# dsp_board_dds_vga.net
KiCad netlist of a schematic drawn in EAGLE
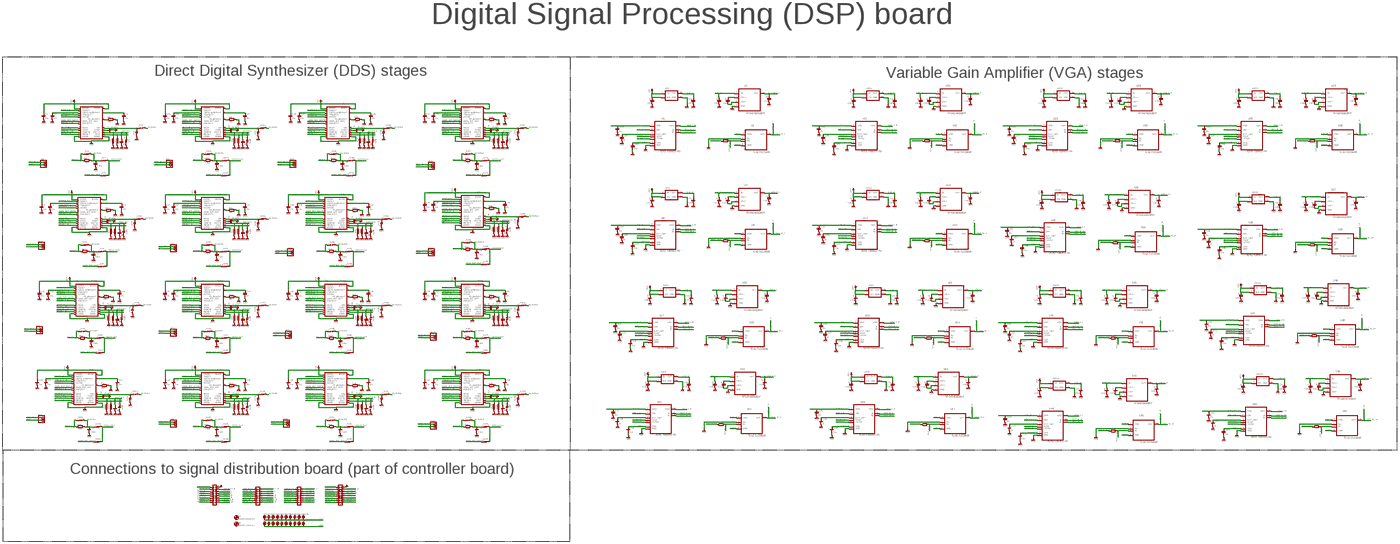
[diagram p0: schematic, sheet 1, overview]
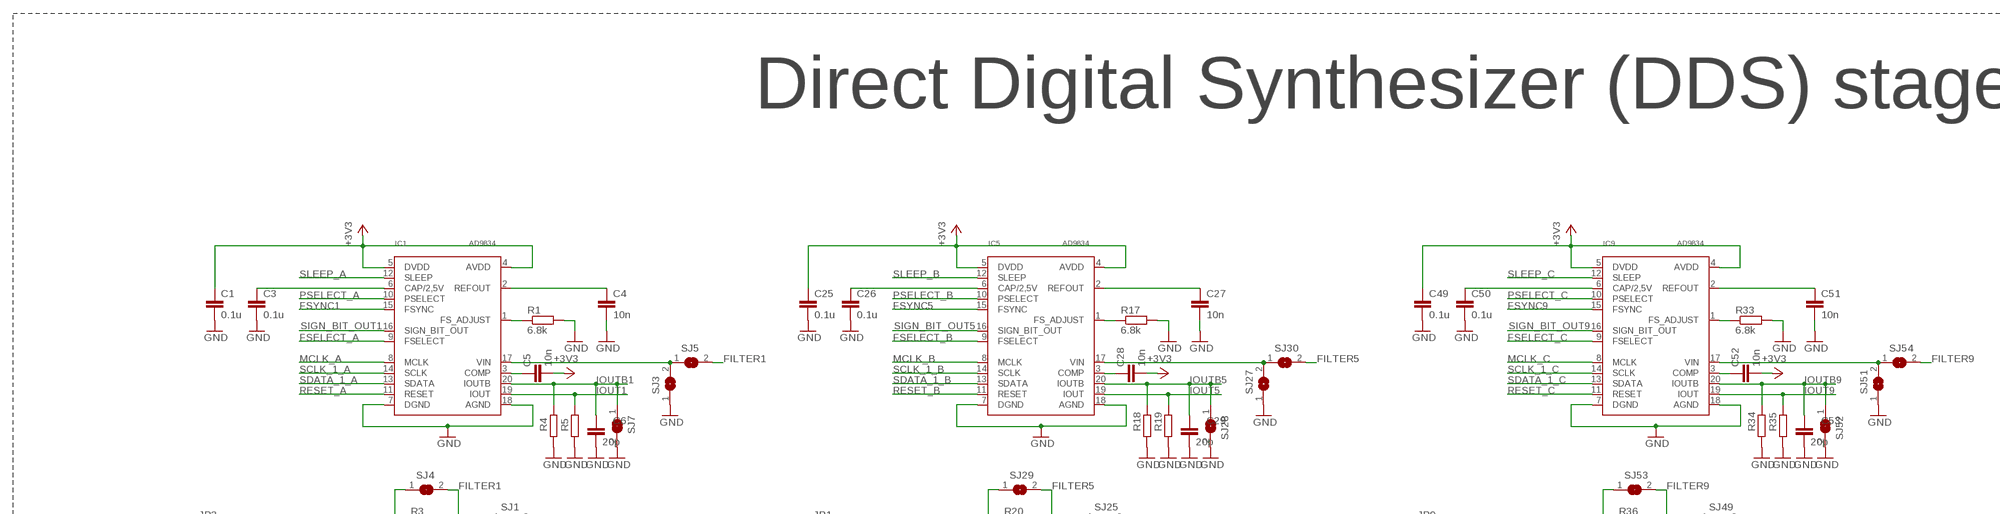
[diagram p1: schematic, sheet 1, part 1 of 7]
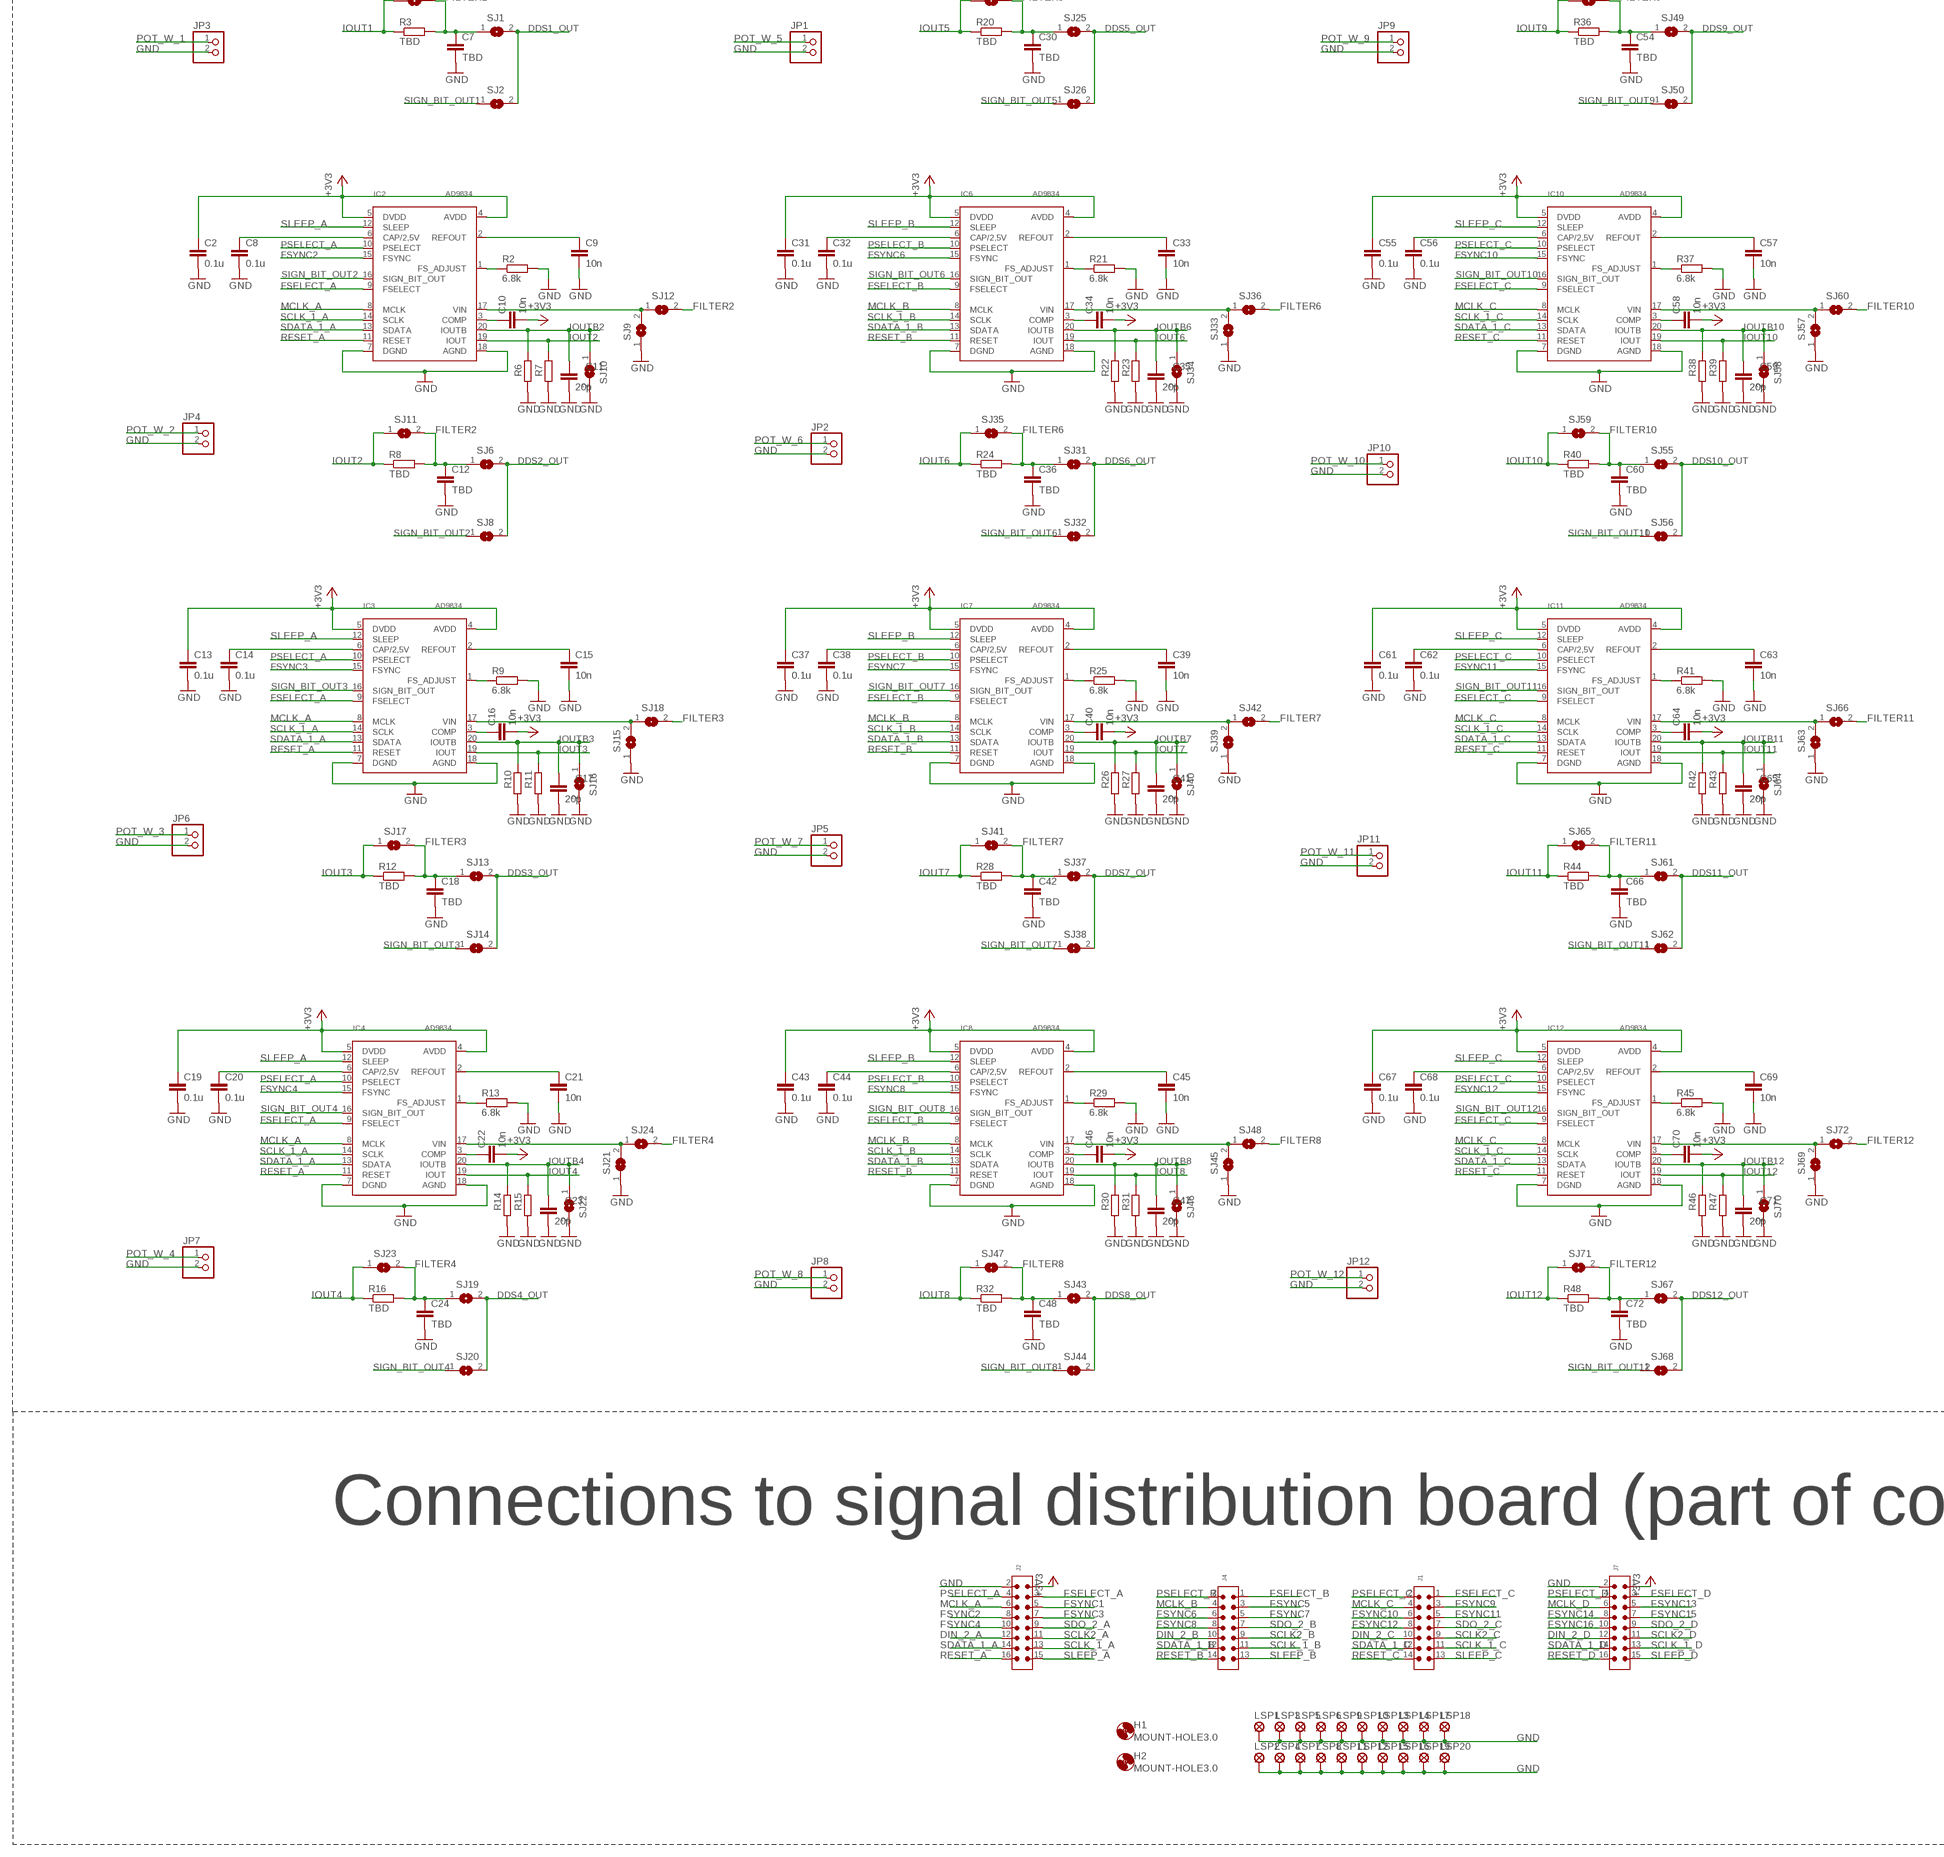
[diagram p2: schematic, sheet 1, part 2 of 7]
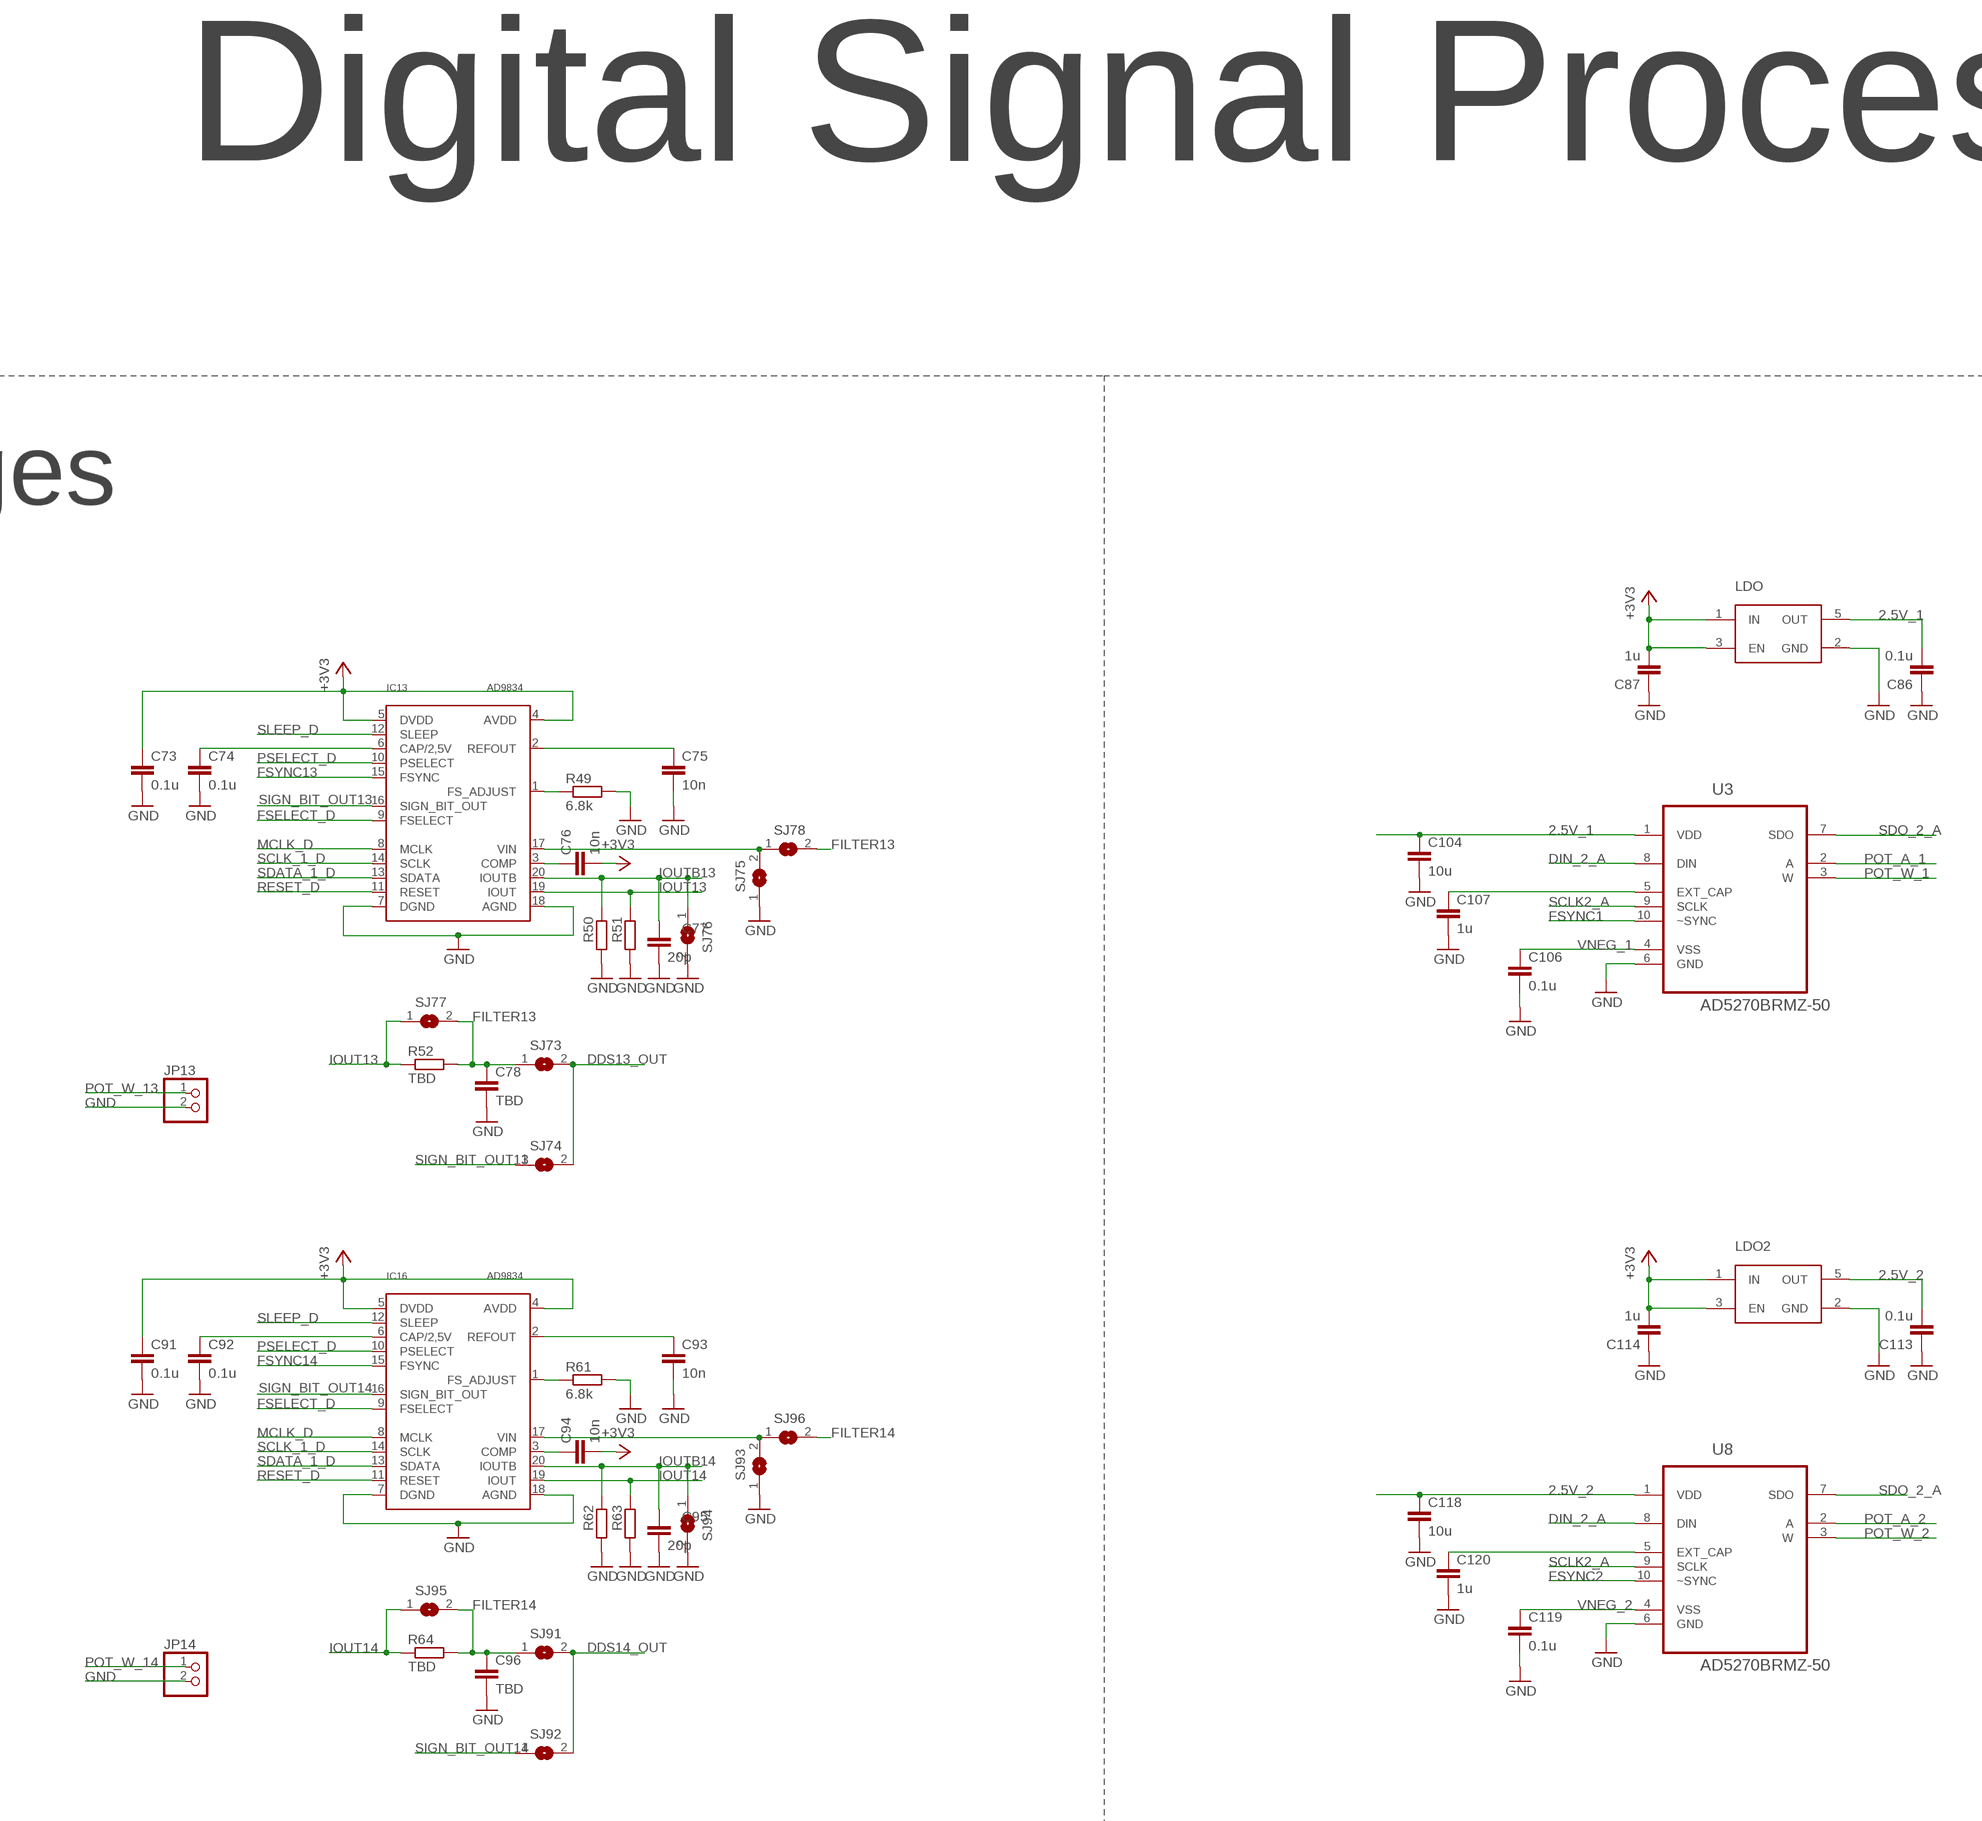
[diagram p3: schematic, sheet 1, part 3 of 7]
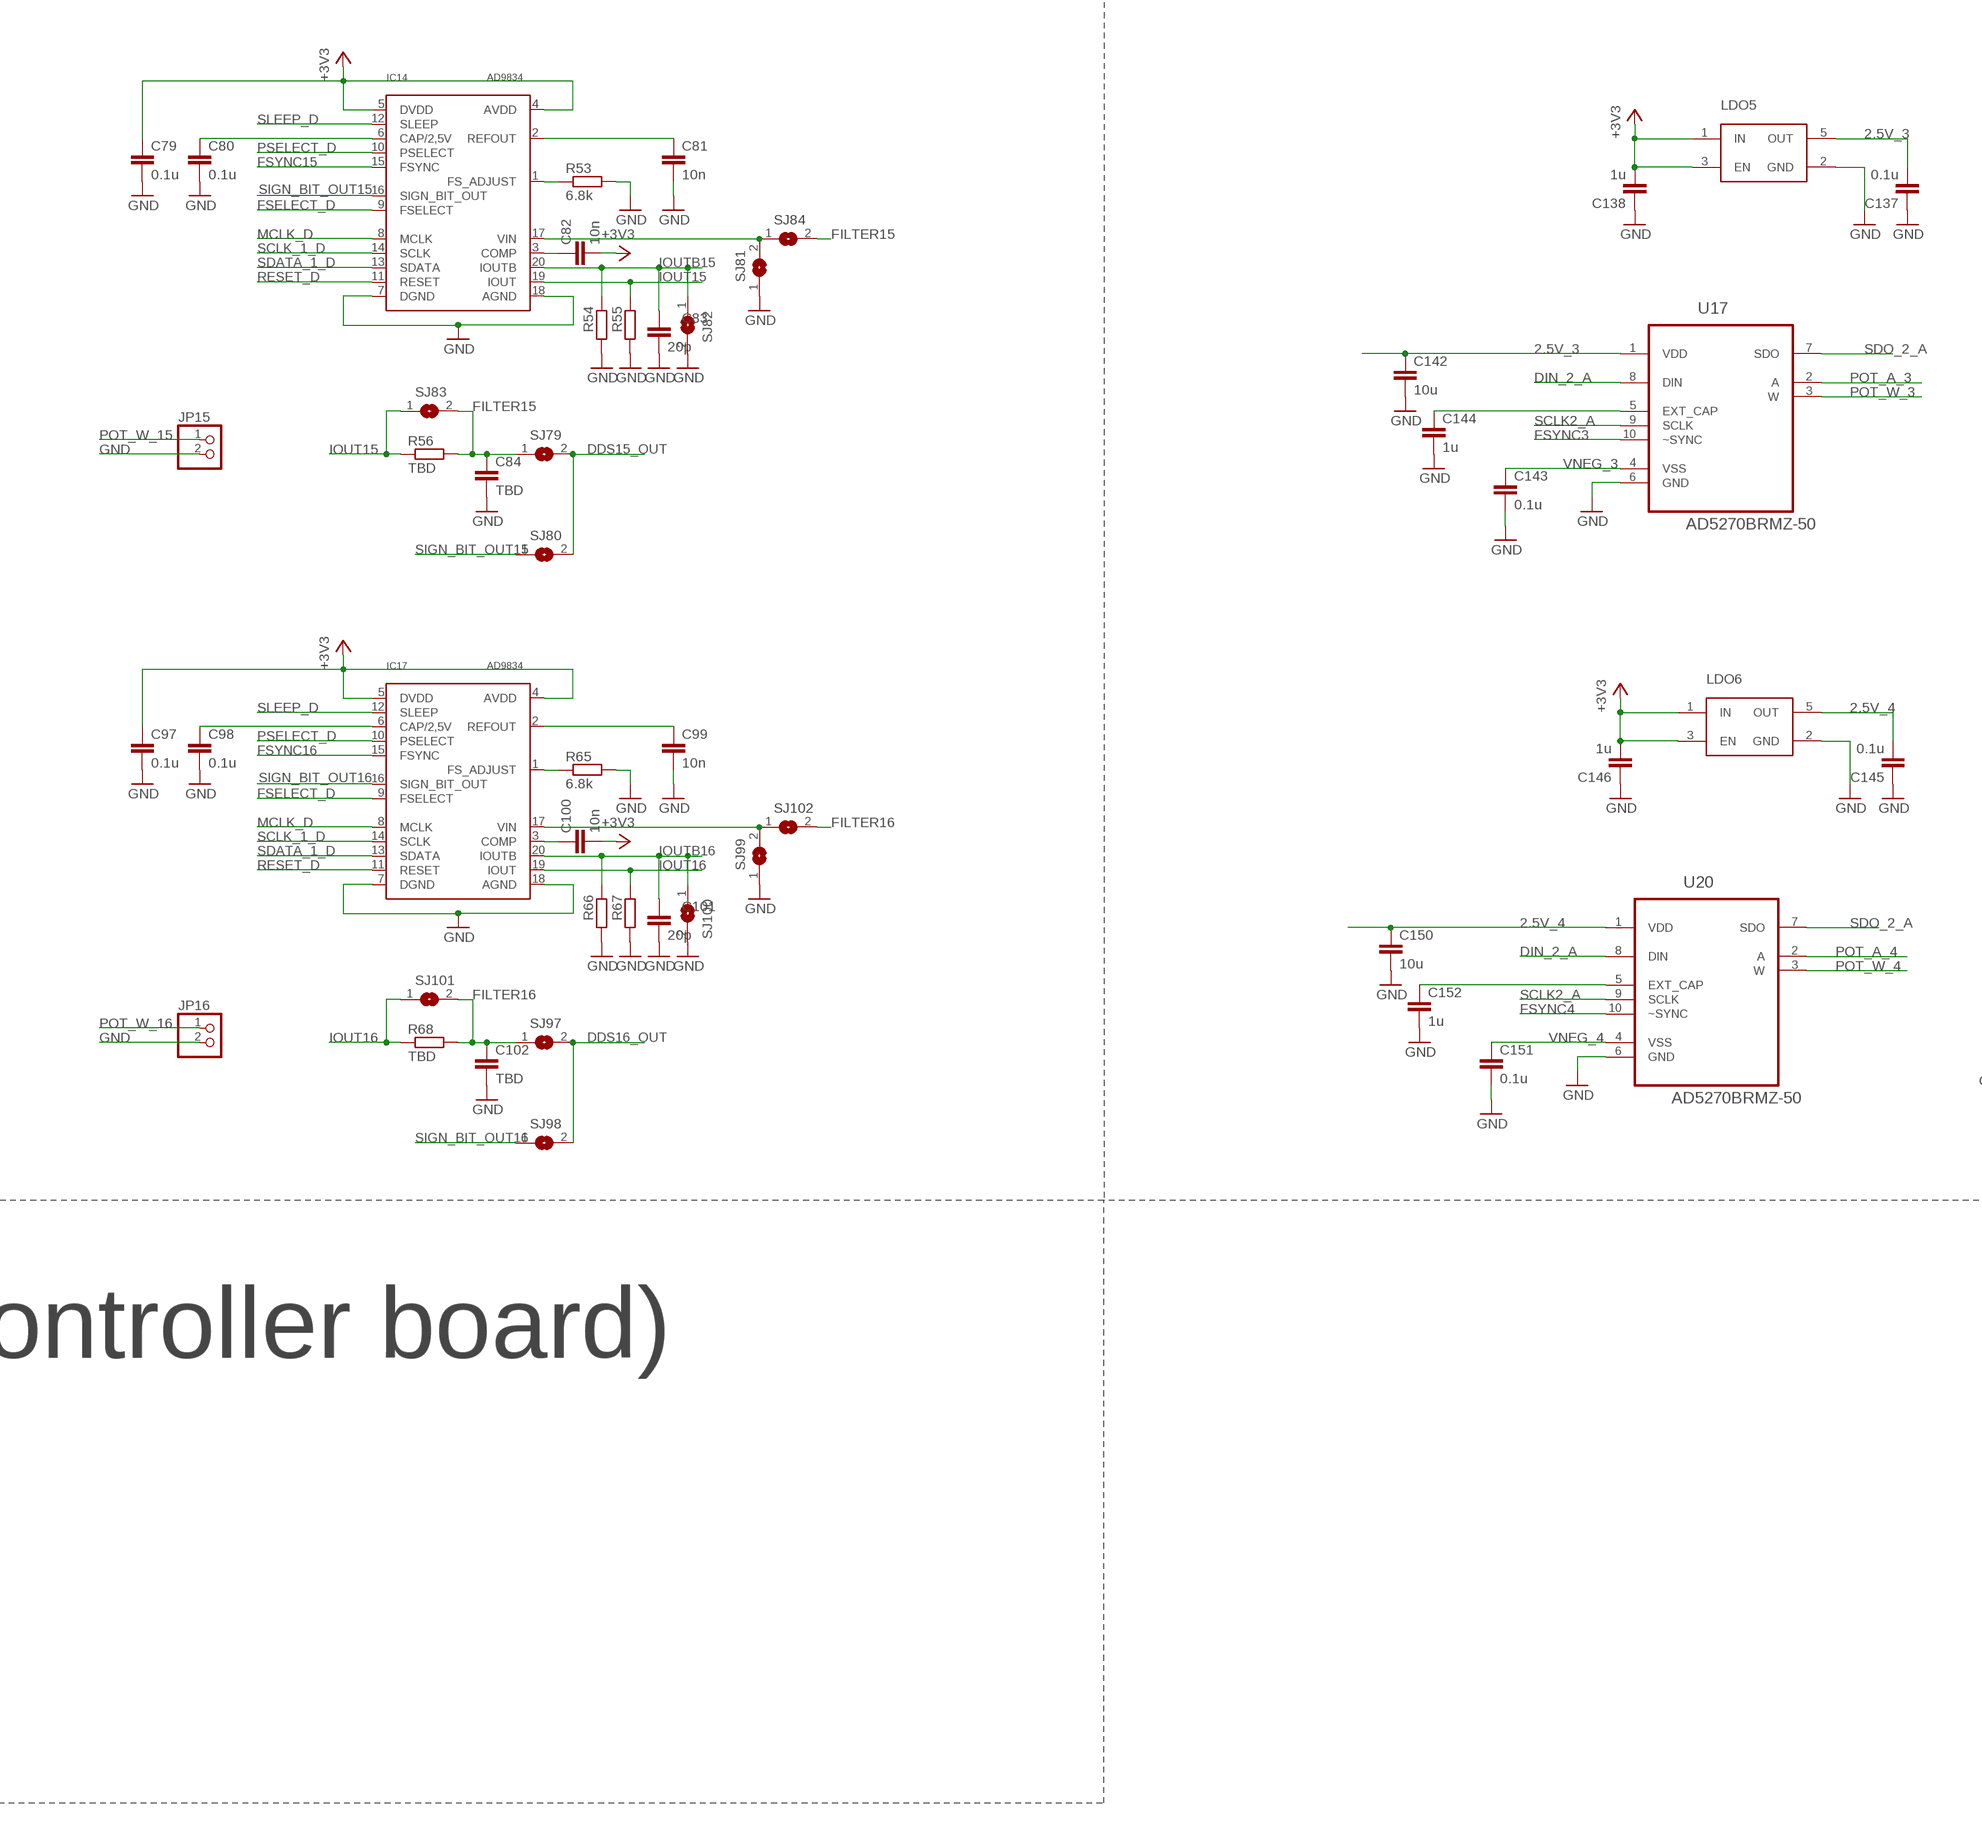
[diagram p4: schematic, sheet 1, part 4 of 7]
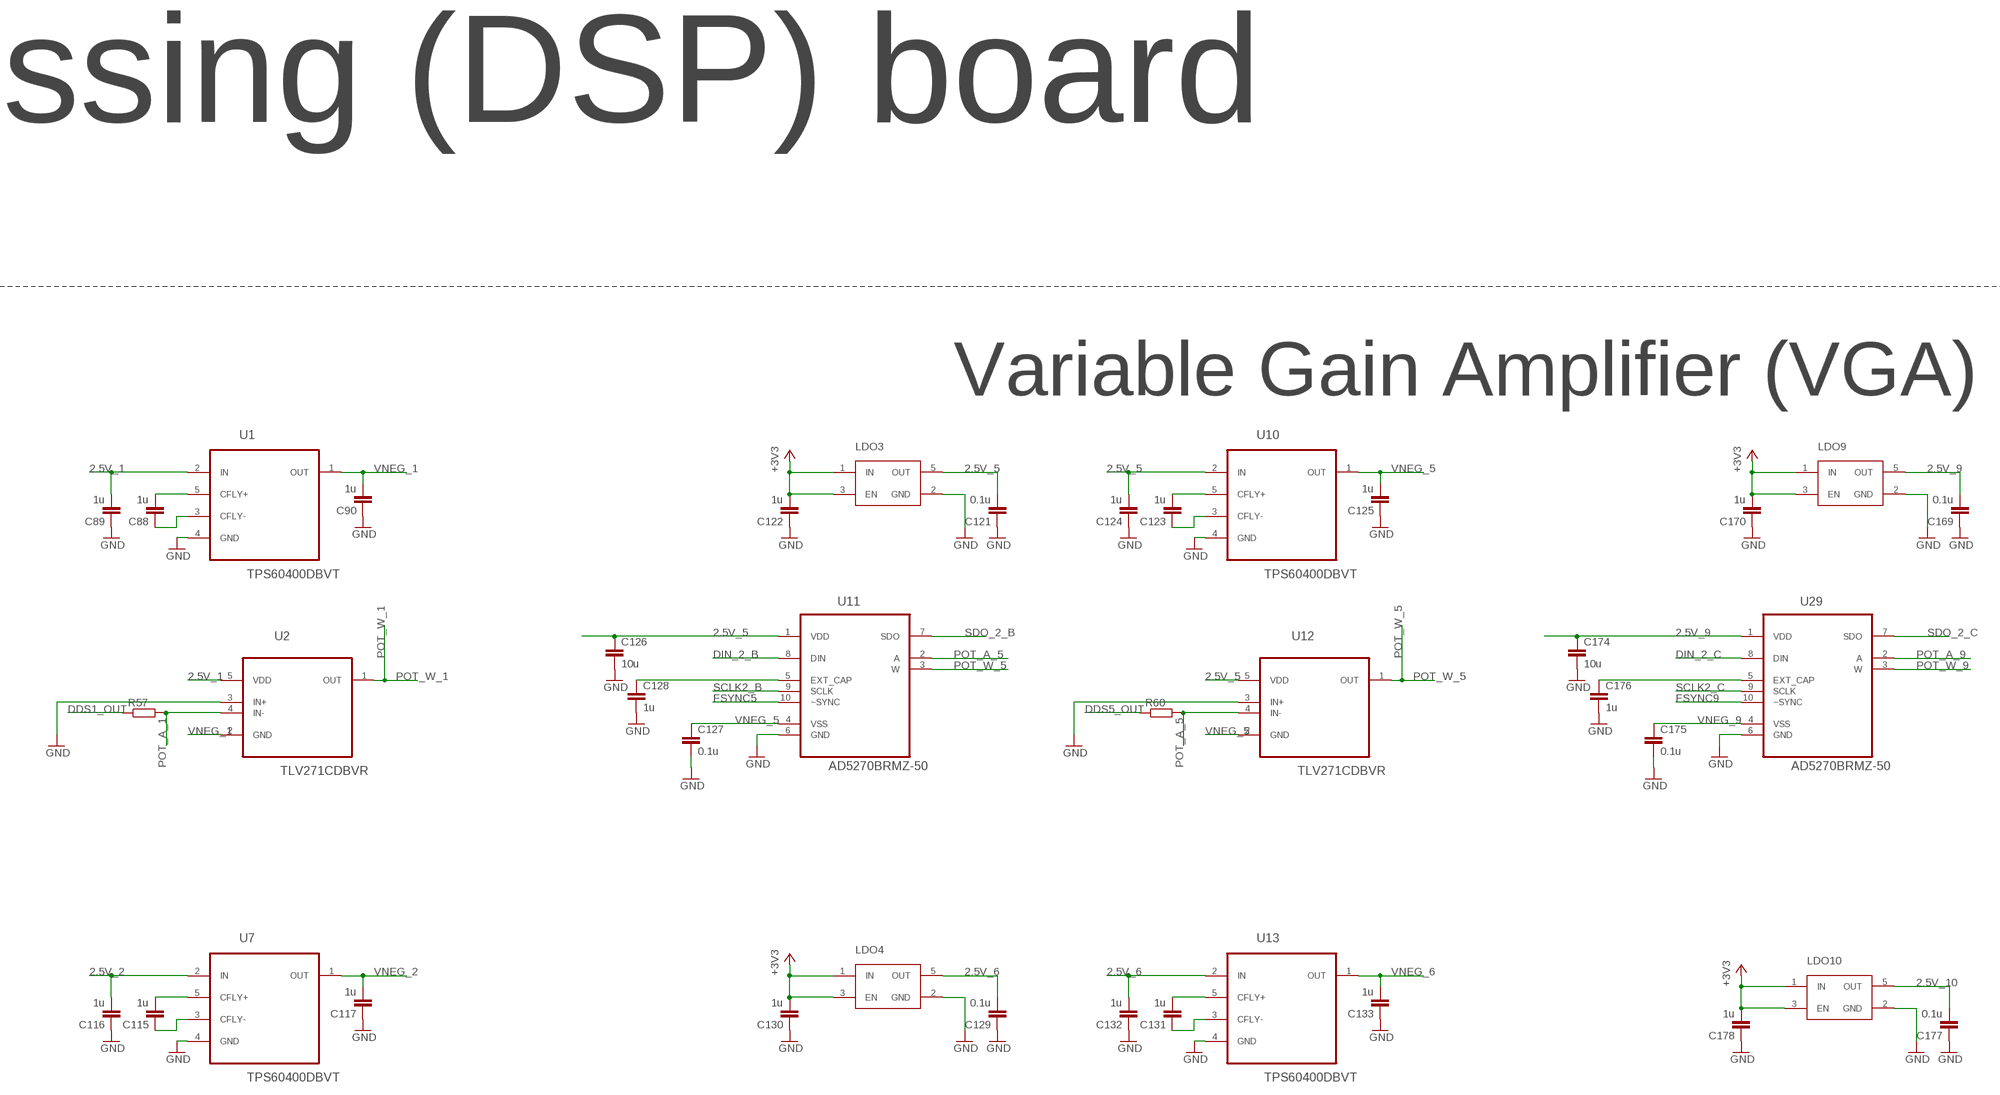
[diagram p5: schematic, sheet 1, part 5 of 7]
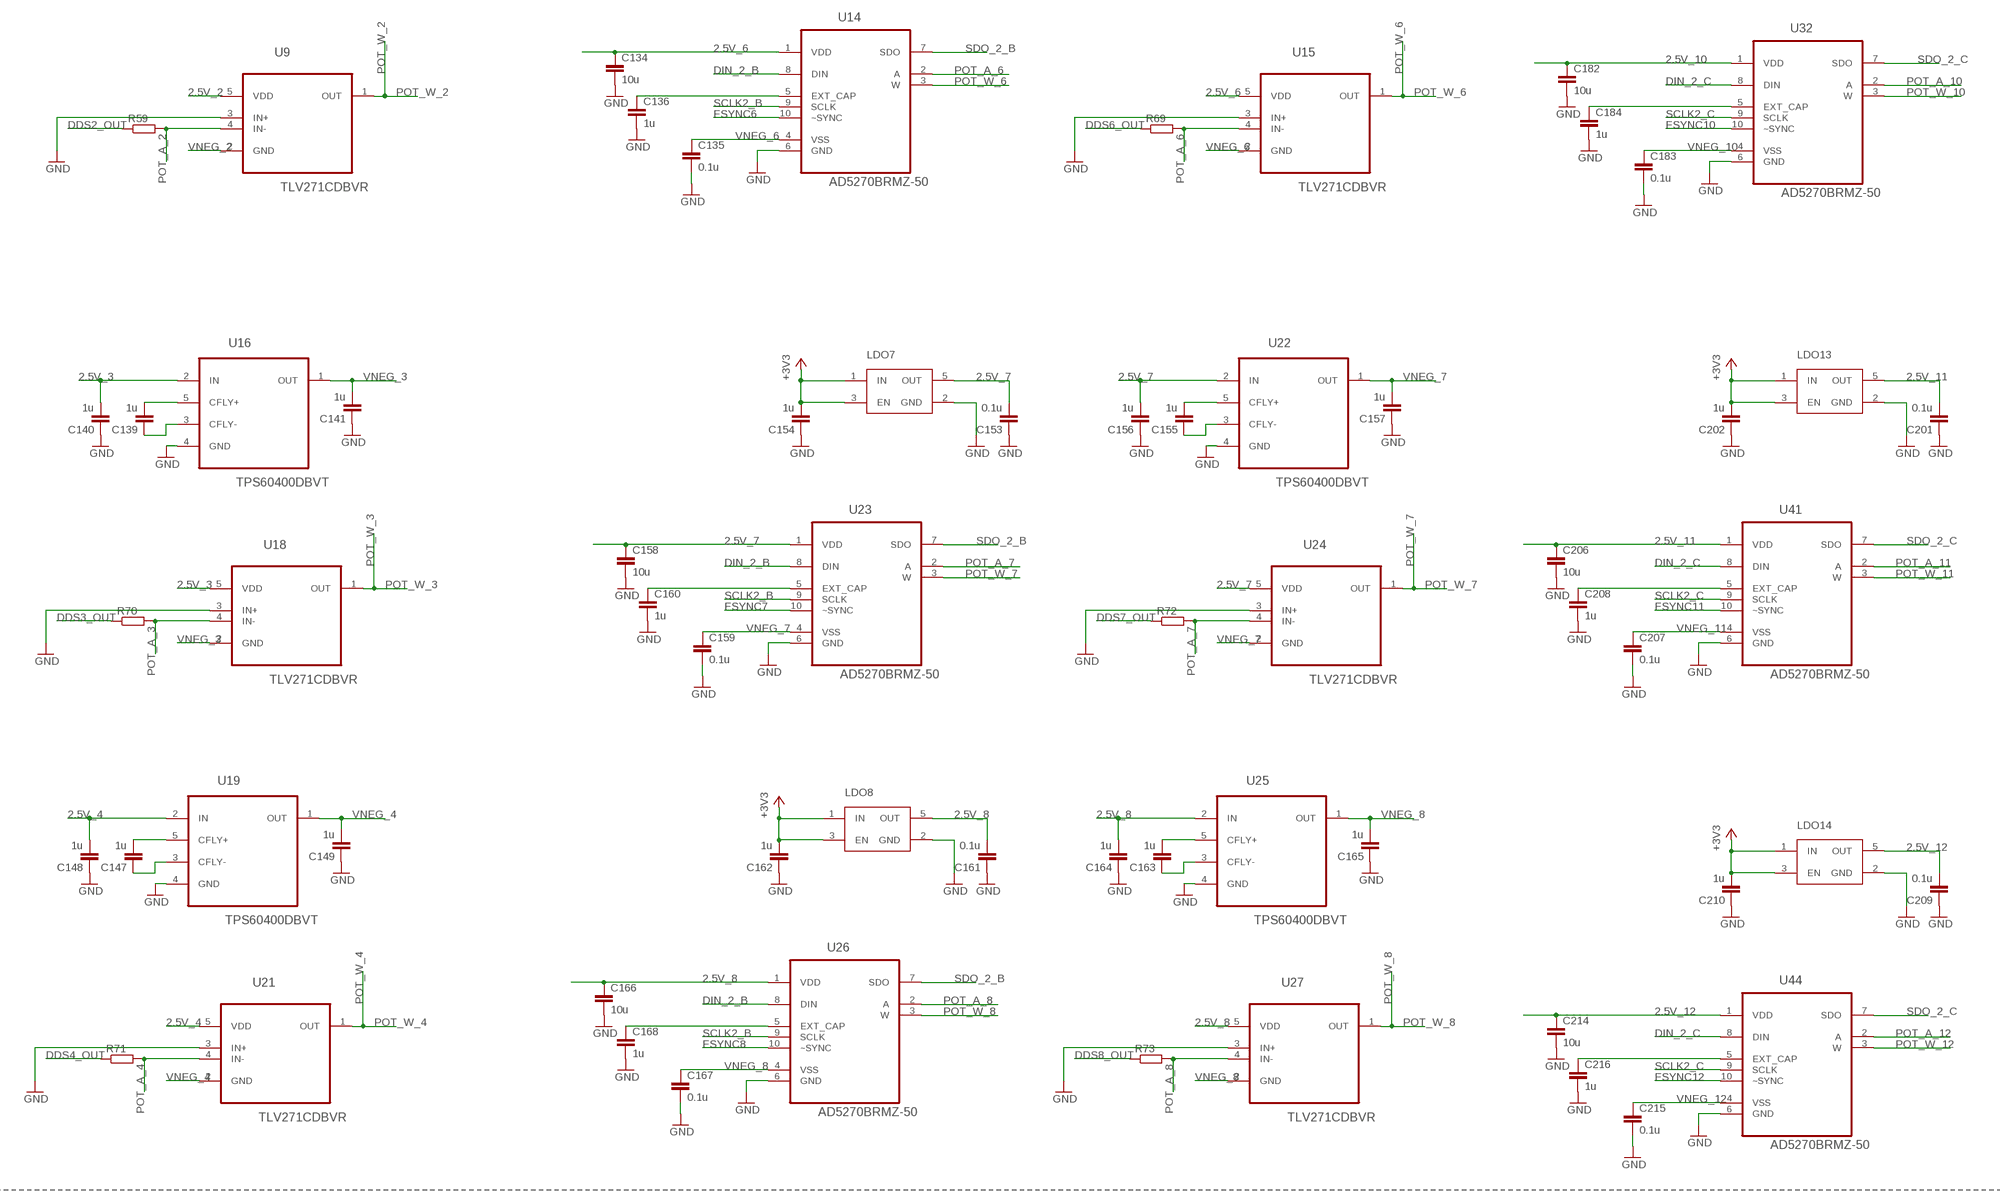
[diagram p6: schematic, sheet 1, part 6 of 7]
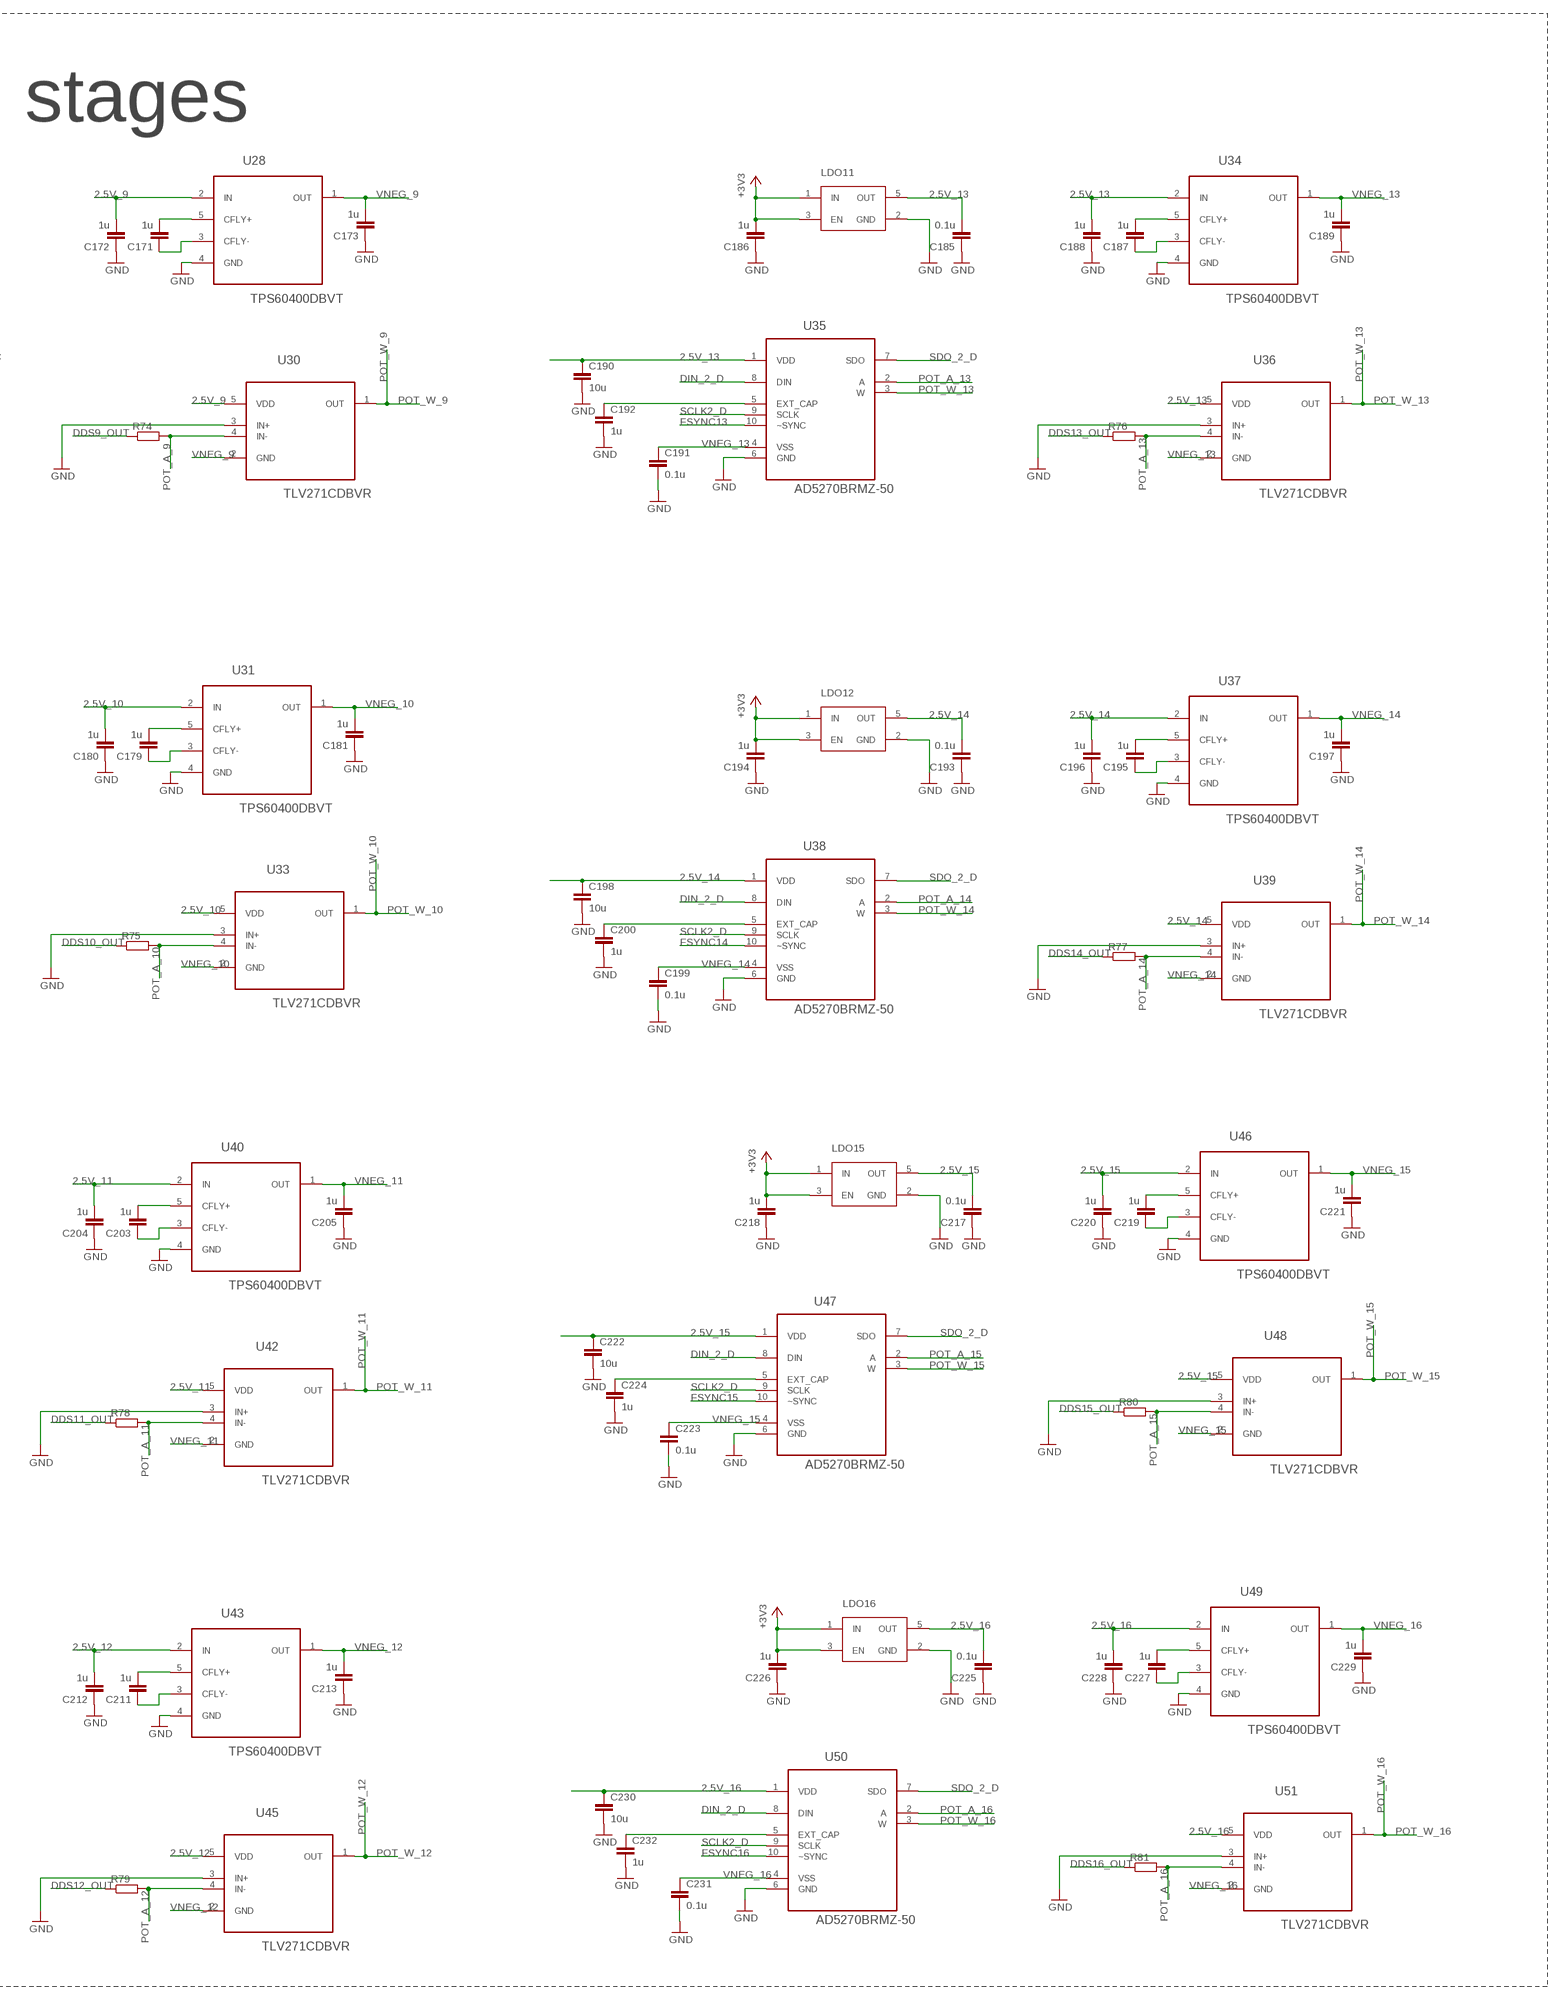
[diagram p7: schematic, sheet 1, part 7 of 7]

(export (version "E")
  (design (tool "Eeschema 10.0.6"))
  (components
    (comp (ref "C1")
      (value "0.1u")
      (footprint "eagle-import:C0603")
      (libsource (lib "eagle-import") (part "C-EUC0603"))
    )
    (comp (ref "C2")
      (value "0.1u")
      (footprint "eagle-import:C0603")
      (libsource (lib "eagle-import") (part "C-EUC0603"))
    )
    (comp (ref "C3")
      (value "0.1u")
      (footprint "eagle-import:C0603")
      (libsource (lib "eagle-import") (part "C-EUC0603"))
    )
    (comp (ref "C4")
      (value "10n")
      (footprint "eagle-import:C0603")
      (libsource (lib "eagle-import") (part "C-EUC0603"))
    )
    (comp (ref "C5")
      (value "10n")
      (footprint "eagle-import:C0603")
      (libsource (lib "eagle-import") (part "C-EUC0603"))
    )
    (comp (ref "C6")
      (value "20p")
      (footprint "eagle-import:C0603")
      (libsource (lib "eagle-import") (part "C-EUC0603"))
    )
    (comp (ref "C7")
      (value "TBD")
      (footprint "eagle-import:C0603")
      (libsource (lib "eagle-import") (part "C-EUC0603"))
    )
    (comp (ref "C8")
      (value "0.1u")
      (footprint "eagle-import:C0603")
      (libsource (lib "eagle-import") (part "C-EUC0603"))
    )
    (comp (ref "C9")
      (value "10n")
      (footprint "eagle-import:C0603")
      (libsource (lib "eagle-import") (part "C-EUC0603"))
    )
    (comp (ref "C10")
      (value "10n")
      (footprint "eagle-import:C0603")
      (libsource (lib "eagle-import") (part "C-EUC0603"))
    )
    (comp (ref "C11")
      (value "20p")
      (footprint "eagle-import:C0603")
      (libsource (lib "eagle-import") (part "C-EUC0603"))
    )
    (comp (ref "C12")
      (value "TBD")
      (footprint "eagle-import:C0603")
      (libsource (lib "eagle-import") (part "C-EUC0603"))
    )
    (comp (ref "C13")
      (value "0.1u")
      (footprint "eagle-import:C0603")
      (libsource (lib "eagle-import") (part "C-EUC0603"))
    )
    (comp (ref "C14")
      (value "0.1u")
      (footprint "eagle-import:C0603")
      (libsource (lib "eagle-import") (part "C-EUC0603"))
    )
    (comp (ref "C15")
      (value "10n")
      (footprint "eagle-import:C0603")
      (libsource (lib "eagle-import") (part "C-EUC0603"))
    )
    (comp (ref "C16")
      (value "10n")
      (footprint "eagle-import:C0603")
      (libsource (lib "eagle-import") (part "C-EUC0603"))
    )
    (comp (ref "C17")
      (value "20p")
      (footprint "eagle-import:C0603")
      (libsource (lib "eagle-import") (part "C-EUC0603"))
    )
    (comp (ref "C18")
      (value "TBD")
      (footprint "eagle-import:C0603")
      (libsource (lib "eagle-import") (part "C-EUC0603"))
    )
    (comp (ref "C19")
      (value "0.1u")
      (footprint "eagle-import:C0603")
      (libsource (lib "eagle-import") (part "C-EUC0603"))
    )
    (comp (ref "C20")
      (value "0.1u")
      (footprint "eagle-import:C0603")
      (libsource (lib "eagle-import") (part "C-EUC0603"))
    )
    (comp (ref "C21")
      (value "10n")
      (footprint "eagle-import:C0603")
      (libsource (lib "eagle-import") (part "C-EUC0603"))
    )
    (comp (ref "C22")
      (value "10n")
      (footprint "eagle-import:C0603")
      (libsource (lib "eagle-import") (part "C-EUC0603"))
    )
    (comp (ref "C23")
      (value "20p")
      (footprint "eagle-import:C0603")
      (libsource (lib "eagle-import") (part "C-EUC0603"))
    )
    (comp (ref "C24")
      (value "TBD")
      (footprint "eagle-import:C0603")
      (libsource (lib "eagle-import") (part "C-EUC0603"))
    )
    (comp (ref "C25")
      (value "0.1u")
      (footprint "eagle-import:C0603")
      (libsource (lib "eagle-import") (part "C-EUC0603"))
    )
    (comp (ref "C26")
      (value "0.1u")
      (footprint "eagle-import:C0603")
      (libsource (lib "eagle-import") (part "C-EUC0603"))
    )
    (comp (ref "C27")
      (value "10n")
      (footprint "eagle-import:C0603")
      (libsource (lib "eagle-import") (part "C-EUC0603"))
    )
    (comp (ref "C28")
      (value "10n")
      (footprint "eagle-import:C0603")
      (libsource (lib "eagle-import") (part "C-EUC0603"))
    )
    (comp (ref "C29")
      (value "20p")
      (footprint "eagle-import:C0603")
      (libsource (lib "eagle-import") (part "C-EUC0603"))
    )
    (comp (ref "C30")
      (value "TBD")
      (footprint "eagle-import:C0603")
      (libsource (lib "eagle-import") (part "C-EUC0603"))
    )
    (comp (ref "C31")
      (value "0.1u")
      (footprint "eagle-import:C0603")
      (libsource (lib "eagle-import") (part "C-EUC0603"))
    )
    (comp (ref "C32")
      (value "0.1u")
      (footprint "eagle-import:C0603")
      (libsource (lib "eagle-import") (part "C-EUC0603"))
    )
    (comp (ref "C33")
      (value "10n")
      (footprint "eagle-import:C0603")
      (libsource (lib "eagle-import") (part "C-EUC0603"))
    )
    (comp (ref "C34")
      (value "10n")
      (footprint "eagle-import:C0603")
      (libsource (lib "eagle-import") (part "C-EUC0603"))
    )
    (comp (ref "C35")
      (value "20p")
      (footprint "eagle-import:C0603")
      (libsource (lib "eagle-import") (part "C-EUC0603"))
    )
    (comp (ref "C36")
      (value "TBD")
      (footprint "eagle-import:C0603")
      (libsource (lib "eagle-import") (part "C-EUC0603"))
    )
    (comp (ref "C37")
      (value "0.1u")
      (footprint "eagle-import:C0603")
      (libsource (lib "eagle-import") (part "C-EUC0603"))
    )
    (comp (ref "C38")
      (value "0.1u")
      (footprint "eagle-import:C0603")
      (libsource (lib "eagle-import") (part "C-EUC0603"))
    )
    (comp (ref "C39")
      (value "10n")
      (footprint "eagle-import:C0603")
      (libsource (lib "eagle-import") (part "C-EUC0603"))
    )
    (comp (ref "C40")
      (value "10n")
      (footprint "eagle-import:C0603")
      (libsource (lib "eagle-import") (part "C-EUC0603"))
    )
    (comp (ref "C41")
      (value "20p")
      (footprint "eagle-import:C0603")
      (libsource (lib "eagle-import") (part "C-EUC0603"))
    )
    (comp (ref "C42")
      (value "TBD")
      (footprint "eagle-import:C0603")
      (libsource (lib "eagle-import") (part "C-EUC0603"))
    )
    (comp (ref "C43")
      (value "0.1u")
      (footprint "eagle-import:C0603")
      (libsource (lib "eagle-import") (part "C-EUC0603"))
    )
    (comp (ref "C44")
      (value "0.1u")
      (footprint "eagle-import:C0603")
      (libsource (lib "eagle-import") (part "C-EUC0603"))
    )
    (comp (ref "C45")
      (value "10n")
      (footprint "eagle-import:C0603")
      (libsource (lib "eagle-import") (part "C-EUC0603"))
    )
    (comp (ref "C46")
      (value "10n")
      (footprint "eagle-import:C0603")
      (libsource (lib "eagle-import") (part "C-EUC0603"))
    )
    (comp (ref "C47")
      (value "20p")
      (footprint "eagle-import:C0603")
      (libsource (lib "eagle-import") (part "C-EUC0603"))
    )
    (comp (ref "C48")
      (value "TBD")
      (footprint "eagle-import:C0603")
      (libsource (lib "eagle-import") (part "C-EUC0603"))
    )
    (comp (ref "C49")
      (value "0.1u")
      (footprint "eagle-import:C0603")
      (libsource (lib "eagle-import") (part "C-EUC0603"))
    )
    (comp (ref "C50")
      (value "0.1u")
      (footprint "eagle-import:C0603")
      (libsource (lib "eagle-import") (part "C-EUC0603"))
    )
    (comp (ref "C51")
      (value "10n")
      (footprint "eagle-import:C0603")
      (libsource (lib "eagle-import") (part "C-EUC0603"))
    )
    (comp (ref "C52")
      (value "10n")
      (footprint "eagle-import:C0603")
      (libsource (lib "eagle-import") (part "C-EUC0603"))
    )
    (comp (ref "C53")
      (value "20p")
      (footprint "eagle-import:C0603")
      (libsource (lib "eagle-import") (part "C-EUC0603"))
    )
    (comp (ref "C54")
      (value "TBD")
      (footprint "eagle-import:C0603")
      (libsource (lib "eagle-import") (part "C-EUC0603"))
    )
    (comp (ref "C55")
      (value "0.1u")
      (footprint "eagle-import:C0603")
      (libsource (lib "eagle-import") (part "C-EUC0603"))
    )
    (comp (ref "C56")
      (value "0.1u")
      (footprint "eagle-import:C0603")
      (libsource (lib "eagle-import") (part "C-EUC0603"))
    )
    (comp (ref "C57")
      (value "10n")
      (footprint "eagle-import:C0603")
      (libsource (lib "eagle-import") (part "C-EUC0603"))
    )
    (comp (ref "C58")
      (value "10n")
      (footprint "eagle-import:C0603")
      (libsource (lib "eagle-import") (part "C-EUC0603"))
    )
    (comp (ref "C59")
      (value "20p")
      (footprint "eagle-import:C0603")
      (libsource (lib "eagle-import") (part "C-EUC0603"))
    )
    (comp (ref "C60")
      (value "TBD")
      (footprint "eagle-import:C0603")
      (libsource (lib "eagle-import") (part "C-EUC0603"))
    )
    (comp (ref "C61")
      (value "0.1u")
      (footprint "eagle-import:C0603")
      (libsource (lib "eagle-import") (part "C-EUC0603"))
    )
    (comp (ref "C62")
      (value "0.1u")
      (footprint "eagle-import:C0603")
      (libsource (lib "eagle-import") (part "C-EUC0603"))
    )
    (comp (ref "C63")
      (value "10n")
      (footprint "eagle-import:C0603")
      (libsource (lib "eagle-import") (part "C-EUC0603"))
    )
    (comp (ref "C64")
      (value "10n")
      (footprint "eagle-import:C0603")
      (libsource (lib "eagle-import") (part "C-EUC0603"))
    )
    (comp (ref "C65")
      (value "20p")
      (footprint "eagle-import:C0603")
      (libsource (lib "eagle-import") (part "C-EUC0603"))
    )
    (comp (ref "C66")
      (value "TBD")
      (footprint "eagle-import:C0603")
      (libsource (lib "eagle-import") (part "C-EUC0603"))
    )
    (comp (ref "C67")
      (value "0.1u")
      (footprint "eagle-import:C0603")
      (libsource (lib "eagle-import") (part "C-EUC0603"))
    )
    (comp (ref "C68")
      (value "0.1u")
      (footprint "eagle-import:C0603")
      (libsource (lib "eagle-import") (part "C-EUC0603"))
    )
    (comp (ref "C69")
      (value "10n")
      (footprint "eagle-import:C0603")
      (libsource (lib "eagle-import") (part "C-EUC0603"))
    )
    (comp (ref "C70")
      (value "10n")
      (footprint "eagle-import:C0603")
      (libsource (lib "eagle-import") (part "C-EUC0603"))
    )
    (comp (ref "C71")
      (value "20p")
      (footprint "eagle-import:C0603")
      (libsource (lib "eagle-import") (part "C-EUC0603"))
    )
    (comp (ref "C72")
      (value "TBD")
      (footprint "eagle-import:C0603")
      (libsource (lib "eagle-import") (part "C-EUC0603"))
    )
    (comp (ref "C73")
      (value "0.1u")
      (footprint "eagle-import:C0603")
      (libsource (lib "eagle-import") (part "C-EUC0603"))
    )
    (comp (ref "C74")
      (value "0.1u")
      (footprint "eagle-import:C0603")
      (libsource (lib "eagle-import") (part "C-EUC0603"))
    )
    (comp (ref "C75")
      (value "10n")
      (footprint "eagle-import:C0603")
      (libsource (lib "eagle-import") (part "C-EUC0603"))
    )
    (comp (ref "C76")
      (value "10n")
      (footprint "eagle-import:C0603")
      (libsource (lib "eagle-import") (part "C-EUC0603"))
    )
    (comp (ref "C77")
      (value "20p")
      (footprint "eagle-import:C0603")
      (libsource (lib "eagle-import") (part "C-EUC0603"))
    )
    (comp (ref "C78")
      (value "TBD")
      (footprint "eagle-import:C0603")
      (libsource (lib "eagle-import") (part "C-EUC0603"))
    )
    (comp (ref "C79")
      (value "0.1u")
      (footprint "eagle-import:C0603")
      (libsource (lib "eagle-import") (part "C-EUC0603"))
    )
    (comp (ref "C80")
      (value "0.1u")
      (footprint "eagle-import:C0603")
      (libsource (lib "eagle-import") (part "C-EUC0603"))
    )
    (comp (ref "C81")
      (value "10n")
      (footprint "eagle-import:C0603")
      (libsource (lib "eagle-import") (part "C-EUC0603"))
    )
    (comp (ref "C82")
      (value "10n")
      (footprint "eagle-import:C0603")
      (libsource (lib "eagle-import") (part "C-EUC0603"))
    )
    (comp (ref "C83")
      (value "20p")
      (footprint "eagle-import:C0603")
      (libsource (lib "eagle-import") (part "C-EUC0603"))
    )
    (comp (ref "C84")
      (value "TBD")
      (footprint "eagle-import:C0603")
      (libsource (lib "eagle-import") (part "C-EUC0603"))
    )
    (comp (ref "C86")
      (value "0.1u")
      (footprint "eagle-import:C0603")
      (libsource (lib "eagle-import") (part "C-EUC0603"))
    )
    (comp (ref "C87")
      (value "1u")
      (footprint "eagle-import:C0603")
      (libsource (lib "eagle-import") (part "C-EUC0603"))
    )
    (comp (ref "C88")
      (value "1u")
      (footprint "eagle-import:C0603")
      (libsource (lib "eagle-import") (part "C-EUC0603"))
    )
    (comp (ref "C89")
      (value "1u")
      (footprint "eagle-import:C0603")
      (libsource (lib "eagle-import") (part "C-EUC0603"))
    )
    (comp (ref "C90")
      (value "1u")
      (footprint "eagle-import:C0603")
      (libsource (lib "eagle-import") (part "C-EUC0603"))
    )
    (comp (ref "C91")
      (value "0.1u")
      (footprint "eagle-import:C0603")
      (libsource (lib "eagle-import") (part "C-EUC0603"))
    )
    (comp (ref "C92")
      (value "0.1u")
      (footprint "eagle-import:C0603")
      (libsource (lib "eagle-import") (part "C-EUC0603"))
    )
    (comp (ref "C93")
      (value "10n")
      (footprint "eagle-import:C0603")
      (libsource (lib "eagle-import") (part "C-EUC0603"))
    )
    (comp (ref "C94")
      (value "10n")
      (footprint "eagle-import:C0603")
      (libsource (lib "eagle-import") (part "C-EUC0603"))
    )
    (comp (ref "C95")
      (value "20p")
      (footprint "eagle-import:C0603")
      (libsource (lib "eagle-import") (part "C-EUC0603"))
    )
    (comp (ref "C96")
      (value "TBD")
      (footprint "eagle-import:C0603")
      (libsource (lib "eagle-import") (part "C-EUC0603"))
    )
    (comp (ref "C97")
      (value "0.1u")
      (footprint "eagle-import:C0603")
      (libsource (lib "eagle-import") (part "C-EUC0603"))
    )
    (comp (ref "C98")
      (value "0.1u")
      (footprint "eagle-import:C0603")
      (libsource (lib "eagle-import") (part "C-EUC0603"))
    )
    (comp (ref "C99")
      (value "10n")
      (footprint "eagle-import:C0603")
      (libsource (lib "eagle-import") (part "C-EUC0603"))
    )
    (comp (ref "C100")
      (value "10n")
      (footprint "eagle-import:C0603")
      (libsource (lib "eagle-import") (part "C-EUC0603"))
    )
    (comp (ref "C101")
      (value "20p")
      (footprint "eagle-import:C0603")
      (libsource (lib "eagle-import") (part "C-EUC0603"))
    )
    (comp (ref "C102")
      (value "TBD")
      (footprint "eagle-import:C0603")
      (libsource (lib "eagle-import") (part "C-EUC0603"))
    )
    (comp (ref "C104")
      (value "10u")
      (footprint "eagle-import:C0805")
      (libsource (lib "eagle-import") (part "C-EUC0805"))
    )
    (comp (ref "C106")
      (value "0.1u")
      (footprint "eagle-import:C0603")
      (libsource (lib "eagle-import") (part "C-EUC0603"))
    )
    (comp (ref "C107")
      (value "1u")
      (footprint "eagle-import:C0603")
      (libsource (lib "eagle-import") (part "C-EUC0603"))
    )
    (comp (ref "C113")
      (value "0.1u")
      (footprint "eagle-import:C0603")
      (libsource (lib "eagle-import") (part "C-EUC0603"))
    )
    (comp (ref "C114")
      (value "1u")
      (footprint "eagle-import:C0603")
      (libsource (lib "eagle-import") (part "C-EUC0603"))
    )
    (comp (ref "C115")
      (value "1u")
      (footprint "eagle-import:C0603")
      (libsource (lib "eagle-import") (part "C-EUC0603"))
    )
    (comp (ref "C116")
      (value "1u")
      (footprint "eagle-import:C0603")
      (libsource (lib "eagle-import") (part "C-EUC0603"))
    )
    (comp (ref "C117")
      (value "1u")
      (footprint "eagle-import:C0603")
      (libsource (lib "eagle-import") (part "C-EUC0603"))
    )
    (comp (ref "C118")
      (value "10u")
      (footprint "eagle-import:C0805")
      (libsource (lib "eagle-import") (part "C-EUC0805"))
    )
    (comp (ref "C119")
      (value "0.1u")
      (footprint "eagle-import:C0603")
      (libsource (lib "eagle-import") (part "C-EUC0603"))
    )
    (comp (ref "C120")
      (value "1u")
      (footprint "eagle-import:C0603")
      (libsource (lib "eagle-import") (part "C-EUC0603"))
    )
    (comp (ref "C121")
      (value "0.1u")
      (footprint "eagle-import:C0603")
      (libsource (lib "eagle-import") (part "C-EUC0603"))
    )
    (comp (ref "C122")
      (value "1u")
      (footprint "eagle-import:C0603")
      (libsource (lib "eagle-import") (part "C-EUC0603"))
    )
    (comp (ref "C123")
      (value "1u")
      (footprint "eagle-import:C0603")
      (libsource (lib "eagle-import") (part "C-EUC0603"))
    )
    (comp (ref "C124")
      (value "1u")
      (footprint "eagle-import:C0603")
      (libsource (lib "eagle-import") (part "C-EUC0603"))
    )
    (comp (ref "C125")
      (value "1u")
      (footprint "eagle-import:C0603")
      (libsource (lib "eagle-import") (part "C-EUC0603"))
    )
    (comp (ref "C126")
      (value "10u")
      (footprint "eagle-import:C0805")
      (libsource (lib "eagle-import") (part "C-EUC0805"))
    )
    (comp (ref "C127")
      (value "0.1u")
      (footprint "eagle-import:C0603")
      (libsource (lib "eagle-import") (part "C-EUC0603"))
    )
    (comp (ref "C128")
      (value "1u")
      (footprint "eagle-import:C0603")
      (libsource (lib "eagle-import") (part "C-EUC0603"))
    )
    (comp (ref "C129")
      (value "0.1u")
      (footprint "eagle-import:C0603")
      (libsource (lib "eagle-import") (part "C-EUC0603"))
    )
    (comp (ref "C130")
      (value "1u")
      (footprint "eagle-import:C0603")
      (libsource (lib "eagle-import") (part "C-EUC0603"))
    )
    (comp (ref "C131")
      (value "1u")
      (footprint "eagle-import:C0603")
      (libsource (lib "eagle-import") (part "C-EUC0603"))
    )
    (comp (ref "C132")
      (value "1u")
      (footprint "eagle-import:C0603")
      (libsource (lib "eagle-import") (part "C-EUC0603"))
    )
    (comp (ref "C133")
      (value "1u")
      (footprint "eagle-import:C0603")
      (libsource (lib "eagle-import") (part "C-EUC0603"))
    )
    (comp (ref "C134")
      (value "10u")
      (footprint "eagle-import:C0805")
      (libsource (lib "eagle-import") (part "C-EUC0805"))
    )
    (comp (ref "C135")
      (value "0.1u")
      (footprint "eagle-import:C0603")
      (libsource (lib "eagle-import") (part "C-EUC0603"))
    )
    (comp (ref "C136")
      (value "1u")
      (footprint "eagle-import:C0603")
      (libsource (lib "eagle-import") (part "C-EUC0603"))
    )
    (comp (ref "C137")
      (value "0.1u")
      (footprint "eagle-import:C0603")
      (libsource (lib "eagle-import") (part "C-EUC0603"))
    )
    (comp (ref "C138")
      (value "1u")
      (footprint "eagle-import:C0603")
      (libsource (lib "eagle-import") (part "C-EUC0603"))
    )
    (comp (ref "C139")
      (value "1u")
      (footprint "eagle-import:C0603")
      (libsource (lib "eagle-import") (part "C-EUC0603"))
    )
    (comp (ref "C140")
      (value "1u")
      (footprint "eagle-import:C0603")
      (libsource (lib "eagle-import") (part "C-EUC0603"))
    )
    (comp (ref "C141")
      (value "1u")
      (footprint "eagle-import:C0603")
      (libsource (lib "eagle-import") (part "C-EUC0603"))
    )
    (comp (ref "C142")
      (value "10u")
      (footprint "eagle-import:C0805")
      (libsource (lib "eagle-import") (part "C-EUC0805"))
    )
    (comp (ref "C143")
      (value "0.1u")
      (footprint "eagle-import:C0603")
      (libsource (lib "eagle-import") (part "C-EUC0603"))
    )
    (comp (ref "C144")
      (value "1u")
      (footprint "eagle-import:C0603")
      (libsource (lib "eagle-import") (part "C-EUC0603"))
    )
    (comp (ref "C145")
      (value "0.1u")
      (footprint "eagle-import:C0603")
      (libsource (lib "eagle-import") (part "C-EUC0603"))
    )
    (comp (ref "C146")
      (value "1u")
      (footprint "eagle-import:C0603")
      (libsource (lib "eagle-import") (part "C-EUC0603"))
    )
    (comp (ref "C147")
      (value "1u")
      (footprint "eagle-import:C0603")
      (libsource (lib "eagle-import") (part "C-EUC0603"))
    )
    (comp (ref "C148")
      (value "1u")
      (footprint "eagle-import:C0603")
      (libsource (lib "eagle-import") (part "C-EUC0603"))
    )
    (comp (ref "C149")
      (value "1u")
      (footprint "eagle-import:C0603")
      (libsource (lib "eagle-import") (part "C-EUC0603"))
    )
    (comp (ref "C150")
      (value "10u")
      (footprint "eagle-import:C0805")
      (libsource (lib "eagle-import") (part "C-EUC0805"))
    )
    (comp (ref "C151")
      (value "0.1u")
      (footprint "eagle-import:C0603")
      (libsource (lib "eagle-import") (part "C-EUC0603"))
    )
    (comp (ref "C152")
      (value "1u")
      (footprint "eagle-import:C0603")
      (libsource (lib "eagle-import") (part "C-EUC0603"))
    )
    (comp (ref "C153")
      (value "0.1u")
      (footprint "eagle-import:C0603")
      (libsource (lib "eagle-import") (part "C-EUC0603"))
    )
    (comp (ref "C154")
      (value "1u")
      (footprint "eagle-import:C0603")
      (libsource (lib "eagle-import") (part "C-EUC0603"))
    )
    (comp (ref "C155")
      (value "1u")
      (footprint "eagle-import:C0603")
      (libsource (lib "eagle-import") (part "C-EUC0603"))
    )
    (comp (ref "C156")
      (value "1u")
      (footprint "eagle-import:C0603")
      (libsource (lib "eagle-import") (part "C-EUC0603"))
    )
    (comp (ref "C157")
      (value "1u")
      (footprint "eagle-import:C0603")
      (libsource (lib "eagle-import") (part "C-EUC0603"))
    )
    (comp (ref "C158")
      (value "10u")
      (footprint "eagle-import:C0805")
      (libsource (lib "eagle-import") (part "C-EUC0805"))
    )
    (comp (ref "C159")
      (value "0.1u")
      (footprint "eagle-import:C0603")
      (libsource (lib "eagle-import") (part "C-EUC0603"))
    )
    (comp (ref "C160")
      (value "1u")
      (footprint "eagle-import:C0603")
      (libsource (lib "eagle-import") (part "C-EUC0603"))
    )
    (comp (ref "C161")
      (value "0.1u")
      (footprint "eagle-import:C0603")
      (libsource (lib "eagle-import") (part "C-EUC0603"))
    )
    (comp (ref "C162")
      (value "1u")
      (footprint "eagle-import:C0603")
      (libsource (lib "eagle-import") (part "C-EUC0603"))
    )
    (comp (ref "C163")
      (value "1u")
      (footprint "eagle-import:C0603")
      (libsource (lib "eagle-import") (part "C-EUC0603"))
    )
    (comp (ref "C164")
      (value "1u")
      (footprint "eagle-import:C0603")
      (libsource (lib "eagle-import") (part "C-EUC0603"))
    )
    (comp (ref "C165")
      (value "1u")
      (footprint "eagle-import:C0603")
      (libsource (lib "eagle-import") (part "C-EUC0603"))
    )
    (comp (ref "C166")
      (value "10u")
      (footprint "eagle-import:C0805")
      (libsource (lib "eagle-import") (part "C-EUC0805"))
    )
    (comp (ref "C167")
      (value "0.1u")
      (footprint "eagle-import:C0603")
      (libsource (lib "eagle-import") (part "C-EUC0603"))
    )
    (comp (ref "C168")
      (value "1u")
      (footprint "eagle-import:C0603")
      (libsource (lib "eagle-import") (part "C-EUC0603"))
    )
    (comp (ref "C169")
      (value "0.1u")
      (footprint "eagle-import:C0603")
      (libsource (lib "eagle-import") (part "C-EUC0603"))
    )
    (comp (ref "C170")
      (value "1u")
      (footprint "eagle-import:C0603")
      (libsource (lib "eagle-import") (part "C-EUC0603"))
    )
    (comp (ref "C171")
      (value "1u")
      (footprint "eagle-import:C0603")
      (libsource (lib "eagle-import") (part "C-EUC0603"))
    )
    (comp (ref "C172")
      (value "1u")
      (footprint "eagle-import:C0603")
      (libsource (lib "eagle-import") (part "C-EUC0603"))
    )
    (comp (ref "C173")
      (value "1u")
      (footprint "eagle-import:C0603")
      (libsource (lib "eagle-import") (part "C-EUC0603"))
    )
    (comp (ref "C174")
      (value "10u")
      (footprint "eagle-import:C0805")
      (libsource (lib "eagle-import") (part "C-EUC0805"))
    )
    (comp (ref "C175")
      (value "0.1u")
      (footprint "eagle-import:C0603")
      (libsource (lib "eagle-import") (part "C-EUC0603"))
    )
    (comp (ref "C176")
      (value "1u")
      (footprint "eagle-import:C0603")
      (libsource (lib "eagle-import") (part "C-EUC0603"))
    )
    (comp (ref "C177")
      (value "0.1u")
      (footprint "eagle-import:C0603")
      (libsource (lib "eagle-import") (part "C-EUC0603"))
    )
    (comp (ref "C178")
      (value "1u")
      (footprint "eagle-import:C0603")
      (libsource (lib "eagle-import") (part "C-EUC0603"))
    )
    (comp (ref "C179")
      (value "1u")
      (footprint "eagle-import:C0603")
      (libsource (lib "eagle-import") (part "C-EUC0603"))
    )
    (comp (ref "C180")
      (value "1u")
      (footprint "eagle-import:C0603")
      (libsource (lib "eagle-import") (part "C-EUC0603"))
    )
    (comp (ref "C181")
      (value "1u")
      (footprint "eagle-import:C0603")
      (libsource (lib "eagle-import") (part "C-EUC0603"))
    )
    (comp (ref "C182")
      (value "10u")
      (footprint "eagle-import:C0805")
      (libsource (lib "eagle-import") (part "C-EUC0805"))
    )
    (comp (ref "C183")
      (value "0.1u")
      (footprint "eagle-import:C0603")
      (libsource (lib "eagle-import") (part "C-EUC0603"))
    )
    (comp (ref "C184")
      (value "1u")
      (footprint "eagle-import:C0603")
      (libsource (lib "eagle-import") (part "C-EUC0603"))
    )
    (comp (ref "C185")
      (value "0.1u")
      (footprint "eagle-import:C0603")
      (libsource (lib "eagle-import") (part "C-EUC0603"))
    )
    (comp (ref "C186")
      (value "1u")
      (footprint "eagle-import:C0603")
      (libsource (lib "eagle-import") (part "C-EUC0603"))
    )
    (comp (ref "C187")
      (value "1u")
      (footprint "eagle-import:C0603")
      (libsource (lib "eagle-import") (part "C-EUC0603"))
    )
    (comp (ref "C188")
      (value "1u")
      (footprint "eagle-import:C0603")
      (libsource (lib "eagle-import") (part "C-EUC0603"))
    )
    (comp (ref "C189")
      (value "1u")
      (footprint "eagle-import:C0603")
      (libsource (lib "eagle-import") (part "C-EUC0603"))
    )
    (comp (ref "C190")
      (value "10u")
      (footprint "eagle-import:C0805")
      (libsource (lib "eagle-import") (part "C-EUC0805"))
    )
    (comp (ref "C191")
      (value "0.1u")
      (footprint "eagle-import:C0603")
      (libsource (lib "eagle-import") (part "C-EUC0603"))
    )
    (comp (ref "C192")
      (value "1u")
      (footprint "eagle-import:C0603")
      (libsource (lib "eagle-import") (part "C-EUC0603"))
    )
    (comp (ref "C193")
      (value "0.1u")
      (footprint "eagle-import:C0603")
      (libsource (lib "eagle-import") (part "C-EUC0603"))
    )
    (comp (ref "C194")
      (value "1u")
      (footprint "eagle-import:C0603")
      (libsource (lib "eagle-import") (part "C-EUC0603"))
    )
    (comp (ref "C195")
      (value "1u")
      (footprint "eagle-import:C0603")
      (libsource (lib "eagle-import") (part "C-EUC0603"))
    )
    (comp (ref "C196")
      (value "1u")
      (footprint "eagle-import:C0603")
      (libsource (lib "eagle-import") (part "C-EUC0603"))
    )
    (comp (ref "C197")
      (value "1u")
      (footprint "eagle-import:C0603")
      (libsource (lib "eagle-import") (part "C-EUC0603"))
    )
    (comp (ref "C198")
      (value "10u")
      (footprint "eagle-import:C0805")
      (libsource (lib "eagle-import") (part "C-EUC0805"))
    )
    (comp (ref "C199")
      (value "0.1u")
      (footprint "eagle-import:C0603")
      (libsource (lib "eagle-import") (part "C-EUC0603"))
    )
    (comp (ref "C200")
      (value "1u")
      (footprint "eagle-import:C0603")
      (libsource (lib "eagle-import") (part "C-EUC0603"))
    )
    (comp (ref "C201")
      (value "0.1u")
      (footprint "eagle-import:C0603")
      (libsource (lib "eagle-import") (part "C-EUC0603"))
    )
    (comp (ref "C202")
      (value "1u")
      (footprint "eagle-import:C0603")
      (libsource (lib "eagle-import") (part "C-EUC0603"))
    )
    (comp (ref "C203")
      (value "1u")
      (footprint "eagle-import:C0603")
      (libsource (lib "eagle-import") (part "C-EUC0603"))
    )
    (comp (ref "C204")
      (value "1u")
      (footprint "eagle-import:C0603")
      (libsource (lib "eagle-import") (part "C-EUC0603"))
    )
    (comp (ref "C205")
      (value "1u")
      (footprint "eagle-import:C0603")
      (libsource (lib "eagle-import") (part "C-EUC0603"))
    )
    (comp (ref "C206")
      (value "10u")
      (footprint "eagle-import:C0805")
      (libsource (lib "eagle-import") (part "C-EUC0805"))
    )
    (comp (ref "C207")
      (value "0.1u")
      (footprint "eagle-import:C0603")
      (libsource (lib "eagle-import") (part "C-EUC0603"))
    )
    (comp (ref "C208")
      (value "1u")
      (footprint "eagle-import:C0603")
      (libsource (lib "eagle-import") (part "C-EUC0603"))
    )
    (comp (ref "C209")
      (value "0.1u")
      (footprint "eagle-import:C0603")
      (libsource (lib "eagle-import") (part "C-EUC0603"))
    )
    (comp (ref "C210")
      (value "1u")
      (footprint "eagle-import:C0603")
      (libsource (lib "eagle-import") (part "C-EUC0603"))
    )
    (comp (ref "C211")
      (value "1u")
      (footprint "eagle-import:C0603")
      (libsource (lib "eagle-import") (part "C-EUC0603"))
    )
    (comp (ref "C212")
      (value "1u")
      (footprint "eagle-import:C0603")
      (libsource (lib "eagle-import") (part "C-EUC0603"))
    )
    (comp (ref "C213")
      (value "1u")
      (footprint "eagle-import:C0603")
      (libsource (lib "eagle-import") (part "C-EUC0603"))
    )
    (comp (ref "C214")
      (value "10u")
      (footprint "eagle-import:C0805")
      (libsource (lib "eagle-import") (part "C-EUC0805"))
    )
    (comp (ref "C215")
      (value "0.1u")
      (footprint "eagle-import:C0603")
      (libsource (lib "eagle-import") (part "C-EUC0603"))
    )
    (comp (ref "C216")
      (value "1u")
      (footprint "eagle-import:C0603")
      (libsource (lib "eagle-import") (part "C-EUC0603"))
    )
    (comp (ref "C217")
      (value "0.1u")
      (footprint "eagle-import:C0603")
      (libsource (lib "eagle-import") (part "C-EUC0603"))
    )
    (comp (ref "C218")
      (value "1u")
      (footprint "eagle-import:C0603")
      (libsource (lib "eagle-import") (part "C-EUC0603"))
    )
    (comp (ref "C219")
      (value "1u")
      (footprint "eagle-import:C0603")
      (libsource (lib "eagle-import") (part "C-EUC0603"))
    )
    (comp (ref "C220")
      (value "1u")
      (footprint "eagle-import:C0603")
      (libsource (lib "eagle-import") (part "C-EUC0603"))
    )
    (comp (ref "C221")
      (value "1u")
      (footprint "eagle-import:C0603")
      (libsource (lib "eagle-import") (part "C-EUC0603"))
    )
    (comp (ref "C222")
      (value "10u")
      (footprint "eagle-import:C0805")
      (libsource (lib "eagle-import") (part "C-EUC0805"))
    )
    (comp (ref "C223")
      (value "0.1u")
      (footprint "eagle-import:C0603")
      (libsource (lib "eagle-import") (part "C-EUC0603"))
    )
    (comp (ref "C224")
      (value "1u")
      (footprint "eagle-import:C0603")
      (libsource (lib "eagle-import") (part "C-EUC0603"))
    )
    (comp (ref "C225")
      (value "0.1u")
      (footprint "eagle-import:C0603")
      (libsource (lib "eagle-import") (part "C-EUC0603"))
    )
    (comp (ref "C226")
      (value "1u")
      (footprint "eagle-import:C0603")
      (libsource (lib "eagle-import") (part "C-EUC0603"))
    )
    (comp (ref "C227")
      (value "1u")
      (footprint "eagle-import:C0603")
      (libsource (lib "eagle-import") (part "C-EUC0603"))
    )
    (comp (ref "C228")
      (value "1u")
      (footprint "eagle-import:C0603")
      (libsource (lib "eagle-import") (part "C-EUC0603"))
    )
    (comp (ref "C229")
      (value "1u")
      (footprint "eagle-import:C0603")
      (libsource (lib "eagle-import") (part "C-EUC0603"))
    )
    (comp (ref "C230")
      (value "10u")
      (footprint "eagle-import:C0805")
      (libsource (lib "eagle-import") (part "C-EUC0805"))
    )
    (comp (ref "C231")
      (value "0.1u")
      (footprint "eagle-import:C0603")
      (libsource (lib "eagle-import") (part "C-EUC0603"))
    )
    (comp (ref "C232")
      (value "1u")
      (footprint "eagle-import:C0603")
      (libsource (lib "eagle-import") (part "C-EUC0603"))
    )
    (comp (ref "H1")
      (value "MOUNT-HOLE3.0")
      (footprint "eagle-import:3,0")
      (libsource (lib "eagle-import") (part "MOUNT-HOLE3.0"))
    )
    (comp (ref "H2")
      (value "MOUNT-HOLE3.0")
      (footprint "eagle-import:3,0")
      (libsource (lib "eagle-import") (part "MOUNT-HOLE3.0"))
    )
    (comp (ref "IC1")
      (value "AD9834")
      (footprint "eagle-import:TSSOP20")
      (fields (field (name "MF") "Analog Devices"))
      (libsource (lib "eagle-import") (part "AD9834"))
    )
    (comp (ref "IC2")
      (value "AD9834")
      (footprint "eagle-import:TSSOP20")
      (fields (field (name "MF") "Analog Devices"))
      (libsource (lib "eagle-import") (part "AD9834"))
    )
    (comp (ref "IC3")
      (value "AD9834")
      (footprint "eagle-import:TSSOP20")
      (fields (field (name "MF") "Analog Devices"))
      (libsource (lib "eagle-import") (part "AD9834"))
    )
    (comp (ref "IC4")
      (value "AD9834")
      (footprint "eagle-import:TSSOP20")
      (fields (field (name "MF") "Analog Devices"))
      (libsource (lib "eagle-import") (part "AD9834"))
    )
    (comp (ref "IC5")
      (value "AD9834")
      (footprint "eagle-import:TSSOP20")
      (fields (field (name "MF") "Analog Devices"))
      (libsource (lib "eagle-import") (part "AD9834"))
    )
    (comp (ref "IC6")
      (value "AD9834")
      (footprint "eagle-import:TSSOP20")
      (fields (field (name "MF") "Analog Devices"))
      (libsource (lib "eagle-import") (part "AD9834"))
    )
    (comp (ref "IC7")
      (value "AD9834")
      (footprint "eagle-import:TSSOP20")
      (fields (field (name "MF") "Analog Devices"))
      (libsource (lib "eagle-import") (part "AD9834"))
    )
    (comp (ref "IC8")
      (value "AD9834")
      (footprint "eagle-import:TSSOP20")
      (fields (field (name "MF") "Analog Devices"))
      (libsource (lib "eagle-import") (part "AD9834"))
    )
    (comp (ref "IC9")
      (value "AD9834")
      (footprint "eagle-import:TSSOP20")
      (fields (field (name "MF") "Analog Devices"))
      (libsource (lib "eagle-import") (part "AD9834"))
    )
    (comp (ref "IC10")
      (value "AD9834")
      (footprint "eagle-import:TSSOP20")
      (fields (field (name "MF") "Analog Devices"))
      (libsource (lib "eagle-import") (part "AD9834"))
    )
    (comp (ref "IC11")
      (value "AD9834")
      (footprint "eagle-import:TSSOP20")
      (fields (field (name "MF") "Analog Devices"))
      (libsource (lib "eagle-import") (part "AD9834"))
    )
    (comp (ref "IC12")
      (value "AD9834")
      (footprint "eagle-import:TSSOP20")
      (fields (field (name "MF") "Analog Devices"))
      (libsource (lib "eagle-import") (part "AD9834"))
    )
    (comp (ref "IC13")
      (value "AD9834")
      (footprint "eagle-import:TSSOP20")
      (fields (field (name "MF") "Analog Devices"))
      (libsource (lib "eagle-import") (part "AD9834"))
    )
    (comp (ref "IC14")
      (value "AD9834")
      (footprint "eagle-import:TSSOP20")
      (fields (field (name "MF") "Analog Devices"))
      (libsource (lib "eagle-import") (part "AD9834"))
    )
    (comp (ref "IC16")
      (value "AD9834")
      (footprint "eagle-import:TSSOP20")
      (fields (field (name "MF") "Analog Devices"))
      (libsource (lib "eagle-import") (part "AD9834"))
    )
    (comp (ref "IC17")
      (value "AD9834")
      (footprint "eagle-import:TSSOP20")
      (fields (field (name "MF") "Analog Devices"))
      (libsource (lib "eagle-import") (part "AD9834"))
    )
    (comp (ref "J1")
      (value "6130XX21021_61301421021")
      (footprint "eagle-import:61301421021")
      (libsource (lib "eagle-import") (part "6130XX21021_61301421021"))
    )
    (comp (ref "J2")
      (value "6130XX21021_61301621021")
      (footprint "eagle-import:61301621021")
      (libsource (lib "eagle-import") (part "6130XX21021_61301621021"))
    )
    (comp (ref "J4")
      (value "6130XX21021_61301421021")
      (footprint "eagle-import:61301421021")
      (libsource (lib "eagle-import") (part "6130XX21021_61301421021"))
    )
    (comp (ref "J7")
      (value "6130XX21021_61301621021")
      (footprint "eagle-import:61301621021")
      (libsource (lib "eagle-import") (part "6130XX21021_61301621021"))
    )
    (comp (ref "JP1")
      (value "PINHD-1X2")
      (footprint "eagle-import:1X02")
      (libsource (lib "eagle-import") (part "PINHD-1X2"))
    )
    (comp (ref "JP2")
      (value "PINHD-1X2")
      (footprint "eagle-import:1X02")
      (libsource (lib "eagle-import") (part "PINHD-1X2"))
    )
    (comp (ref "JP3")
      (value "PINHD-1X2")
      (footprint "eagle-import:1X02")
      (libsource (lib "eagle-import") (part "PINHD-1X2"))
    )
    (comp (ref "JP4")
      (value "PINHD-1X2")
      (footprint "eagle-import:1X02")
      (libsource (lib "eagle-import") (part "PINHD-1X2"))
    )
    (comp (ref "JP5")
      (value "PINHD-1X2")
      (footprint "eagle-import:1X02")
      (libsource (lib "eagle-import") (part "PINHD-1X2"))
    )
    (comp (ref "JP6")
      (value "PINHD-1X2")
      (footprint "eagle-import:1X02")
      (libsource (lib "eagle-import") (part "PINHD-1X2"))
    )
    (comp (ref "JP7")
      (value "PINHD-1X2")
      (footprint "eagle-import:1X02")
      (libsource (lib "eagle-import") (part "PINHD-1X2"))
    )
    (comp (ref "JP8")
      (value "PINHD-1X2")
      (footprint "eagle-import:1X02")
      (libsource (lib "eagle-import") (part "PINHD-1X2"))
    )
    (comp (ref "JP9")
      (value "PINHD-1X2")
      (footprint "eagle-import:1X02")
      (libsource (lib "eagle-import") (part "PINHD-1X2"))
    )
    (comp (ref "JP10")
      (value "PINHD-1X2")
      (footprint "eagle-import:1X02")
      (libsource (lib "eagle-import") (part "PINHD-1X2"))
    )
    (comp (ref "JP11")
      (value "PINHD-1X2")
      (footprint "eagle-import:1X02")
      (libsource (lib "eagle-import") (part "PINHD-1X2"))
    )
    (comp (ref "JP12")
      (value "PINHD-1X2")
      (footprint "eagle-import:1X02")
      (libsource (lib "eagle-import") (part "PINHD-1X2"))
    )
    (comp (ref "JP13")
      (value "PINHD-1X2")
      (footprint "eagle-import:1X02")
      (libsource (lib "eagle-import") (part "PINHD-1X2"))
    )
    (comp (ref "JP14")
      (value "PINHD-1X2")
      (footprint "eagle-import:1X02")
      (libsource (lib "eagle-import") (part "PINHD-1X2"))
    )
    (comp (ref "JP15")
      (value "PINHD-1X2")
      (footprint "eagle-import:1X02")
      (libsource (lib "eagle-import") (part "PINHD-1X2"))
    )
    (comp (ref "JP16")
      (value "PINHD-1X2")
      (footprint "eagle-import:1X02")
      (libsource (lib "eagle-import") (part "PINHD-1X2"))
    )
    (comp (ref "LDO")
      (value "TLV75525PDBVR")
      (footprint "eagle-import:SOT95P280X145-5N")
      (libsource (lib "eagle-import") (part "TLV75525PDBVR"))
    )
    (comp (ref "LDO2")
      (value "TLV75525PDBVR")
      (footprint "eagle-import:SOT95P280X145-5N")
      (libsource (lib "eagle-import") (part "TLV75525PDBVR"))
    )
    (comp (ref "LDO3")
      (value "TLV75525PDBVR")
      (footprint "eagle-import:SOT95P280X145-5N")
      (libsource (lib "eagle-import") (part "TLV75525PDBVR"))
    )
    (comp (ref "LDO4")
      (value "TLV75525PDBVR")
      (footprint "eagle-import:SOT95P280X145-5N")
      (libsource (lib "eagle-import") (part "TLV75525PDBVR"))
    )
    (comp (ref "LDO5")
      (value "TLV75525PDBVR")
      (footprint "eagle-import:SOT95P280X145-5N")
      (libsource (lib "eagle-import") (part "TLV75525PDBVR"))
    )
    (comp (ref "LDO6")
      (value "TLV75525PDBVR")
      (footprint "eagle-import:SOT95P280X145-5N")
      (libsource (lib "eagle-import") (part "TLV75525PDBVR"))
    )
    (comp (ref "LDO7")
      (value "TLV75525PDBVR")
      (footprint "eagle-import:SOT95P280X145-5N")
      (libsource (lib "eagle-import") (part "TLV75525PDBVR"))
    )
    (comp (ref "LDO8")
      (value "TLV75525PDBVR")
      (footprint "eagle-import:SOT95P280X145-5N")
      (libsource (lib "eagle-import") (part "TLV75525PDBVR"))
    )
    (comp (ref "LDO9")
      (value "TLV75525PDBVR")
      (footprint "eagle-import:SOT95P280X145-5N")
      (libsource (lib "eagle-import") (part "TLV75525PDBVR"))
    )
    (comp (ref "LDO10")
      (value "TLV75525PDBVR")
      (footprint "eagle-import:SOT95P280X145-5N")
      (libsource (lib "eagle-import") (part "TLV75525PDBVR"))
    )
    (comp (ref "LDO11")
      (value "TLV75525PDBVR")
      (footprint "eagle-import:SOT95P280X145-5N")
      (libsource (lib "eagle-import") (part "TLV75525PDBVR"))
    )
    (comp (ref "LDO12")
      (value "TLV75525PDBVR")
      (footprint "eagle-import:SOT95P280X145-5N")
      (libsource (lib "eagle-import") (part "TLV75525PDBVR"))
    )
    (comp (ref "LDO13")
      (value "TLV75525PDBVR")
      (footprint "eagle-import:SOT95P280X145-5N")
      (libsource (lib "eagle-import") (part "TLV75525PDBVR"))
    )
    (comp (ref "LDO14")
      (value "TLV75525PDBVR")
      (footprint "eagle-import:SOT95P280X145-5N")
      (libsource (lib "eagle-import") (part "TLV75525PDBVR"))
    )
    (comp (ref "LDO15")
      (value "TLV75525PDBVR")
      (footprint "eagle-import:SOT95P280X145-5N")
      (libsource (lib "eagle-import") (part "TLV75525PDBVR"))
    )
    (comp (ref "LDO16")
      (value "TLV75525PDBVR")
      (footprint "eagle-import:SOT95P280X145-5N")
      (libsource (lib "eagle-import") (part "TLV75525PDBVR"))
    )
    (comp (ref "LSP1")
      (value "LSP10")
      (footprint "eagle-import:LSP10")
      (libsource (lib "eagle-import") (part "LSP10"))
    )
    (comp (ref "LSP2")
      (value "LSP10")
      (footprint "eagle-import:LSP10")
      (libsource (lib "eagle-import") (part "LSP10"))
    )
    (comp (ref "LSP3")
      (value "LSP10")
      (footprint "eagle-import:LSP10")
      (libsource (lib "eagle-import") (part "LSP10"))
    )
    (comp (ref "LSP4")
      (value "LSP10")
      (footprint "eagle-import:LSP10")
      (libsource (lib "eagle-import") (part "LSP10"))
    )
    (comp (ref "LSP5")
      (value "LSP10")
      (footprint "eagle-import:LSP10")
      (libsource (lib "eagle-import") (part "LSP10"))
    )
    (comp (ref "LSP6")
      (value "LSP10")
      (footprint "eagle-import:LSP10")
      (libsource (lib "eagle-import") (part "LSP10"))
    )
    (comp (ref "LSP7")
      (value "LSP10")
      (footprint "eagle-import:LSP10")
      (libsource (lib "eagle-import") (part "LSP10"))
    )
    (comp (ref "LSP8")
      (value "LSP10")
      (footprint "eagle-import:LSP10")
      (libsource (lib "eagle-import") (part "LSP10"))
    )
    (comp (ref "LSP9")
      (value "LSP10")
      (footprint "eagle-import:LSP10")
      (libsource (lib "eagle-import") (part "LSP10"))
    )
    (comp (ref "LSP10")
      (value "LSP10")
      (footprint "eagle-import:LSP10")
      (libsource (lib "eagle-import") (part "LSP10"))
    )
    (comp (ref "LSP11")
      (value "LSP10")
      (footprint "eagle-import:LSP10")
      (libsource (lib "eagle-import") (part "LSP10"))
    )
    (comp (ref "LSP12")
      (value "LSP10")
      (footprint "eagle-import:LSP10")
      (libsource (lib "eagle-import") (part "LSP10"))
    )
    (comp (ref "LSP13")
      (value "LSP10")
      (footprint "eagle-import:LSP10")
      (libsource (lib "eagle-import") (part "LSP10"))
    )
    (comp (ref "LSP14")
      (value "LSP10")
      (footprint "eagle-import:LSP10")
      (libsource (lib "eagle-import") (part "LSP10"))
    )
    (comp (ref "LSP15")
      (value "LSP10")
      (footprint "eagle-import:LSP10")
      (libsource (lib "eagle-import") (part "LSP10"))
    )
    (comp (ref "LSP16")
      (value "LSP10")
      (footprint "eagle-import:LSP10")
      (libsource (lib "eagle-import") (part "LSP10"))
    )
    (comp (ref "LSP17")
      (value "LSP10")
      (footprint "eagle-import:LSP10")
      (libsource (lib "eagle-import") (part "LSP10"))
    )
    (comp (ref "LSP18")
      (value "LSP10")
      (footprint "eagle-import:LSP10")
      (libsource (lib "eagle-import") (part "LSP10"))
    )
    (comp (ref "LSP19")
      (value "LSP10")
      (footprint "eagle-import:LSP10")
      (libsource (lib "eagle-import") (part "LSP10"))
    )
    (comp (ref "LSP20")
      (value "LSP10")
      (footprint "eagle-import:LSP10")
      (libsource (lib "eagle-import") (part "LSP10"))
    )
    (comp (ref "R1")
      (value "6.8k")
      (footprint "eagle-import:R0603")
      (libsource (lib "eagle-import") (part "R-EU_R0603"))
    )
    (comp (ref "R2")
      (value "6.8k")
      (footprint "eagle-import:R0603")
      (libsource (lib "eagle-import") (part "R-EU_R0603"))
    )
    (comp (ref "R3")
      (value "TBD")
      (footprint "eagle-import:R0603")
      (libsource (lib "eagle-import") (part "R-EU_R0603"))
    )
    (comp (ref "R4")
      (value "200")
      (footprint "eagle-import:R0603")
      (libsource (lib "eagle-import") (part "R-EU_R0603"))
    )
    (comp (ref "R5")
      (value "200")
      (footprint "eagle-import:R0603")
      (libsource (lib "eagle-import") (part "R-EU_R0603"))
    )
    (comp (ref "R6")
      (value "200")
      (footprint "eagle-import:R0603")
      (libsource (lib "eagle-import") (part "R-EU_R0603"))
    )
    (comp (ref "R7")
      (value "200")
      (footprint "eagle-import:R0603")
      (libsource (lib "eagle-import") (part "R-EU_R0603"))
    )
    (comp (ref "R8")
      (value "TBD")
      (footprint "eagle-import:R0603")
      (libsource (lib "eagle-import") (part "R-EU_R0603"))
    )
    (comp (ref "R9")
      (value "6.8k")
      (footprint "eagle-import:R0603")
      (libsource (lib "eagle-import") (part "R-EU_R0603"))
    )
    (comp (ref "R10")
      (value "200")
      (footprint "eagle-import:R0603")
      (libsource (lib "eagle-import") (part "R-EU_R0603"))
    )
    (comp (ref "R11")
      (value "200")
      (footprint "eagle-import:R0603")
      (libsource (lib "eagle-import") (part "R-EU_R0603"))
    )
    (comp (ref "R12")
      (value "TBD")
      (footprint "eagle-import:R0603")
      (libsource (lib "eagle-import") (part "R-EU_R0603"))
    )
    (comp (ref "R13")
      (value "6.8k")
      (footprint "eagle-import:R0603")
      (libsource (lib "eagle-import") (part "R-EU_R0603"))
    )
    (comp (ref "R14")
      (value "200")
      (footprint "eagle-import:R0603")
      (libsource (lib "eagle-import") (part "R-EU_R0603"))
    )
    (comp (ref "R15")
      (value "200")
      (footprint "eagle-import:R0603")
      (libsource (lib "eagle-import") (part "R-EU_R0603"))
    )
    (comp (ref "R16")
      (value "TBD")
      (footprint "eagle-import:R0603")
      (libsource (lib "eagle-import") (part "R-EU_R0603"))
    )
    (comp (ref "R17")
      (value "6.8k")
      (footprint "eagle-import:R0603")
      (libsource (lib "eagle-import") (part "R-EU_R0603"))
    )
    (comp (ref "R18")
      (value "200")
      (footprint "eagle-import:R0603")
      (libsource (lib "eagle-import") (part "R-EU_R0603"))
    )
    (comp (ref "R19")
      (value "200")
      (footprint "eagle-import:R0603")
      (libsource (lib "eagle-import") (part "R-EU_R0603"))
    )
    (comp (ref "R20")
      (value "TBD")
      (footprint "eagle-import:R0603")
      (libsource (lib "eagle-import") (part "R-EU_R0603"))
    )
    (comp (ref "R21")
      (value "6.8k")
      (footprint "eagle-import:R0603")
      (libsource (lib "eagle-import") (part "R-EU_R0603"))
    )
    (comp (ref "R22")
      (value "200")
      (footprint "eagle-import:R0603")
      (libsource (lib "eagle-import") (part "R-EU_R0603"))
    )
    (comp (ref "R23")
      (value "200")
      (footprint "eagle-import:R0603")
      (libsource (lib "eagle-import") (part "R-EU_R0603"))
    )
    (comp (ref "R24")
      (value "TBD")
      (footprint "eagle-import:R0603")
      (libsource (lib "eagle-import") (part "R-EU_R0603"))
    )
    (comp (ref "R25")
      (value "6.8k")
      (footprint "eagle-import:R0603")
      (libsource (lib "eagle-import") (part "R-EU_R0603"))
    )
    (comp (ref "R26")
      (value "200")
      (footprint "eagle-import:R0603")
      (libsource (lib "eagle-import") (part "R-EU_R0603"))
    )
    (comp (ref "R27")
      (value "200")
      (footprint "eagle-import:R0603")
      (libsource (lib "eagle-import") (part "R-EU_R0603"))
    )
    (comp (ref "R28")
      (value "TBD")
      (footprint "eagle-import:R0603")
      (libsource (lib "eagle-import") (part "R-EU_R0603"))
    )
    (comp (ref "R29")
      (value "6.8k")
      (footprint "eagle-import:R0603")
      (libsource (lib "eagle-import") (part "R-EU_R0603"))
    )
    (comp (ref "R30")
      (value "200")
      (footprint "eagle-import:R0603")
      (libsource (lib "eagle-import") (part "R-EU_R0603"))
    )
    (comp (ref "R31")
      (value "200")
      (footprint "eagle-import:R0603")
      (libsource (lib "eagle-import") (part "R-EU_R0603"))
    )
    (comp (ref "R32")
      (value "TBD")
      (footprint "eagle-import:R0603")
      (libsource (lib "eagle-import") (part "R-EU_R0603"))
    )
    (comp (ref "R33")
      (value "6.8k")
      (footprint "eagle-import:R0603")
      (libsource (lib "eagle-import") (part "R-EU_R0603"))
    )
    (comp (ref "R34")
      (value "200")
      (footprint "eagle-import:R0603")
      (libsource (lib "eagle-import") (part "R-EU_R0603"))
    )
    (comp (ref "R35")
      (value "200")
      (footprint "eagle-import:R0603")
      (libsource (lib "eagle-import") (part "R-EU_R0603"))
    )
    (comp (ref "R36")
      (value "TBD")
      (footprint "eagle-import:R0603")
      (libsource (lib "eagle-import") (part "R-EU_R0603"))
    )
    (comp (ref "R37")
      (value "6.8k")
      (footprint "eagle-import:R0603")
      (libsource (lib "eagle-import") (part "R-EU_R0603"))
    )
    (comp (ref "R38")
      (value "200")
      (footprint "eagle-import:R0603")
      (libsource (lib "eagle-import") (part "R-EU_R0603"))
    )
    (comp (ref "R39")
      (value "200")
      (footprint "eagle-import:R0603")
      (libsource (lib "eagle-import") (part "R-EU_R0603"))
    )
    (comp (ref "R40")
      (value "TBD")
      (footprint "eagle-import:R0603")
      (libsource (lib "eagle-import") (part "R-EU_R0603"))
    )
    (comp (ref "R41")
      (value "6.8k")
      (footprint "eagle-import:R0603")
      (libsource (lib "eagle-import") (part "R-EU_R0603"))
    )
    (comp (ref "R42")
      (value "200")
      (footprint "eagle-import:R0603")
      (libsource (lib "eagle-import") (part "R-EU_R0603"))
    )
    (comp (ref "R43")
      (value "200")
      (footprint "eagle-import:R0603")
      (libsource (lib "eagle-import") (part "R-EU_R0603"))
    )
    (comp (ref "R44")
      (value "TBD")
      (footprint "eagle-import:R0603")
      (libsource (lib "eagle-import") (part "R-EU_R0603"))
    )
    (comp (ref "R45")
      (value "6.8k")
      (footprint "eagle-import:R0603")
      (libsource (lib "eagle-import") (part "R-EU_R0603"))
    )
    (comp (ref "R46")
      (value "200")
      (footprint "eagle-import:R0603")
      (libsource (lib "eagle-import") (part "R-EU_R0603"))
    )
    (comp (ref "R47")
      (value "200")
      (footprint "eagle-import:R0603")
      (libsource (lib "eagle-import") (part "R-EU_R0603"))
    )
    (comp (ref "R48")
      (value "TBD")
      (footprint "eagle-import:R0603")
      (libsource (lib "eagle-import") (part "R-EU_R0603"))
    )
    (comp (ref "R49")
      (value "6.8k")
      (footprint "eagle-import:R0603")
      (libsource (lib "eagle-import") (part "R-EU_R0603"))
    )
    (comp (ref "R50")
      (value "200")
      (footprint "eagle-import:R0603")
      (libsource (lib "eagle-import") (part "R-EU_R0603"))
    )
    (comp (ref "R51")
      (value "200")
      (footprint "eagle-import:R0603")
      (libsource (lib "eagle-import") (part "R-EU_R0603"))
    )
    (comp (ref "R52")
      (value "TBD")
      (footprint "eagle-import:R0603")
      (libsource (lib "eagle-import") (part "R-EU_R0603"))
    )
    (comp (ref "R53")
      (value "6.8k")
      (footprint "eagle-import:R0603")
      (libsource (lib "eagle-import") (part "R-EU_R0603"))
    )
    (comp (ref "R54")
      (value "200")
      (footprint "eagle-import:R0603")
      (libsource (lib "eagle-import") (part "R-EU_R0603"))
    )
    (comp (ref "R55")
      (value "200")
      (footprint "eagle-import:R0603")
      (libsource (lib "eagle-import") (part "R-EU_R0603"))
    )
    (comp (ref "R56")
      (value "TBD")
      (footprint "eagle-import:R0603")
      (libsource (lib "eagle-import") (part "R-EU_R0603"))
    )
    (comp (ref "R57")
      (value "R-EU_R0603")
      (footprint "eagle-import:R0603")
      (libsource (lib "eagle-import") (part "R-EU_R0603"))
    )
    (comp (ref "R59")
      (value "R-EU_R0603")
      (footprint "eagle-import:R0603")
      (libsource (lib "eagle-import") (part "R-EU_R0603"))
    )
    (comp (ref "R60")
      (value "R-EU_R0603")
      (footprint "eagle-import:R0603")
      (libsource (lib "eagle-import") (part "R-EU_R0603"))
    )
    (comp (ref "R61")
      (value "6.8k")
      (footprint "eagle-import:R0603")
      (libsource (lib "eagle-import") (part "R-EU_R0603"))
    )
    (comp (ref "R62")
      (value "200")
      (footprint "eagle-import:R0603")
      (libsource (lib "eagle-import") (part "R-EU_R0603"))
    )
    (comp (ref "R63")
      (value "200")
      (footprint "eagle-import:R0603")
      (libsource (lib "eagle-import") (part "R-EU_R0603"))
    )
    (comp (ref "R64")
      (value "TBD")
      (footprint "eagle-import:R0603")
      (libsource (lib "eagle-import") (part "R-EU_R0603"))
    )
    (comp (ref "R65")
      (value "6.8k")
      (footprint "eagle-import:R0603")
      (libsource (lib "eagle-import") (part "R-EU_R0603"))
    )
    (comp (ref "R66")
      (value "200")
      (footprint "eagle-import:R0603")
      (libsource (lib "eagle-import") (part "R-EU_R0603"))
    )
    (comp (ref "R67")
      (value "200")
      (footprint "eagle-import:R0603")
      (libsource (lib "eagle-import") (part "R-EU_R0603"))
    )
    (comp (ref "R68")
      (value "TBD")
      (footprint "eagle-import:R0603")
      (libsource (lib "eagle-import") (part "R-EU_R0603"))
    )
    (comp (ref "R69")
      (value "R-EU_R0603")
      (footprint "eagle-import:R0603")
      (libsource (lib "eagle-import") (part "R-EU_R0603"))
    )
    (comp (ref "R70")
      (value "R-EU_R0603")
      (footprint "eagle-import:R0603")
      (libsource (lib "eagle-import") (part "R-EU_R0603"))
    )
    (comp (ref "R71")
      (value "R-EU_R0603")
      (footprint "eagle-import:R0603")
      (libsource (lib "eagle-import") (part "R-EU_R0603"))
    )
    (comp (ref "R72")
      (value "R-EU_R0603")
      (footprint "eagle-import:R0603")
      (libsource (lib "eagle-import") (part "R-EU_R0603"))
    )
    (comp (ref "R73")
      (value "R-EU_R0603")
      (footprint "eagle-import:R0603")
      (libsource (lib "eagle-import") (part "R-EU_R0603"))
    )
    (comp (ref "R74")
      (value "R-EU_R0603")
      (footprint "eagle-import:R0603")
      (libsource (lib "eagle-import") (part "R-EU_R0603"))
    )
    (comp (ref "R75")
      (value "R-EU_R0603")
      (footprint "eagle-import:R0603")
      (libsource (lib "eagle-import") (part "R-EU_R0603"))
    )
    (comp (ref "R76")
      (value "R-EU_R0603")
      (footprint "eagle-import:R0603")
      (libsource (lib "eagle-import") (part "R-EU_R0603"))
    )
    (comp (ref "R77")
      (value "R-EU_R0603")
      (footprint "eagle-import:R0603")
      (libsource (lib "eagle-import") (part "R-EU_R0603"))
    )
    (comp (ref "R78")
      (value "R-EU_R0603")
      (footprint "eagle-import:R0603")
      (libsource (lib "eagle-import") (part "R-EU_R0603"))
    )
    (comp (ref "R79")
      (value "R-EU_R0603")
      (footprint "eagle-import:R0603")
      (libsource (lib "eagle-import") (part "R-EU_R0603"))
    )
    (comp (ref "R80")
      (value "R-EU_R0603")
      (footprint "eagle-import:R0603")
      (libsource (lib "eagle-import") (part "R-EU_R0603"))
    )
    (comp (ref "R81")
      (value "R-EU_R0603")
      (footprint "eagle-import:R0603")
      (libsource (lib "eagle-import") (part "R-EU_R0603"))
    )
    (comp (ref "SJ1") (value "SJ") (footprint "eagle-import:SJ") (libsource (lib "eagle-import") (part "SJ")))
    (comp (ref "SJ2") (value "SJ") (footprint "eagle-import:SJ") (libsource (lib "eagle-import") (part "SJ")))
    (comp (ref "SJ3") (value "SJ") (footprint "eagle-import:SJ") (libsource (lib "eagle-import") (part "SJ")))
    (comp (ref "SJ4") (value "SJ") (footprint "eagle-import:SJ") (libsource (lib "eagle-import") (part "SJ")))
    (comp (ref "SJ5") (value "SJ") (footprint "eagle-import:SJ") (libsource (lib "eagle-import") (part "SJ")))
    (comp (ref "SJ6") (value "SJ") (footprint "eagle-import:SJ") (libsource (lib "eagle-import") (part "SJ")))
    (comp (ref "SJ7") (value "SJ") (footprint "eagle-import:SJ") (libsource (lib "eagle-import") (part "SJ")))
    (comp (ref "SJ8") (value "SJ") (footprint "eagle-import:SJ") (libsource (lib "eagle-import") (part "SJ")))
    (comp (ref "SJ9") (value "SJ") (footprint "eagle-import:SJ") (libsource (lib "eagle-import") (part "SJ")))
    (comp (ref "SJ10")
      (value "SJ")
      (footprint "eagle-import:SJ")
      (libsource (lib "eagle-import") (part "SJ"))
    )
    (comp (ref "SJ11")
      (value "SJ")
      (footprint "eagle-import:SJ")
      (libsource (lib "eagle-import") (part "SJ"))
    )
    (comp (ref "SJ12")
      (value "SJ")
      (footprint "eagle-import:SJ")
      (libsource (lib "eagle-import") (part "SJ"))
    )
    (comp (ref "SJ13")
      (value "SJ")
      (footprint "eagle-import:SJ")
      (libsource (lib "eagle-import") (part "SJ"))
    )
    (comp (ref "SJ14")
      (value "SJ")
      (footprint "eagle-import:SJ")
      (libsource (lib "eagle-import") (part "SJ"))
    )
    (comp (ref "SJ15")
      (value "SJ")
      (footprint "eagle-import:SJ")
      (libsource (lib "eagle-import") (part "SJ"))
    )
    (comp (ref "SJ16")
      (value "SJ")
      (footprint "eagle-import:SJ")
      (libsource (lib "eagle-import") (part "SJ"))
    )
    (comp (ref "SJ17")
      (value "SJ")
      (footprint "eagle-import:SJ")
      (libsource (lib "eagle-import") (part "SJ"))
    )
    (comp (ref "SJ18")
      (value "SJ")
      (footprint "eagle-import:SJ")
      (libsource (lib "eagle-import") (part "SJ"))
    )
    (comp (ref "SJ19")
      (value "SJ")
      (footprint "eagle-import:SJ")
      (libsource (lib "eagle-import") (part "SJ"))
    )
    (comp (ref "SJ20")
      (value "SJ")
      (footprint "eagle-import:SJ")
      (libsource (lib "eagle-import") (part "SJ"))
    )
    (comp (ref "SJ21")
      (value "SJ")
      (footprint "eagle-import:SJ")
      (libsource (lib "eagle-import") (part "SJ"))
    )
    (comp (ref "SJ22")
      (value "SJ")
      (footprint "eagle-import:SJ")
      (libsource (lib "eagle-import") (part "SJ"))
    )
    (comp (ref "SJ23")
      (value "SJ")
      (footprint "eagle-import:SJ")
      (libsource (lib "eagle-import") (part "SJ"))
    )
    (comp (ref "SJ24")
      (value "SJ")
      (footprint "eagle-import:SJ")
      (libsource (lib "eagle-import") (part "SJ"))
    )
    (comp (ref "SJ25")
      (value "SJ")
      (footprint "eagle-import:SJ")
      (libsource (lib "eagle-import") (part "SJ"))
    )
    (comp (ref "SJ26")
      (value "SJ")
      (footprint "eagle-import:SJ")
      (libsource (lib "eagle-import") (part "SJ"))
    )
    (comp (ref "SJ27")
      (value "SJ")
      (footprint "eagle-import:SJ")
      (libsource (lib "eagle-import") (part "SJ"))
    )
    (comp (ref "SJ28")
      (value "SJ")
      (footprint "eagle-import:SJ")
      (libsource (lib "eagle-import") (part "SJ"))
    )
    (comp (ref "SJ29")
      (value "SJ")
      (footprint "eagle-import:SJ")
      (libsource (lib "eagle-import") (part "SJ"))
    )
    (comp (ref "SJ30")
      (value "SJ")
      (footprint "eagle-import:SJ")
      (libsource (lib "eagle-import") (part "SJ"))
    )
    (comp (ref "SJ31")
      (value "SJ")
      (footprint "eagle-import:SJ")
      (libsource (lib "eagle-import") (part "SJ"))
    )
    (comp (ref "SJ32")
      (value "SJ")
      (footprint "eagle-import:SJ")
      (libsource (lib "eagle-import") (part "SJ"))
    )
    (comp (ref "SJ33")
      (value "SJ")
      (footprint "eagle-import:SJ")
      (libsource (lib "eagle-import") (part "SJ"))
    )
    (comp (ref "SJ34")
      (value "SJ")
      (footprint "eagle-import:SJ")
      (libsource (lib "eagle-import") (part "SJ"))
    )
    (comp (ref "SJ35")
      (value "SJ")
      (footprint "eagle-import:SJ")
      (libsource (lib "eagle-import") (part "SJ"))
    )
    (comp (ref "SJ36")
      (value "SJ")
      (footprint "eagle-import:SJ")
      (libsource (lib "eagle-import") (part "SJ"))
    )
    (comp (ref "SJ37")
      (value "SJ")
      (footprint "eagle-import:SJ")
      (libsource (lib "eagle-import") (part "SJ"))
    )
    (comp (ref "SJ38")
      (value "SJ")
      (footprint "eagle-import:SJ")
      (libsource (lib "eagle-import") (part "SJ"))
    )
    (comp (ref "SJ39")
      (value "SJ")
      (footprint "eagle-import:SJ")
      (libsource (lib "eagle-import") (part "SJ"))
    )
    (comp (ref "SJ40")
      (value "SJ")
      (footprint "eagle-import:SJ")
      (libsource (lib "eagle-import") (part "SJ"))
    )
    (comp (ref "SJ41")
      (value "SJ")
      (footprint "eagle-import:SJ")
      (libsource (lib "eagle-import") (part "SJ"))
    )
    (comp (ref "SJ42")
      (value "SJ")
      (footprint "eagle-import:SJ")
      (libsource (lib "eagle-import") (part "SJ"))
    )
    (comp (ref "SJ43")
      (value "SJ")
      (footprint "eagle-import:SJ")
      (libsource (lib "eagle-import") (part "SJ"))
    )
    (comp (ref "SJ44")
      (value "SJ")
      (footprint "eagle-import:SJ")
      (libsource (lib "eagle-import") (part "SJ"))
    )
    (comp (ref "SJ45")
      (value "SJ")
      (footprint "eagle-import:SJ")
      (libsource (lib "eagle-import") (part "SJ"))
    )
    (comp (ref "SJ46")
      (value "SJ")
      (footprint "eagle-import:SJ")
      (libsource (lib "eagle-import") (part "SJ"))
    )
    (comp (ref "SJ47")
      (value "SJ")
      (footprint "eagle-import:SJ")
      (libsource (lib "eagle-import") (part "SJ"))
    )
    (comp (ref "SJ48")
      (value "SJ")
      (footprint "eagle-import:SJ")
      (libsource (lib "eagle-import") (part "SJ"))
    )
    (comp (ref "SJ49")
      (value "SJ")
      (footprint "eagle-import:SJ")
      (libsource (lib "eagle-import") (part "SJ"))
    )
    (comp (ref "SJ50")
      (value "SJ")
      (footprint "eagle-import:SJ")
      (libsource (lib "eagle-import") (part "SJ"))
    )
    (comp (ref "SJ51")
      (value "SJ")
      (footprint "eagle-import:SJ")
      (libsource (lib "eagle-import") (part "SJ"))
    )
    (comp (ref "SJ52")
      (value "SJ")
      (footprint "eagle-import:SJ")
      (libsource (lib "eagle-import") (part "SJ"))
    )
    (comp (ref "SJ53")
      (value "SJ")
      (footprint "eagle-import:SJ")
      (libsource (lib "eagle-import") (part "SJ"))
    )
    (comp (ref "SJ54")
      (value "SJ")
      (footprint "eagle-import:SJ")
      (libsource (lib "eagle-import") (part "SJ"))
    )
    (comp (ref "SJ55")
      (value "SJ")
      (footprint "eagle-import:SJ")
      (libsource (lib "eagle-import") (part "SJ"))
    )
    (comp (ref "SJ56")
      (value "SJ")
      (footprint "eagle-import:SJ")
      (libsource (lib "eagle-import") (part "SJ"))
    )
    (comp (ref "SJ57")
      (value "SJ")
      (footprint "eagle-import:SJ")
      (libsource (lib "eagle-import") (part "SJ"))
    )
    (comp (ref "SJ58")
      (value "SJ")
      (footprint "eagle-import:SJ")
      (libsource (lib "eagle-import") (part "SJ"))
    )
    (comp (ref "SJ59")
      (value "SJ")
      (footprint "eagle-import:SJ")
      (libsource (lib "eagle-import") (part "SJ"))
    )
    (comp (ref "SJ60")
      (value "SJ")
      (footprint "eagle-import:SJ")
      (libsource (lib "eagle-import") (part "SJ"))
    )
    (comp (ref "SJ61")
      (value "SJ")
      (footprint "eagle-import:SJ")
      (libsource (lib "eagle-import") (part "SJ"))
    )
    (comp (ref "SJ62")
      (value "SJ")
      (footprint "eagle-import:SJ")
      (libsource (lib "eagle-import") (part "SJ"))
    )
    (comp (ref "SJ63")
      (value "SJ")
      (footprint "eagle-import:SJ")
      (libsource (lib "eagle-import") (part "SJ"))
    )
    (comp (ref "SJ64")
      (value "SJ")
      (footprint "eagle-import:SJ")
      (libsource (lib "eagle-import") (part "SJ"))
    )
    (comp (ref "SJ65")
      (value "SJ")
      (footprint "eagle-import:SJ")
      (libsource (lib "eagle-import") (part "SJ"))
    )
    (comp (ref "SJ66")
      (value "SJ")
      (footprint "eagle-import:SJ")
      (libsource (lib "eagle-import") (part "SJ"))
    )
    (comp (ref "SJ67")
      (value "SJ")
      (footprint "eagle-import:SJ")
      (libsource (lib "eagle-import") (part "SJ"))
    )
    (comp (ref "SJ68")
      (value "SJ")
      (footprint "eagle-import:SJ")
      (libsource (lib "eagle-import") (part "SJ"))
    )
    (comp (ref "SJ69")
      (value "SJ")
      (footprint "eagle-import:SJ")
      (libsource (lib "eagle-import") (part "SJ"))
    )
    (comp (ref "SJ70")
      (value "SJ")
      (footprint "eagle-import:SJ")
      (libsource (lib "eagle-import") (part "SJ"))
    )
    (comp (ref "SJ71")
      (value "SJ")
      (footprint "eagle-import:SJ")
      (libsource (lib "eagle-import") (part "SJ"))
    )
    (comp (ref "SJ72")
      (value "SJ")
      (footprint "eagle-import:SJ")
      (libsource (lib "eagle-import") (part "SJ"))
    )
    (comp (ref "SJ73")
      (value "SJ")
      (footprint "eagle-import:SJ")
      (libsource (lib "eagle-import") (part "SJ"))
    )
    (comp (ref "SJ74")
      (value "SJ")
      (footprint "eagle-import:SJ")
      (libsource (lib "eagle-import") (part "SJ"))
    )
    (comp (ref "SJ75")
      (value "SJ")
      (footprint "eagle-import:SJ")
      (libsource (lib "eagle-import") (part "SJ"))
    )
    (comp (ref "SJ76")
      (value "SJ")
      (footprint "eagle-import:SJ")
      (libsource (lib "eagle-import") (part "SJ"))
    )
    (comp (ref "SJ77")
      (value "SJ")
      (footprint "eagle-import:SJ")
      (libsource (lib "eagle-import") (part "SJ"))
    )
    (comp (ref "SJ78")
      (value "SJ")
      (footprint "eagle-import:SJ")
      (libsource (lib "eagle-import") (part "SJ"))
    )
    (comp (ref "SJ79")
      (value "SJ")
      (footprint "eagle-import:SJ")
      (libsource (lib "eagle-import") (part "SJ"))
    )
    (comp (ref "SJ80")
      (value "SJ")
      (footprint "eagle-import:SJ")
      (libsource (lib "eagle-import") (part "SJ"))
    )
    (comp (ref "SJ81")
      (value "SJ")
      (footprint "eagle-import:SJ")
      (libsource (lib "eagle-import") (part "SJ"))
    )
    (comp (ref "SJ82")
      (value "SJ")
      (footprint "eagle-import:SJ")
      (libsource (lib "eagle-import") (part "SJ"))
    )
    (comp (ref "SJ83")
      (value "SJ")
      (footprint "eagle-import:SJ")
      (libsource (lib "eagle-import") (part "SJ"))
    )
    (comp (ref "SJ84")
      (value "SJ")
      (footprint "eagle-import:SJ")
      (libsource (lib "eagle-import") (part "SJ"))
    )
    (comp (ref "SJ91")
      (value "SJ")
      (footprint "eagle-import:SJ")
      (libsource (lib "eagle-import") (part "SJ"))
    )
    (comp (ref "SJ92")
      (value "SJ")
      (footprint "eagle-import:SJ")
      (libsource (lib "eagle-import") (part "SJ"))
    )
    (comp (ref "SJ93")
      (value "SJ")
      (footprint "eagle-import:SJ")
      (libsource (lib "eagle-import") (part "SJ"))
    )
    (comp (ref "SJ94")
      (value "SJ")
      (footprint "eagle-import:SJ")
      (libsource (lib "eagle-import") (part "SJ"))
    )
    (comp (ref "SJ95")
      (value "SJ")
      (footprint "eagle-import:SJ")
      (libsource (lib "eagle-import") (part "SJ"))
    )
    (comp (ref "SJ96")
      (value "SJ")
      (footprint "eagle-import:SJ")
      (libsource (lib "eagle-import") (part "SJ"))
    )
    (comp (ref "SJ97")
      (value "SJ")
      (footprint "eagle-import:SJ")
      (libsource (lib "eagle-import") (part "SJ"))
    )
    (comp (ref "SJ98")
      (value "SJ")
      (footprint "eagle-import:SJ")
      (libsource (lib "eagle-import") (part "SJ"))
    )
    (comp (ref "SJ99")
      (value "SJ")
      (footprint "eagle-import:SJ")
      (libsource (lib "eagle-import") (part "SJ"))
    )
    (comp (ref "SJ100")
      (value "SJ")
      (footprint "eagle-import:SJ")
      (libsource (lib "eagle-import") (part "SJ"))
    )
    (comp (ref "SJ101")
      (value "SJ")
      (footprint "eagle-import:SJ")
      (libsource (lib "eagle-import") (part "SJ"))
    )
    (comp (ref "SJ102")
      (value "SJ")
      (footprint "eagle-import:SJ")
      (libsource (lib "eagle-import") (part "SJ"))
    )
    (comp (ref "U1")
      (value "TPS60400DBVT")
      (footprint "eagle-import:SOT95P280X145-5N")
      (fields (field (name "MF") "Texas Instruments"))
      (libsource (lib "eagle-import") (part "TPS60400DBVT"))
    )
    (comp (ref "U2")
      (value "TLV271CDBVR")
      (footprint "eagle-import:SOT95P280X145-5N")
      (fields (field (name "MF") "Texas Instruments"))
      (libsource (lib "eagle-import") (part "TLV271CDBVR"))
    )
    (comp (ref "U3")
      (value "AD5270BRMZ-50")
      (footprint "eagle-import:SOP50P490X110-10N")
      (fields (field (name "MF") "Analog Devices"))
      (libsource (lib "eagle-import") (part "AD5270BRMZ-50"))
    )
    (comp (ref "U7")
      (value "TPS60400DBVT")
      (footprint "eagle-import:SOT95P280X145-5N")
      (fields (field (name "MF") "Texas Instruments"))
      (libsource (lib "eagle-import") (part "TPS60400DBVT"))
    )
    (comp (ref "U8")
      (value "AD5270BRMZ-50")
      (footprint "eagle-import:SOP50P490X110-10N")
      (fields (field (name "MF") "Analog Devices"))
      (libsource (lib "eagle-import") (part "AD5270BRMZ-50"))
    )
    (comp (ref "U9")
      (value "TLV271CDBVR")
      (footprint "eagle-import:SOT95P280X145-5N")
      (fields (field (name "MF") "Texas Instruments"))
      (libsource (lib "eagle-import") (part "TLV271CDBVR"))
    )
    (comp (ref "U10")
      (value "TPS60400DBVT")
      (footprint "eagle-import:SOT95P280X145-5N")
      (fields (field (name "MF") "Texas Instruments"))
      (libsource (lib "eagle-import") (part "TPS60400DBVT"))
    )
    (comp (ref "U11")
      (value "AD5270BRMZ-50")
      (footprint "eagle-import:SOP50P490X110-10N")
      (fields (field (name "MF") "Analog Devices"))
      (libsource (lib "eagle-import") (part "AD5270BRMZ-50"))
    )
    (comp (ref "U12")
      (value "TLV271CDBVR")
      (footprint "eagle-import:SOT95P280X145-5N")
      (fields (field (name "MF") "Texas Instruments"))
      (libsource (lib "eagle-import") (part "TLV271CDBVR"))
    )
    (comp (ref "U13")
      (value "TPS60400DBVT")
      (footprint "eagle-import:SOT95P280X145-5N")
      (fields (field (name "MF") "Texas Instruments"))
      (libsource (lib "eagle-import") (part "TPS60400DBVT"))
    )
    (comp (ref "U14")
      (value "AD5270BRMZ-50")
      (footprint "eagle-import:SOP50P490X110-10N")
      (fields (field (name "MF") "Analog Devices"))
      (libsource (lib "eagle-import") (part "AD5270BRMZ-50"))
    )
    (comp (ref "U15")
      (value "TLV271CDBVR")
      (footprint "eagle-import:SOT95P280X145-5N")
      (fields (field (name "MF") "Texas Instruments"))
      (libsource (lib "eagle-import") (part "TLV271CDBVR"))
    )
    (comp (ref "U16")
      (value "TPS60400DBVT")
      (footprint "eagle-import:SOT95P280X145-5N")
      (fields (field (name "MF") "Texas Instruments"))
      (libsource (lib "eagle-import") (part "TPS60400DBVT"))
    )
    (comp (ref "U17")
      (value "AD5270BRMZ-50")
      (footprint "eagle-import:SOP50P490X110-10N")
      (fields (field (name "MF") "Analog Devices"))
      (libsource (lib "eagle-import") (part "AD5270BRMZ-50"))
    )
    (comp (ref "U18")
      (value "TLV271CDBVR")
      (footprint "eagle-import:SOT95P280X145-5N")
      (fields (field (name "MF") "Texas Instruments"))
      (libsource (lib "eagle-import") (part "TLV271CDBVR"))
    )
    (comp (ref "U19")
      (value "TPS60400DBVT")
      (footprint "eagle-import:SOT95P280X145-5N")
      (fields (field (name "MF") "Texas Instruments"))
      (libsource (lib "eagle-import") (part "TPS60400DBVT"))
    )
    (comp (ref "U20")
      (value "AD5270BRMZ-50")
      (footprint "eagle-import:SOP50P490X110-10N")
      (fields (field (name "MF") "Analog Devices"))
      (libsource (lib "eagle-import") (part "AD5270BRMZ-50"))
    )
    (comp (ref "U21")
      (value "TLV271CDBVR")
      (footprint "eagle-import:SOT95P280X145-5N")
      (fields (field (name "MF") "Texas Instruments"))
      (libsource (lib "eagle-import") (part "TLV271CDBVR"))
    )
    (comp (ref "U22")
      (value "TPS60400DBVT")
      (footprint "eagle-import:SOT95P280X145-5N")
      (fields (field (name "MF") "Texas Instruments"))
      (libsource (lib "eagle-import") (part "TPS60400DBVT"))
    )
    (comp (ref "U23")
      (value "AD5270BRMZ-50")
      (footprint "eagle-import:SOP50P490X110-10N")
      (fields (field (name "MF") "Analog Devices"))
      (libsource (lib "eagle-import") (part "AD5270BRMZ-50"))
    )
    (comp (ref "U24")
      (value "TLV271CDBVR")
      (footprint "eagle-import:SOT95P280X145-5N")
      (fields (field (name "MF") "Texas Instruments"))
      (libsource (lib "eagle-import") (part "TLV271CDBVR"))
    )
    (comp (ref "U25")
      (value "TPS60400DBVT")
      (footprint "eagle-import:SOT95P280X145-5N")
      (fields (field (name "MF") "Texas Instruments"))
      (libsource (lib "eagle-import") (part "TPS60400DBVT"))
    )
    (comp (ref "U26")
      (value "AD5270BRMZ-50")
      (footprint "eagle-import:SOP50P490X110-10N")
      (fields (field (name "MF") "Analog Devices"))
      (libsource (lib "eagle-import") (part "AD5270BRMZ-50"))
    )
    (comp (ref "U27")
      (value "TLV271CDBVR")
      (footprint "eagle-import:SOT95P280X145-5N")
      (fields (field (name "MF") "Texas Instruments"))
      (libsource (lib "eagle-import") (part "TLV271CDBVR"))
    )
    (comp (ref "U28")
      (value "TPS60400DBVT")
      (footprint "eagle-import:SOT95P280X145-5N")
      (fields (field (name "MF") "Texas Instruments"))
      (libsource (lib "eagle-import") (part "TPS60400DBVT"))
    )
    (comp (ref "U29")
      (value "AD5270BRMZ-50")
      (footprint "eagle-import:SOP50P490X110-10N")
      (fields (field (name "MF") "Analog Devices"))
      (libsource (lib "eagle-import") (part "AD5270BRMZ-50"))
    )
    (comp (ref "U30")
      (value "TLV271CDBVR")
      (footprint "eagle-import:SOT95P280X145-5N")
      (fields (field (name "MF") "Texas Instruments"))
      (libsource (lib "eagle-import") (part "TLV271CDBVR"))
    )
    (comp (ref "U31")
      (value "TPS60400DBVT")
      (footprint "eagle-import:SOT95P280X145-5N")
      (fields (field (name "MF") "Texas Instruments"))
      (libsource (lib "eagle-import") (part "TPS60400DBVT"))
    )
    (comp (ref "U32")
      (value "AD5270BRMZ-50")
      (footprint "eagle-import:SOP50P490X110-10N")
      (fields (field (name "MF") "Analog Devices"))
      (libsource (lib "eagle-import") (part "AD5270BRMZ-50"))
    )
    (comp (ref "U33")
      (value "TLV271CDBVR")
      (footprint "eagle-import:SOT95P280X145-5N")
      (fields (field (name "MF") "Texas Instruments"))
      (libsource (lib "eagle-import") (part "TLV271CDBVR"))
    )
    (comp (ref "U34")
      (value "TPS60400DBVT")
      (footprint "eagle-import:SOT95P280X145-5N")
      (fields (field (name "MF") "Texas Instruments"))
      (libsource (lib "eagle-import") (part "TPS60400DBVT"))
    )
    (comp (ref "U35")
      (value "AD5270BRMZ-50")
      (footprint "eagle-import:SOP50P490X110-10N")
      (fields (field (name "MF") "Analog Devices"))
      (libsource (lib "eagle-import") (part "AD5270BRMZ-50"))
    )
    (comp (ref "U36")
      (value "TLV271CDBVR")
      (footprint "eagle-import:SOT95P280X145-5N")
      (fields (field (name "MF") "Texas Instruments"))
      (libsource (lib "eagle-import") (part "TLV271CDBVR"))
    )
    (comp (ref "U37")
      (value "TPS60400DBVT")
      (footprint "eagle-import:SOT95P280X145-5N")
      (fields (field (name "MF") "Texas Instruments"))
      (libsource (lib "eagle-import") (part "TPS60400DBVT"))
    )
    (comp (ref "U38")
      (value "AD5270BRMZ-50")
      (footprint "eagle-import:SOP50P490X110-10N")
      (fields (field (name "MF") "Analog Devices"))
      (libsource (lib "eagle-import") (part "AD5270BRMZ-50"))
    )
    (comp (ref "U39")
      (value "TLV271CDBVR")
      (footprint "eagle-import:SOT95P280X145-5N")
      (fields (field (name "MF") "Texas Instruments"))
      (libsource (lib "eagle-import") (part "TLV271CDBVR"))
    )
    (comp (ref "U40")
      (value "TPS60400DBVT")
      (footprint "eagle-import:SOT95P280X145-5N")
      (fields (field (name "MF") "Texas Instruments"))
      (libsource (lib "eagle-import") (part "TPS60400DBVT"))
    )
    (comp (ref "U41")
      (value "AD5270BRMZ-50")
      (footprint "eagle-import:SOP50P490X110-10N")
      (fields (field (name "MF") "Analog Devices"))
      (libsource (lib "eagle-import") (part "AD5270BRMZ-50"))
    )
    (comp (ref "U42")
      (value "TLV271CDBVR")
      (footprint "eagle-import:SOT95P280X145-5N")
      (fields (field (name "MF") "Texas Instruments"))
      (libsource (lib "eagle-import") (part "TLV271CDBVR"))
    )
    (comp (ref "U43")
      (value "TPS60400DBVT")
      (footprint "eagle-import:SOT95P280X145-5N")
      (fields (field (name "MF") "Texas Instruments"))
      (libsource (lib "eagle-import") (part "TPS60400DBVT"))
    )
    (comp (ref "U44")
      (value "AD5270BRMZ-50")
      (footprint "eagle-import:SOP50P490X110-10N")
      (fields (field (name "MF") "Analog Devices"))
      (libsource (lib "eagle-import") (part "AD5270BRMZ-50"))
    )
    (comp (ref "U45")
      (value "TLV271CDBVR")
      (footprint "eagle-import:SOT95P280X145-5N")
      (fields (field (name "MF") "Texas Instruments"))
      (libsource (lib "eagle-import") (part "TLV271CDBVR"))
    )
    (comp (ref "U46")
      (value "TPS60400DBVT")
      (footprint "eagle-import:SOT95P280X145-5N")
      (fields (field (name "MF") "Texas Instruments"))
      (libsource (lib "eagle-import") (part "TPS60400DBVT"))
    )
    (comp (ref "U47")
      (value "AD5270BRMZ-50")
      (footprint "eagle-import:SOP50P490X110-10N")
      (fields (field (name "MF") "Analog Devices"))
      (libsource (lib "eagle-import") (part "AD5270BRMZ-50"))
    )
    (comp (ref "U48")
      (value "TLV271CDBVR")
      (footprint "eagle-import:SOT95P280X145-5N")
      (fields (field (name "MF") "Texas Instruments"))
      (libsource (lib "eagle-import") (part "TLV271CDBVR"))
    )
    (comp (ref "U49")
      (value "TPS60400DBVT")
      (footprint "eagle-import:SOT95P280X145-5N")
      (fields (field (name "MF") "Texas Instruments"))
      (libsource (lib "eagle-import") (part "TPS60400DBVT"))
    )
    (comp (ref "U50")
      (value "AD5270BRMZ-50")
      (footprint "eagle-import:SOP50P490X110-10N")
      (fields (field (name "MF") "Analog Devices"))
      (libsource (lib "eagle-import") (part "AD5270BRMZ-50"))
    )
    (comp (ref "U51")
      (value "TLV271CDBVR")
      (footprint "eagle-import:SOT95P280X145-5N")
      (fields (field (name "MF") "Texas Instruments"))
      (libsource (lib "eagle-import") (part "TLV271CDBVR"))
    )
  )
  (nets
    (net (code "1") (name "+3V3") (class "Default")
      (node (ref "C1") (pin "1") (pinfunction "1_1") (pintype "passive"))
      (node (ref "C10") (pin "2") (pinfunction "2_2") (pintype "passive"))
      (node (ref "C100") (pin "2") (pinfunction "2_2") (pintype "passive"))
      (node (ref "C114") (pin "2") (pinfunction "2_2") (pintype "passive"))
      (node (ref "C122") (pin "2") (pinfunction "2_2") (pintype "passive"))
      (node (ref "C13") (pin "1") (pinfunction "1_1") (pintype "passive"))
      (node (ref "C130") (pin "2") (pinfunction "2_2") (pintype "passive"))
      (node (ref "C138") (pin "2") (pinfunction "2_2") (pintype "passive"))
      (node (ref "C146") (pin "2") (pinfunction "2_2") (pintype "passive"))
      (node (ref "C154") (pin "2") (pinfunction "2_2") (pintype "passive"))
      (node (ref "C16") (pin "2") (pinfunction "2_2") (pintype "passive"))
      (node (ref "C162") (pin "2") (pinfunction "2_2") (pintype "passive"))
      (node (ref "C170") (pin "2") (pinfunction "2_2") (pintype "passive"))
      (node (ref "C178") (pin "2") (pinfunction "2_2") (pintype "passive"))
      (node (ref "C186") (pin "2") (pinfunction "2_2") (pintype "passive"))
      (node (ref "C19") (pin "1") (pinfunction "1_1") (pintype "passive"))
      (node (ref "C194") (pin "2") (pinfunction "2_2") (pintype "passive"))
      (node (ref "C2") (pin "1") (pinfunction "1_1") (pintype "passive"))
      (node (ref "C202") (pin "2") (pinfunction "2_2") (pintype "passive"))
      (node (ref "C210") (pin "2") (pinfunction "2_2") (pintype "passive"))
      (node (ref "C218") (pin "2") (pinfunction "2_2") (pintype "passive"))
      (node (ref "C22") (pin "2") (pinfunction "2_2") (pintype "passive"))
      (node (ref "C226") (pin "2") (pinfunction "2_2") (pintype "passive"))
      (node (ref "C25") (pin "1") (pinfunction "1_1") (pintype "passive"))
      (node (ref "C28") (pin "2") (pinfunction "2_2") (pintype "passive"))
      (node (ref "C31") (pin "1") (pinfunction "1_1") (pintype "passive"))
      (node (ref "C34") (pin "2") (pinfunction "2_2") (pintype "passive"))
      (node (ref "C37") (pin "1") (pinfunction "1_1") (pintype "passive"))
      (node (ref "C40") (pin "2") (pinfunction "2_2") (pintype "passive"))
      (node (ref "C43") (pin "1") (pinfunction "1_1") (pintype "passive"))
      (node (ref "C46") (pin "2") (pinfunction "2_2") (pintype "passive"))
      (node (ref "C49") (pin "1") (pinfunction "1_1") (pintype "passive"))
      (node (ref "C5") (pin "2") (pinfunction "2_2") (pintype "passive"))
      (node (ref "C52") (pin "2") (pinfunction "2_2") (pintype "passive"))
      (node (ref "C55") (pin "1") (pinfunction "1_1") (pintype "passive"))
      (node (ref "C58") (pin "2") (pinfunction "2_2") (pintype "passive"))
      (node (ref "C61") (pin "1") (pinfunction "1_1") (pintype "passive"))
      (node (ref "C64") (pin "2") (pinfunction "2_2") (pintype "passive"))
      (node (ref "C67") (pin "1") (pinfunction "1_1") (pintype "passive"))
      (node (ref "C70") (pin "2") (pinfunction "2_2") (pintype "passive"))
      (node (ref "C73") (pin "1") (pinfunction "1_1") (pintype "passive"))
      (node (ref "C76") (pin "2") (pinfunction "2_2") (pintype "passive"))
      (node (ref "C79") (pin "1") (pinfunction "1_1") (pintype "passive"))
      (node (ref "C82") (pin "2") (pinfunction "2_2") (pintype "passive"))
      (node (ref "C87") (pin "2") (pinfunction "2_2") (pintype "passive"))
      (node (ref "C91") (pin "1") (pinfunction "1_1") (pintype "passive"))
      (node (ref "C94") (pin "2") (pinfunction "2_2") (pintype "passive"))
      (node (ref "C97") (pin "1") (pinfunction "1_1") (pintype "passive"))
      (node (ref "IC1") (pin "4") (pinfunction "AVDD_4") (pintype "power_in"))
      (node (ref "IC1") (pin "5") (pinfunction "DVDD_5") (pintype "power_in"))
      (node (ref "IC10") (pin "4") (pinfunction "AVDD_4") (pintype "power_in"))
      (node (ref "IC10") (pin "5") (pinfunction "DVDD_5") (pintype "power_in"))
      (node (ref "IC11") (pin "4") (pinfunction "AVDD_4") (pintype "power_in"))
      (node (ref "IC11") (pin "5") (pinfunction "DVDD_5") (pintype "power_in"))
      (node (ref "IC12") (pin "4") (pinfunction "AVDD_4") (pintype "power_in"))
      (node (ref "IC12") (pin "5") (pinfunction "DVDD_5") (pintype "power_in"))
      (node (ref "IC13") (pin "4") (pinfunction "AVDD_4") (pintype "power_in"))
      (node (ref "IC13") (pin "5") (pinfunction "DVDD_5") (pintype "power_in"))
      (node (ref "IC14") (pin "4") (pinfunction "AVDD_4") (pintype "power_in"))
      (node (ref "IC14") (pin "5") (pinfunction "DVDD_5") (pintype "power_in"))
      (node (ref "IC16") (pin "4") (pinfunction "AVDD_4") (pintype "power_in"))
      (node (ref "IC16") (pin "5") (pinfunction "DVDD_5") (pintype "power_in"))
      (node (ref "IC17") (pin "4") (pinfunction "AVDD_4") (pintype "power_in"))
      (node (ref "IC17") (pin "5") (pinfunction "DVDD_5") (pintype "power_in"))
      (node (ref "IC2") (pin "4") (pinfunction "AVDD_4") (pintype "power_in"))
      (node (ref "IC2") (pin "5") (pinfunction "DVDD_5") (pintype "power_in"))
      (node (ref "IC3") (pin "4") (pinfunction "AVDD_4") (pintype "power_in"))
      (node (ref "IC3") (pin "5") (pinfunction "DVDD_5") (pintype "power_in"))
      (node (ref "IC4") (pin "4") (pinfunction "AVDD_4") (pintype "power_in"))
      (node (ref "IC4") (pin "5") (pinfunction "DVDD_5") (pintype "power_in"))
      (node (ref "IC5") (pin "4") (pinfunction "AVDD_4") (pintype "power_in"))
      (node (ref "IC5") (pin "5") (pinfunction "DVDD_5") (pintype "power_in"))
      (node (ref "IC6") (pin "4") (pinfunction "AVDD_4") (pintype "power_in"))
      (node (ref "IC6") (pin "5") (pinfunction "DVDD_5") (pintype "power_in"))
      (node (ref "IC7") (pin "4") (pinfunction "AVDD_4") (pintype "power_in"))
      (node (ref "IC7") (pin "5") (pinfunction "DVDD_5") (pintype "power_in"))
      (node (ref "IC8") (pin "4") (pinfunction "AVDD_4") (pintype "power_in"))
      (node (ref "IC8") (pin "5") (pinfunction "DVDD_5") (pintype "power_in"))
      (node (ref "IC9") (pin "4") (pinfunction "AVDD_4") (pintype "power_in"))
      (node (ref "IC9") (pin "5") (pinfunction "DVDD_5") (pintype "power_in"))
      (node (ref "J2") (pin "1") (pinfunction "1_1") (pintype "passive"))
      (node (ref "J7") (pin "1") (pinfunction "1_1") (pintype "passive"))
      (node (ref "LDO") (pin "1") (pinfunction "IN_1") (pintype "bidirectional"))
      (node (ref "LDO") (pin "3") (pinfunction "EN_3") (pintype "bidirectional"))
      (node (ref "LDO10") (pin "1") (pinfunction "IN_1") (pintype "bidirectional"))
      (node (ref "LDO10") (pin "3") (pinfunction "EN_3") (pintype "bidirectional"))
      (node (ref "LDO11") (pin "1") (pinfunction "IN_1") (pintype "bidirectional"))
      (node (ref "LDO11") (pin "3") (pinfunction "EN_3") (pintype "bidirectional"))
      (node (ref "LDO12") (pin "1") (pinfunction "IN_1") (pintype "bidirectional"))
      (node (ref "LDO12") (pin "3") (pinfunction "EN_3") (pintype "bidirectional"))
      (node (ref "LDO13") (pin "1") (pinfunction "IN_1") (pintype "bidirectional"))
      (node (ref "LDO13") (pin "3") (pinfunction "EN_3") (pintype "bidirectional"))
      (node (ref "LDO14") (pin "1") (pinfunction "IN_1") (pintype "bidirectional"))
      (node (ref "LDO14") (pin "3") (pinfunction "EN_3") (pintype "bidirectional"))
      (node (ref "LDO15") (pin "1") (pinfunction "IN_1") (pintype "bidirectional"))
      (node (ref "LDO15") (pin "3") (pinfunction "EN_3") (pintype "bidirectional"))
      (node (ref "LDO16") (pin "1") (pinfunction "IN_1") (pintype "bidirectional"))
      (node (ref "LDO16") (pin "3") (pinfunction "EN_3") (pintype "bidirectional"))
      (node (ref "LDO2") (pin "1") (pinfunction "IN_1") (pintype "bidirectional"))
      (node (ref "LDO2") (pin "3") (pinfunction "EN_3") (pintype "bidirectional"))
      (node (ref "LDO3") (pin "1") (pinfunction "IN_1") (pintype "bidirectional"))
      (node (ref "LDO3") (pin "3") (pinfunction "EN_3") (pintype "bidirectional"))
      (node (ref "LDO4") (pin "1") (pinfunction "IN_1") (pintype "bidirectional"))
      (node (ref "LDO4") (pin "3") (pinfunction "EN_3") (pintype "bidirectional"))
      (node (ref "LDO5") (pin "1") (pinfunction "IN_1") (pintype "bidirectional"))
      (node (ref "LDO5") (pin "3") (pinfunction "EN_3") (pintype "bidirectional"))
      (node (ref "LDO6") (pin "1") (pinfunction "IN_1") (pintype "bidirectional"))
      (node (ref "LDO6") (pin "3") (pinfunction "EN_3") (pintype "bidirectional"))
      (node (ref "LDO7") (pin "1") (pinfunction "IN_1") (pintype "bidirectional"))
      (node (ref "LDO7") (pin "3") (pinfunction "EN_3") (pintype "bidirectional"))
      (node (ref "LDO8") (pin "1") (pinfunction "IN_1") (pintype "bidirectional"))
      (node (ref "LDO8") (pin "3") (pinfunction "EN_3") (pintype "bidirectional"))
      (node (ref "LDO9") (pin "1") (pinfunction "IN_1") (pintype "bidirectional"))
      (node (ref "LDO9") (pin "3") (pinfunction "EN_3") (pintype "bidirectional"))
    )
    (net (code "2") (name "/2.5V_1") (class "Default")
      (node (ref "C104") (pin "1") (pinfunction "1_1") (pintype "passive"))
      (node (ref "C86") (pin "2") (pinfunction "2_2") (pintype "passive"))
      (node (ref "C89") (pin "2") (pinfunction "2_2") (pintype "passive"))
      (node (ref "LDO") (pin "5") (pinfunction "OUT_5") (pintype "bidirectional"))
      (node (ref "U1") (pin "2") (pinfunction "IN_2") (pintype "power_in"))
      (node (ref "U2") (pin "5") (pinfunction "VDD_5") (pintype "power_in"))
      (node (ref "U3") (pin "1") (pinfunction "VDD_1") (pintype "power_in"))
    )
    (net (code "3") (name "/2.5V_2") (class "Default")
      (node (ref "C113") (pin "2") (pinfunction "2_2") (pintype "passive"))
      (node (ref "C116") (pin "2") (pinfunction "2_2") (pintype "passive"))
      (node (ref "C118") (pin "1") (pinfunction "1_1") (pintype "passive"))
      (node (ref "LDO2") (pin "5") (pinfunction "OUT_5") (pintype "bidirectional"))
      (node (ref "U7") (pin "2") (pinfunction "IN_2") (pintype "power_in"))
      (node (ref "U8") (pin "1") (pinfunction "VDD_1") (pintype "power_in"))
      (node (ref "U9") (pin "5") (pinfunction "VDD_5") (pintype "power_in"))
    )
    (net (code "4") (name "/2.5V_3") (class "Default")
      (node (ref "C137") (pin "2") (pinfunction "2_2") (pintype "passive"))
      (node (ref "C140") (pin "2") (pinfunction "2_2") (pintype "passive"))
      (node (ref "C142") (pin "1") (pinfunction "1_1") (pintype "passive"))
      (node (ref "LDO5") (pin "5") (pinfunction "OUT_5") (pintype "bidirectional"))
      (node (ref "U16") (pin "2") (pinfunction "IN_2") (pintype "power_in"))
      (node (ref "U17") (pin "1") (pinfunction "VDD_1") (pintype "power_in"))
      (node (ref "U18") (pin "5") (pinfunction "VDD_5") (pintype "power_in"))
    )
    (net (code "5") (name "/2.5V_4") (class "Default")
      (node (ref "C145") (pin "2") (pinfunction "2_2") (pintype "passive"))
      (node (ref "C148") (pin "2") (pinfunction "2_2") (pintype "passive"))
      (node (ref "C150") (pin "1") (pinfunction "1_1") (pintype "passive"))
      (node (ref "LDO6") (pin "5") (pinfunction "OUT_5") (pintype "bidirectional"))
      (node (ref "U19") (pin "2") (pinfunction "IN_2") (pintype "power_in"))
      (node (ref "U20") (pin "1") (pinfunction "VDD_1") (pintype "power_in"))
      (node (ref "U21") (pin "5") (pinfunction "VDD_5") (pintype "power_in"))
    )
    (net (code "6") (name "/2.5V_5") (class "Default")
      (node (ref "C121") (pin "2") (pinfunction "2_2") (pintype "passive"))
      (node (ref "C124") (pin "2") (pinfunction "2_2") (pintype "passive"))
      (node (ref "C126") (pin "1") (pinfunction "1_1") (pintype "passive"))
      (node (ref "LDO3") (pin "5") (pinfunction "OUT_5") (pintype "bidirectional"))
      (node (ref "U10") (pin "2") (pinfunction "IN_2") (pintype "power_in"))
      (node (ref "U11") (pin "1") (pinfunction "VDD_1") (pintype "power_in"))
      (node (ref "U12") (pin "5") (pinfunction "VDD_5") (pintype "power_in"))
    )
    (net (code "7") (name "/2.5V_6") (class "Default")
      (node (ref "C129") (pin "2") (pinfunction "2_2") (pintype "passive"))
      (node (ref "C132") (pin "2") (pinfunction "2_2") (pintype "passive"))
      (node (ref "C134") (pin "1") (pinfunction "1_1") (pintype "passive"))
      (node (ref "LDO4") (pin "5") (pinfunction "OUT_5") (pintype "bidirectional"))
      (node (ref "U13") (pin "2") (pinfunction "IN_2") (pintype "power_in"))
      (node (ref "U14") (pin "1") (pinfunction "VDD_1") (pintype "power_in"))
      (node (ref "U15") (pin "5") (pinfunction "VDD_5") (pintype "power_in"))
    )
    (net (code "8") (name "/2.5V_7") (class "Default")
      (node (ref "C153") (pin "2") (pinfunction "2_2") (pintype "passive"))
      (node (ref "C156") (pin "2") (pinfunction "2_2") (pintype "passive"))
      (node (ref "C158") (pin "1") (pinfunction "1_1") (pintype "passive"))
      (node (ref "LDO7") (pin "5") (pinfunction "OUT_5") (pintype "bidirectional"))
      (node (ref "U22") (pin "2") (pinfunction "IN_2") (pintype "power_in"))
      (node (ref "U23") (pin "1") (pinfunction "VDD_1") (pintype "power_in"))
      (node (ref "U24") (pin "5") (pinfunction "VDD_5") (pintype "power_in"))
    )
    (net (code "9") (name "/2.5V_8") (class "Default")
      (node (ref "C161") (pin "2") (pinfunction "2_2") (pintype "passive"))
      (node (ref "C164") (pin "2") (pinfunction "2_2") (pintype "passive"))
      (node (ref "C166") (pin "1") (pinfunction "1_1") (pintype "passive"))
      (node (ref "LDO8") (pin "5") (pinfunction "OUT_5") (pintype "bidirectional"))
      (node (ref "U25") (pin "2") (pinfunction "IN_2") (pintype "power_in"))
      (node (ref "U26") (pin "1") (pinfunction "VDD_1") (pintype "power_in"))
      (node (ref "U27") (pin "5") (pinfunction "VDD_5") (pintype "power_in"))
    )
    (net (code "10") (name "/2.5V_9") (class "Default")
      (node (ref "C169") (pin "2") (pinfunction "2_2") (pintype "passive"))
      (node (ref "C172") (pin "2") (pinfunction "2_2") (pintype "passive"))
      (node (ref "C174") (pin "1") (pinfunction "1_1") (pintype "passive"))
      (node (ref "LDO9") (pin "5") (pinfunction "OUT_5") (pintype "bidirectional"))
      (node (ref "U28") (pin "2") (pinfunction "IN_2") (pintype "power_in"))
      (node (ref "U29") (pin "1") (pinfunction "VDD_1") (pintype "power_in"))
      (node (ref "U30") (pin "5") (pinfunction "VDD_5") (pintype "power_in"))
    )
    (net (code "11") (name "/2.5V_10") (class "Default")
      (node (ref "C177") (pin "2") (pinfunction "2_2") (pintype "passive"))
      (node (ref "C180") (pin "2") (pinfunction "2_2") (pintype "passive"))
      (node (ref "C182") (pin "1") (pinfunction "1_1") (pintype "passive"))
      (node (ref "LDO10") (pin "5") (pinfunction "OUT_5") (pintype "bidirectional"))
      (node (ref "U31") (pin "2") (pinfunction "IN_2") (pintype "power_in"))
      (node (ref "U32") (pin "1") (pinfunction "VDD_1") (pintype "power_in"))
      (node (ref "U33") (pin "5") (pinfunction "VDD_5") (pintype "power_in"))
    )
    (net (code "12") (name "/2.5V_11") (class "Default")
      (node (ref "C201") (pin "2") (pinfunction "2_2") (pintype "passive"))
      (node (ref "C204") (pin "2") (pinfunction "2_2") (pintype "passive"))
      (node (ref "C206") (pin "1") (pinfunction "1_1") (pintype "passive"))
      (node (ref "LDO13") (pin "5") (pinfunction "OUT_5") (pintype "bidirectional"))
      (node (ref "U40") (pin "2") (pinfunction "IN_2") (pintype "power_in"))
      (node (ref "U41") (pin "1") (pinfunction "VDD_1") (pintype "power_in"))
      (node (ref "U42") (pin "5") (pinfunction "VDD_5") (pintype "power_in"))
    )
    (net (code "13") (name "/2.5V_12") (class "Default")
      (node (ref "C209") (pin "2") (pinfunction "2_2") (pintype "passive"))
      (node (ref "C212") (pin "2") (pinfunction "2_2") (pintype "passive"))
      (node (ref "C214") (pin "1") (pinfunction "1_1") (pintype "passive"))
      (node (ref "LDO14") (pin "5") (pinfunction "OUT_5") (pintype "bidirectional"))
      (node (ref "U43") (pin "2") (pinfunction "IN_2") (pintype "power_in"))
      (node (ref "U44") (pin "1") (pinfunction "VDD_1") (pintype "power_in"))
      (node (ref "U45") (pin "5") (pinfunction "VDD_5") (pintype "power_in"))
    )
    (net (code "14") (name "/2.5V_13") (class "Default")
      (node (ref "C185") (pin "2") (pinfunction "2_2") (pintype "passive"))
      (node (ref "C188") (pin "2") (pinfunction "2_2") (pintype "passive"))
      (node (ref "C190") (pin "1") (pinfunction "1_1") (pintype "passive"))
      (node (ref "LDO11") (pin "5") (pinfunction "OUT_5") (pintype "bidirectional"))
      (node (ref "U34") (pin "2") (pinfunction "IN_2") (pintype "power_in"))
      (node (ref "U35") (pin "1") (pinfunction "VDD_1") (pintype "power_in"))
      (node (ref "U36") (pin "5") (pinfunction "VDD_5") (pintype "power_in"))
    )
    (net (code "15") (name "/2.5V_14") (class "Default")
      (node (ref "C193") (pin "2") (pinfunction "2_2") (pintype "passive"))
      (node (ref "C196") (pin "2") (pinfunction "2_2") (pintype "passive"))
      (node (ref "C198") (pin "1") (pinfunction "1_1") (pintype "passive"))
      (node (ref "LDO12") (pin "5") (pinfunction "OUT_5") (pintype "bidirectional"))
      (node (ref "U37") (pin "2") (pinfunction "IN_2") (pintype "power_in"))
      (node (ref "U38") (pin "1") (pinfunction "VDD_1") (pintype "power_in"))
      (node (ref "U39") (pin "5") (pinfunction "VDD_5") (pintype "power_in"))
    )
    (net (code "16") (name "/2.5V_15") (class "Default")
      (node (ref "C217") (pin "2") (pinfunction "2_2") (pintype "passive"))
      (node (ref "C220") (pin "2") (pinfunction "2_2") (pintype "passive"))
      (node (ref "C222") (pin "1") (pinfunction "1_1") (pintype "passive"))
      (node (ref "LDO15") (pin "5") (pinfunction "OUT_5") (pintype "bidirectional"))
      (node (ref "U46") (pin "2") (pinfunction "IN_2") (pintype "power_in"))
      (node (ref "U47") (pin "1") (pinfunction "VDD_1") (pintype "power_in"))
      (node (ref "U48") (pin "5") (pinfunction "VDD_5") (pintype "power_in"))
    )
    (net (code "17") (name "/2.5V_16") (class "Default")
      (node (ref "C225") (pin "2") (pinfunction "2_2") (pintype "passive"))
      (node (ref "C228") (pin "2") (pinfunction "2_2") (pintype "passive"))
      (node (ref "C230") (pin "1") (pinfunction "1_1") (pintype "passive"))
      (node (ref "LDO16") (pin "5") (pinfunction "OUT_5") (pintype "bidirectional"))
      (node (ref "U49") (pin "2") (pinfunction "IN_2") (pintype "power_in"))
      (node (ref "U50") (pin "1") (pinfunction "VDD_1") (pintype "power_in"))
      (node (ref "U51") (pin "5") (pinfunction "VDD_5") (pintype "power_in"))
    )
    (net (code "18") (name "/DDS1_OUT") (class "Default")
      (node (ref "R57") (pin "1") (pinfunction "1_1") (pintype "passive"))
      (node (ref "SJ1") (pin "2") (pinfunction "2_2") (pintype "passive"))
      (node (ref "SJ2") (pin "2") (pinfunction "2_2") (pintype "passive"))
    )
    (net (code "19") (name "/DDS2_OUT") (class "Default")
      (node (ref "R59") (pin "1") (pinfunction "1_1") (pintype "passive"))
      (node (ref "SJ6") (pin "2") (pinfunction "2_2") (pintype "passive"))
      (node (ref "SJ8") (pin "2") (pinfunction "2_2") (pintype "passive"))
    )
    (net (code "20") (name "/DDS3_OUT") (class "Default")
      (node (ref "R70") (pin "1") (pinfunction "1_1") (pintype "passive"))
      (node (ref "SJ13") (pin "2") (pinfunction "2_2") (pintype "passive"))
      (node (ref "SJ14") (pin "2") (pinfunction "2_2") (pintype "passive"))
    )
    (net (code "21") (name "/DDS4_OUT") (class "Default")
      (node (ref "R71") (pin "1") (pinfunction "1_1") (pintype "passive"))
      (node (ref "SJ19") (pin "2") (pinfunction "2_2") (pintype "passive"))
      (node (ref "SJ20") (pin "2") (pinfunction "2_2") (pintype "passive"))
    )
    (net (code "22") (name "/DDS5_OUT") (class "Default")
      (node (ref "R60") (pin "1") (pinfunction "1_1") (pintype "passive"))
      (node (ref "SJ25") (pin "2") (pinfunction "2_2") (pintype "passive"))
      (node (ref "SJ26") (pin "2") (pinfunction "2_2") (pintype "passive"))
    )
    (net (code "23") (name "/DDS6_OUT") (class "Default")
      (node (ref "R69") (pin "1") (pinfunction "1_1") (pintype "passive"))
      (node (ref "SJ31") (pin "2") (pinfunction "2_2") (pintype "passive"))
      (node (ref "SJ32") (pin "2") (pinfunction "2_2") (pintype "passive"))
    )
    (net (code "24") (name "/DDS7_OUT") (class "Default")
      (node (ref "R72") (pin "1") (pinfunction "1_1") (pintype "passive"))
      (node (ref "SJ37") (pin "2") (pinfunction "2_2") (pintype "passive"))
      (node (ref "SJ38") (pin "2") (pinfunction "2_2") (pintype "passive"))
    )
    (net (code "25") (name "/DDS8_OUT") (class "Default")
      (node (ref "R73") (pin "1") (pinfunction "1_1") (pintype "passive"))
      (node (ref "SJ43") (pin "2") (pinfunction "2_2") (pintype "passive"))
      (node (ref "SJ44") (pin "2") (pinfunction "2_2") (pintype "passive"))
    )
    (net (code "26") (name "/DDS9_OUT") (class "Default")
      (node (ref "R74") (pin "1") (pinfunction "1_1") (pintype "passive"))
      (node (ref "SJ49") (pin "2") (pinfunction "2_2") (pintype "passive"))
      (node (ref "SJ50") (pin "2") (pinfunction "2_2") (pintype "passive"))
    )
    (net (code "27") (name "/DDS10_OUT") (class "Default")
      (node (ref "R75") (pin "1") (pinfunction "1_1") (pintype "passive"))
      (node (ref "SJ55") (pin "2") (pinfunction "2_2") (pintype "passive"))
      (node (ref "SJ56") (pin "2") (pinfunction "2_2") (pintype "passive"))
    )
    (net (code "28") (name "/DDS11_OUT") (class "Default")
      (node (ref "R78") (pin "1") (pinfunction "1_1") (pintype "passive"))
      (node (ref "SJ61") (pin "2") (pinfunction "2_2") (pintype "passive"))
      (node (ref "SJ62") (pin "2") (pinfunction "2_2") (pintype "passive"))
    )
    (net (code "29") (name "/DDS12_OUT") (class "Default")
      (node (ref "R79") (pin "1") (pinfunction "1_1") (pintype "passive"))
      (node (ref "SJ67") (pin "2") (pinfunction "2_2") (pintype "passive"))
      (node (ref "SJ68") (pin "2") (pinfunction "2_2") (pintype "passive"))
    )
    (net (code "30") (name "/DDS13_OUT") (class "Default")
      (node (ref "R76") (pin "1") (pinfunction "1_1") (pintype "passive"))
      (node (ref "SJ73") (pin "2") (pinfunction "2_2") (pintype "passive"))
      (node (ref "SJ74") (pin "2") (pinfunction "2_2") (pintype "passive"))
    )
    (net (code "31") (name "/DDS14_OUT") (class "Default")
      (node (ref "R77") (pin "1") (pinfunction "1_1") (pintype "passive"))
      (node (ref "SJ91") (pin "2") (pinfunction "2_2") (pintype "passive"))
      (node (ref "SJ92") (pin "2") (pinfunction "2_2") (pintype "passive"))
    )
    (net (code "32") (name "/DDS15_OUT") (class "Default")
      (node (ref "R80") (pin "1") (pinfunction "1_1") (pintype "passive"))
      (node (ref "SJ79") (pin "2") (pinfunction "2_2") (pintype "passive"))
      (node (ref "SJ80") (pin "2") (pinfunction "2_2") (pintype "passive"))
    )
    (net (code "33") (name "/DDS16_OUT") (class "Default")
      (node (ref "R81") (pin "1") (pinfunction "1_1") (pintype "passive"))
      (node (ref "SJ97") (pin "2") (pinfunction "2_2") (pintype "passive"))
      (node (ref "SJ98") (pin "2") (pinfunction "2_2") (pintype "passive"))
    )
    (net (code "34") (name "/DIN_2_A") (class "Default")
      (node (ref "J2") (pin "12") (pinfunction "12_12") (pintype "passive"))
      (node (ref "U17") (pin "8") (pinfunction "DIN_8") (pintype "input"))
      (node (ref "U20") (pin "8") (pinfunction "DIN_8") (pintype "input"))
      (node (ref "U3") (pin "8") (pinfunction "DIN_8") (pintype "input"))
      (node (ref "U8") (pin "8") (pinfunction "DIN_8") (pintype "input"))
    )
    (net (code "35") (name "/DIN_2_B") (class "Default")
      (node (ref "J4") (pin "10") (pinfunction "10_10") (pintype "passive"))
      (node (ref "U11") (pin "8") (pinfunction "DIN_8") (pintype "input"))
      (node (ref "U14") (pin "8") (pinfunction "DIN_8") (pintype "input"))
      (node (ref "U23") (pin "8") (pinfunction "DIN_8") (pintype "input"))
      (node (ref "U26") (pin "8") (pinfunction "DIN_8") (pintype "input"))
    )
    (net (code "36") (name "/DIN_2_C") (class "Default")
      (node (ref "J1") (pin "10") (pinfunction "10_10") (pintype "passive"))
      (node (ref "U29") (pin "8") (pinfunction "DIN_8") (pintype "input"))
      (node (ref "U32") (pin "8") (pinfunction "DIN_8") (pintype "input"))
      (node (ref "U41") (pin "8") (pinfunction "DIN_8") (pintype "input"))
      (node (ref "U44") (pin "8") (pinfunction "DIN_8") (pintype "input"))
    )
    (net (code "37") (name "/DIN_2_D") (class "Default")
      (node (ref "J7") (pin "12") (pinfunction "12_12") (pintype "passive"))
      (node (ref "U35") (pin "8") (pinfunction "DIN_8") (pintype "input"))
      (node (ref "U38") (pin "8") (pinfunction "DIN_8") (pintype "input"))
      (node (ref "U47") (pin "8") (pinfunction "DIN_8") (pintype "input"))
      (node (ref "U50") (pin "8") (pinfunction "DIN_8") (pintype "input"))
    )
    (net (code "38") (name "/FILTER1") (class "Default")
      (node (ref "C7") (pin "1") (pinfunction "1_1") (pintype "passive"))
      (node (ref "R3") (pin "2") (pinfunction "2_2") (pintype "passive"))
      (node (ref "SJ1") (pin "1") (pinfunction "1_1") (pintype "passive"))
      (node (ref "SJ4") (pin "2") (pinfunction "2_2") (pintype "passive"))
      (node (ref "SJ5") (pin "2") (pinfunction "2_2") (pintype "passive"))
    )
    (net (code "39") (name "/FILTER2") (class "Default")
      (node (ref "C12") (pin "1") (pinfunction "1_1") (pintype "passive"))
      (node (ref "R8") (pin "2") (pinfunction "2_2") (pintype "passive"))
      (node (ref "SJ11") (pin "2") (pinfunction "2_2") (pintype "passive"))
      (node (ref "SJ12") (pin "2") (pinfunction "2_2") (pintype "passive"))
      (node (ref "SJ6") (pin "1") (pinfunction "1_1") (pintype "passive"))
    )
    (net (code "40") (name "/FILTER3") (class "Default")
      (node (ref "C18") (pin "1") (pinfunction "1_1") (pintype "passive"))
      (node (ref "R12") (pin "2") (pinfunction "2_2") (pintype "passive"))
      (node (ref "SJ13") (pin "1") (pinfunction "1_1") (pintype "passive"))
      (node (ref "SJ17") (pin "2") (pinfunction "2_2") (pintype "passive"))
      (node (ref "SJ18") (pin "2") (pinfunction "2_2") (pintype "passive"))
    )
    (net (code "41") (name "/FILTER4") (class "Default")
      (node (ref "C24") (pin "1") (pinfunction "1_1") (pintype "passive"))
      (node (ref "R16") (pin "2") (pinfunction "2_2") (pintype "passive"))
      (node (ref "SJ19") (pin "1") (pinfunction "1_1") (pintype "passive"))
      (node (ref "SJ23") (pin "2") (pinfunction "2_2") (pintype "passive"))
      (node (ref "SJ24") (pin "2") (pinfunction "2_2") (pintype "passive"))
    )
    (net (code "42") (name "/FILTER5") (class "Default")
      (node (ref "C30") (pin "1") (pinfunction "1_1") (pintype "passive"))
      (node (ref "R20") (pin "2") (pinfunction "2_2") (pintype "passive"))
      (node (ref "SJ25") (pin "1") (pinfunction "1_1") (pintype "passive"))
      (node (ref "SJ29") (pin "2") (pinfunction "2_2") (pintype "passive"))
      (node (ref "SJ30") (pin "2") (pinfunction "2_2") (pintype "passive"))
    )
    (net (code "43") (name "/FILTER6") (class "Default")
      (node (ref "C36") (pin "1") (pinfunction "1_1") (pintype "passive"))
      (node (ref "R24") (pin "2") (pinfunction "2_2") (pintype "passive"))
      (node (ref "SJ31") (pin "1") (pinfunction "1_1") (pintype "passive"))
      (node (ref "SJ35") (pin "2") (pinfunction "2_2") (pintype "passive"))
      (node (ref "SJ36") (pin "2") (pinfunction "2_2") (pintype "passive"))
    )
    (net (code "44") (name "/FILTER7") (class "Default")
      (node (ref "C42") (pin "1") (pinfunction "1_1") (pintype "passive"))
      (node (ref "R28") (pin "2") (pinfunction "2_2") (pintype "passive"))
      (node (ref "SJ37") (pin "1") (pinfunction "1_1") (pintype "passive"))
      (node (ref "SJ41") (pin "2") (pinfunction "2_2") (pintype "passive"))
      (node (ref "SJ42") (pin "2") (pinfunction "2_2") (pintype "passive"))
    )
    (net (code "45") (name "/FILTER8") (class "Default")
      (node (ref "C48") (pin "1") (pinfunction "1_1") (pintype "passive"))
      (node (ref "R32") (pin "2") (pinfunction "2_2") (pintype "passive"))
      (node (ref "SJ43") (pin "1") (pinfunction "1_1") (pintype "passive"))
      (node (ref "SJ47") (pin "2") (pinfunction "2_2") (pintype "passive"))
      (node (ref "SJ48") (pin "2") (pinfunction "2_2") (pintype "passive"))
    )
    (net (code "46") (name "/FILTER9") (class "Default")
      (node (ref "C54") (pin "1") (pinfunction "1_1") (pintype "passive"))
      (node (ref "R36") (pin "2") (pinfunction "2_2") (pintype "passive"))
      (node (ref "SJ49") (pin "1") (pinfunction "1_1") (pintype "passive"))
      (node (ref "SJ53") (pin "2") (pinfunction "2_2") (pintype "passive"))
      (node (ref "SJ54") (pin "2") (pinfunction "2_2") (pintype "passive"))
    )
    (net (code "47") (name "/FILTER10") (class "Default")
      (node (ref "C60") (pin "1") (pinfunction "1_1") (pintype "passive"))
      (node (ref "R40") (pin "2") (pinfunction "2_2") (pintype "passive"))
      (node (ref "SJ55") (pin "1") (pinfunction "1_1") (pintype "passive"))
      (node (ref "SJ59") (pin "2") (pinfunction "2_2") (pintype "passive"))
      (node (ref "SJ60") (pin "2") (pinfunction "2_2") (pintype "passive"))
    )
    (net (code "48") (name "/FILTER11") (class "Default")
      (node (ref "C66") (pin "1") (pinfunction "1_1") (pintype "passive"))
      (node (ref "R44") (pin "2") (pinfunction "2_2") (pintype "passive"))
      (node (ref "SJ61") (pin "1") (pinfunction "1_1") (pintype "passive"))
      (node (ref "SJ65") (pin "2") (pinfunction "2_2") (pintype "passive"))
      (node (ref "SJ66") (pin "2") (pinfunction "2_2") (pintype "passive"))
    )
    (net (code "49") (name "/FILTER12") (class "Default")
      (node (ref "C72") (pin "1") (pinfunction "1_1") (pintype "passive"))
      (node (ref "R48") (pin "2") (pinfunction "2_2") (pintype "passive"))
      (node (ref "SJ67") (pin "1") (pinfunction "1_1") (pintype "passive"))
      (node (ref "SJ71") (pin "2") (pinfunction "2_2") (pintype "passive"))
      (node (ref "SJ72") (pin "2") (pinfunction "2_2") (pintype "passive"))
    )
    (net (code "50") (name "/FILTER13") (class "Default")
      (node (ref "C78") (pin "1") (pinfunction "1_1") (pintype "passive"))
      (node (ref "R52") (pin "2") (pinfunction "2_2") (pintype "passive"))
      (node (ref "SJ73") (pin "1") (pinfunction "1_1") (pintype "passive"))
      (node (ref "SJ77") (pin "2") (pinfunction "2_2") (pintype "passive"))
      (node (ref "SJ78") (pin "2") (pinfunction "2_2") (pintype "passive"))
    )
    (net (code "51") (name "/FILTER14") (class "Default")
      (node (ref "C96") (pin "1") (pinfunction "1_1") (pintype "passive"))
      (node (ref "R64") (pin "2") (pinfunction "2_2") (pintype "passive"))
      (node (ref "SJ91") (pin "1") (pinfunction "1_1") (pintype "passive"))
      (node (ref "SJ95") (pin "2") (pinfunction "2_2") (pintype "passive"))
      (node (ref "SJ96") (pin "2") (pinfunction "2_2") (pintype "passive"))
    )
    (net (code "52") (name "/FILTER15") (class "Default")
      (node (ref "C84") (pin "1") (pinfunction "1_1") (pintype "passive"))
      (node (ref "R56") (pin "2") (pinfunction "2_2") (pintype "passive"))
      (node (ref "SJ79") (pin "1") (pinfunction "1_1") (pintype "passive"))
      (node (ref "SJ83") (pin "2") (pinfunction "2_2") (pintype "passive"))
      (node (ref "SJ84") (pin "2") (pinfunction "2_2") (pintype "passive"))
    )
    (net (code "53") (name "/FILTER16") (class "Default")
      (node (ref "C102") (pin "1") (pinfunction "1_1") (pintype "passive"))
      (node (ref "R68") (pin "2") (pinfunction "2_2") (pintype "passive"))
      (node (ref "SJ101") (pin "2") (pinfunction "2_2") (pintype "passive"))
      (node (ref "SJ102") (pin "2") (pinfunction "2_2") (pintype "passive"))
      (node (ref "SJ97") (pin "1") (pinfunction "1_1") (pintype "passive"))
    )
    (net (code "54") (name "/FSELECT_A") (class "Default")
      (node (ref "IC1") (pin "9") (pinfunction "FSELECT_9") (pintype "bidirectional"))
      (node (ref "IC2") (pin "9") (pinfunction "FSELECT_9") (pintype "bidirectional"))
      (node (ref "IC3") (pin "9") (pinfunction "FSELECT_9") (pintype "bidirectional"))
      (node (ref "IC4") (pin "9") (pinfunction "FSELECT_9") (pintype "bidirectional"))
      (node (ref "J2") (pin "3") (pinfunction "3_3") (pintype "passive"))
    )
    (net (code "55") (name "/FSELECT_B") (class "Default")
      (node (ref "IC5") (pin "9") (pinfunction "FSELECT_9") (pintype "bidirectional"))
      (node (ref "IC6") (pin "9") (pinfunction "FSELECT_9") (pintype "bidirectional"))
      (node (ref "IC7") (pin "9") (pinfunction "FSELECT_9") (pintype "bidirectional"))
      (node (ref "IC8") (pin "9") (pinfunction "FSELECT_9") (pintype "bidirectional"))
      (node (ref "J4") (pin "1") (pinfunction "1_1") (pintype "passive"))
    )
    (net (code "56") (name "/FSELECT_C") (class "Default")
      (node (ref "IC10") (pin "9") (pinfunction "FSELECT_9") (pintype "bidirectional"))
      (node (ref "IC11") (pin "9") (pinfunction "FSELECT_9") (pintype "bidirectional"))
      (node (ref "IC12") (pin "9") (pinfunction "FSELECT_9") (pintype "bidirectional"))
      (node (ref "IC9") (pin "9") (pinfunction "FSELECT_9") (pintype "bidirectional"))
      (node (ref "J1") (pin "1") (pinfunction "1_1") (pintype "passive"))
    )
    (net (code "57") (name "/FSELECT_D") (class "Default")
      (node (ref "IC13") (pin "9") (pinfunction "FSELECT_9") (pintype "bidirectional"))
      (node (ref "IC14") (pin "9") (pinfunction "FSELECT_9") (pintype "bidirectional"))
      (node (ref "IC16") (pin "9") (pinfunction "FSELECT_9") (pintype "bidirectional"))
      (node (ref "IC17") (pin "9") (pinfunction "FSELECT_9") (pintype "bidirectional"))
      (node (ref "J7") (pin "3") (pinfunction "3_3") (pintype "passive"))
    )
    (net (code "58") (name "/FSYNC1") (class "Default")
      (node (ref "IC1") (pin "15") (pinfunction "FSYNC_15") (pintype "bidirectional"))
      (node (ref "J2") (pin "5") (pinfunction "5_5") (pintype "passive"))
      (node (ref "U3") (pin "10") (pinfunction "~{SYNC}_10") (pintype "input"))
    )
    (net (code "59") (name "/FSYNC2") (class "Default")
      (node (ref "IC2") (pin "15") (pinfunction "FSYNC_15") (pintype "bidirectional"))
      (node (ref "J2") (pin "8") (pinfunction "8_8") (pintype "passive"))
      (node (ref "U8") (pin "10") (pinfunction "~{SYNC}_10") (pintype "input"))
    )
    (net (code "60") (name "/FSYNC3") (class "Default")
      (node (ref "IC3") (pin "15") (pinfunction "FSYNC_15") (pintype "bidirectional"))
      (node (ref "J2") (pin "7") (pinfunction "7_7") (pintype "passive"))
      (node (ref "U17") (pin "10") (pinfunction "~{SYNC}_10") (pintype "input"))
    )
    (net (code "61") (name "/FSYNC4") (class "Default")
      (node (ref "IC4") (pin "15") (pinfunction "FSYNC_15") (pintype "bidirectional"))
      (node (ref "J2") (pin "10") (pinfunction "10_10") (pintype "passive"))
      (node (ref "U20") (pin "10") (pinfunction "~{SYNC}_10") (pintype "input"))
    )
    (net (code "62") (name "/FSYNC5") (class "Default")
      (node (ref "IC5") (pin "15") (pinfunction "FSYNC_15") (pintype "bidirectional"))
      (node (ref "J4") (pin "3") (pinfunction "3_3") (pintype "passive"))
      (node (ref "U11") (pin "10") (pinfunction "~{SYNC}_10") (pintype "input"))
    )
    (net (code "63") (name "/FSYNC6") (class "Default")
      (node (ref "IC6") (pin "15") (pinfunction "FSYNC_15") (pintype "bidirectional"))
      (node (ref "J4") (pin "6") (pinfunction "6_6") (pintype "passive"))
      (node (ref "U14") (pin "10") (pinfunction "~{SYNC}_10") (pintype "input"))
    )
    (net (code "64") (name "/FSYNC7") (class "Default")
      (node (ref "IC7") (pin "15") (pinfunction "FSYNC_15") (pintype "bidirectional"))
      (node (ref "J4") (pin "5") (pinfunction "5_5") (pintype "passive"))
      (node (ref "U23") (pin "10") (pinfunction "~{SYNC}_10") (pintype "input"))
    )
    (net (code "65") (name "/FSYNC8") (class "Default")
      (node (ref "IC8") (pin "15") (pinfunction "FSYNC_15") (pintype "bidirectional"))
      (node (ref "J4") (pin "8") (pinfunction "8_8") (pintype "passive"))
      (node (ref "U26") (pin "10") (pinfunction "~{SYNC}_10") (pintype "input"))
    )
    (net (code "66") (name "/FSYNC9") (class "Default")
      (node (ref "IC9") (pin "15") (pinfunction "FSYNC_15") (pintype "bidirectional"))
      (node (ref "J1") (pin "3") (pinfunction "3_3") (pintype "passive"))
      (node (ref "U29") (pin "10") (pinfunction "~{SYNC}_10") (pintype "input"))
    )
    (net (code "67") (name "/FSYNC10") (class "Default")
      (node (ref "IC10") (pin "15") (pinfunction "FSYNC_15") (pintype "bidirectional"))
      (node (ref "J1") (pin "6") (pinfunction "6_6") (pintype "passive"))
      (node (ref "U32") (pin "10") (pinfunction "~{SYNC}_10") (pintype "input"))
    )
    (net (code "68") (name "/FSYNC11") (class "Default")
      (node (ref "IC11") (pin "15") (pinfunction "FSYNC_15") (pintype "bidirectional"))
      (node (ref "J1") (pin "5") (pinfunction "5_5") (pintype "passive"))
      (node (ref "U41") (pin "10") (pinfunction "~{SYNC}_10") (pintype "input"))
    )
    (net (code "69") (name "/FSYNC12") (class "Default")
      (node (ref "IC12") (pin "15") (pinfunction "FSYNC_15") (pintype "bidirectional"))
      (node (ref "J1") (pin "8") (pinfunction "8_8") (pintype "passive"))
      (node (ref "U44") (pin "10") (pinfunction "~{SYNC}_10") (pintype "input"))
    )
    (net (code "70") (name "/FSYNC13") (class "Default")
      (node (ref "IC13") (pin "15") (pinfunction "FSYNC_15") (pintype "bidirectional"))
      (node (ref "J7") (pin "5") (pinfunction "5_5") (pintype "passive"))
      (node (ref "U35") (pin "10") (pinfunction "~{SYNC}_10") (pintype "input"))
    )
    (net (code "71") (name "/FSYNC14") (class "Default")
      (node (ref "IC16") (pin "15") (pinfunction "FSYNC_15") (pintype "bidirectional"))
      (node (ref "J7") (pin "8") (pinfunction "8_8") (pintype "passive"))
      (node (ref "U38") (pin "10") (pinfunction "~{SYNC}_10") (pintype "input"))
    )
    (net (code "72") (name "/FSYNC15") (class "Default")
      (node (ref "IC14") (pin "15") (pinfunction "FSYNC_15") (pintype "bidirectional"))
      (node (ref "J7") (pin "7") (pinfunction "7_7") (pintype "passive"))
      (node (ref "U47") (pin "10") (pinfunction "~{SYNC}_10") (pintype "input"))
    )
    (net (code "73") (name "/FSYNC16") (class "Default")
      (node (ref "IC17") (pin "15") (pinfunction "FSYNC_15") (pintype "bidirectional"))
      (node (ref "J7") (pin "10") (pinfunction "10_10") (pintype "passive"))
      (node (ref "U50") (pin "10") (pinfunction "~{SYNC}_10") (pintype "input"))
    )
    (net (code "74") (name "/IOUT1") (class "Default")
      (node (ref "IC1") (pin "19") (pinfunction "IOUT_19") (pintype "bidirectional"))
      (node (ref "R3") (pin "1") (pinfunction "1_1") (pintype "passive"))
      (node (ref "R5") (pin "2") (pinfunction "2_2") (pintype "passive"))
      (node (ref "SJ4") (pin "1") (pinfunction "1_1") (pintype "passive"))
    )
    (net (code "75") (name "/IOUT2") (class "Default")
      (node (ref "IC2") (pin "19") (pinfunction "IOUT_19") (pintype "bidirectional"))
      (node (ref "R7") (pin "2") (pinfunction "2_2") (pintype "passive"))
      (node (ref "R8") (pin "1") (pinfunction "1_1") (pintype "passive"))
      (node (ref "SJ11") (pin "1") (pinfunction "1_1") (pintype "passive"))
    )
    (net (code "76") (name "/IOUT3") (class "Default")
      (node (ref "IC3") (pin "19") (pinfunction "IOUT_19") (pintype "bidirectional"))
      (node (ref "R11") (pin "2") (pinfunction "2_2") (pintype "passive"))
      (node (ref "R12") (pin "1") (pinfunction "1_1") (pintype "passive"))
      (node (ref "SJ17") (pin "1") (pinfunction "1_1") (pintype "passive"))
    )
    (net (code "77") (name "/IOUT4") (class "Default")
      (node (ref "IC4") (pin "19") (pinfunction "IOUT_19") (pintype "bidirectional"))
      (node (ref "R15") (pin "2") (pinfunction "2_2") (pintype "passive"))
      (node (ref "R16") (pin "1") (pinfunction "1_1") (pintype "passive"))
      (node (ref "SJ23") (pin "1") (pinfunction "1_1") (pintype "passive"))
    )
    (net (code "78") (name "/IOUT5") (class "Default")
      (node (ref "IC5") (pin "19") (pinfunction "IOUT_19") (pintype "bidirectional"))
      (node (ref "R19") (pin "2") (pinfunction "2_2") (pintype "passive"))
      (node (ref "R20") (pin "1") (pinfunction "1_1") (pintype "passive"))
      (node (ref "SJ29") (pin "1") (pinfunction "1_1") (pintype "passive"))
    )
    (net (code "79") (name "/IOUT6") (class "Default")
      (node (ref "IC6") (pin "19") (pinfunction "IOUT_19") (pintype "bidirectional"))
      (node (ref "R23") (pin "2") (pinfunction "2_2") (pintype "passive"))
      (node (ref "R24") (pin "1") (pinfunction "1_1") (pintype "passive"))
      (node (ref "SJ35") (pin "1") (pinfunction "1_1") (pintype "passive"))
    )
    (net (code "80") (name "/IOUT7") (class "Default")
      (node (ref "IC7") (pin "19") (pinfunction "IOUT_19") (pintype "bidirectional"))
      (node (ref "R27") (pin "2") (pinfunction "2_2") (pintype "passive"))
      (node (ref "R28") (pin "1") (pinfunction "1_1") (pintype "passive"))
      (node (ref "SJ41") (pin "1") (pinfunction "1_1") (pintype "passive"))
    )
    (net (code "81") (name "/IOUT8") (class "Default")
      (node (ref "IC8") (pin "19") (pinfunction "IOUT_19") (pintype "bidirectional"))
      (node (ref "R31") (pin "2") (pinfunction "2_2") (pintype "passive"))
      (node (ref "R32") (pin "1") (pinfunction "1_1") (pintype "passive"))
      (node (ref "SJ47") (pin "1") (pinfunction "1_1") (pintype "passive"))
    )
    (net (code "82") (name "/IOUT9") (class "Default")
      (node (ref "IC9") (pin "19") (pinfunction "IOUT_19") (pintype "bidirectional"))
      (node (ref "R35") (pin "2") (pinfunction "2_2") (pintype "passive"))
      (node (ref "R36") (pin "1") (pinfunction "1_1") (pintype "passive"))
      (node (ref "SJ53") (pin "1") (pinfunction "1_1") (pintype "passive"))
    )
    (net (code "83") (name "/IOUT10") (class "Default")
      (node (ref "IC10") (pin "19") (pinfunction "IOUT_19") (pintype "bidirectional"))
      (node (ref "R39") (pin "2") (pinfunction "2_2") (pintype "passive"))
      (node (ref "R40") (pin "1") (pinfunction "1_1") (pintype "passive"))
      (node (ref "SJ59") (pin "1") (pinfunction "1_1") (pintype "passive"))
    )
    (net (code "84") (name "/IOUT11") (class "Default")
      (node (ref "IC11") (pin "19") (pinfunction "IOUT_19") (pintype "bidirectional"))
      (node (ref "R43") (pin "2") (pinfunction "2_2") (pintype "passive"))
      (node (ref "R44") (pin "1") (pinfunction "1_1") (pintype "passive"))
      (node (ref "SJ65") (pin "1") (pinfunction "1_1") (pintype "passive"))
    )
    (net (code "85") (name "/IOUT12") (class "Default")
      (node (ref "IC12") (pin "19") (pinfunction "IOUT_19") (pintype "bidirectional"))
      (node (ref "R47") (pin "2") (pinfunction "2_2") (pintype "passive"))
      (node (ref "R48") (pin "1") (pinfunction "1_1") (pintype "passive"))
      (node (ref "SJ71") (pin "1") (pinfunction "1_1") (pintype "passive"))
    )
    (net (code "86") (name "/IOUT13") (class "Default")
      (node (ref "IC13") (pin "19") (pinfunction "IOUT_19") (pintype "bidirectional"))
      (node (ref "R51") (pin "2") (pinfunction "2_2") (pintype "passive"))
      (node (ref "R52") (pin "1") (pinfunction "1_1") (pintype "passive"))
      (node (ref "SJ77") (pin "1") (pinfunction "1_1") (pintype "passive"))
    )
    (net (code "87") (name "/IOUT14") (class "Default")
      (node (ref "IC16") (pin "19") (pinfunction "IOUT_19") (pintype "bidirectional"))
      (node (ref "R63") (pin "2") (pinfunction "2_2") (pintype "passive"))
      (node (ref "R64") (pin "1") (pinfunction "1_1") (pintype "passive"))
      (node (ref "SJ95") (pin "1") (pinfunction "1_1") (pintype "passive"))
    )
    (net (code "88") (name "/IOUT15") (class "Default")
      (node (ref "IC14") (pin "19") (pinfunction "IOUT_19") (pintype "bidirectional"))
      (node (ref "R55") (pin "2") (pinfunction "2_2") (pintype "passive"))
      (node (ref "R56") (pin "1") (pinfunction "1_1") (pintype "passive"))
      (node (ref "SJ83") (pin "1") (pinfunction "1_1") (pintype "passive"))
    )
    (net (code "89") (name "/IOUT16") (class "Default")
      (node (ref "IC17") (pin "19") (pinfunction "IOUT_19") (pintype "bidirectional"))
      (node (ref "R67") (pin "2") (pinfunction "2_2") (pintype "passive"))
      (node (ref "R68") (pin "1") (pinfunction "1_1") (pintype "passive"))
      (node (ref "SJ101") (pin "1") (pinfunction "1_1") (pintype "passive"))
    )
    (net (code "90") (name "/IOUTB1") (class "Default")
      (node (ref "C6") (pin "1") (pinfunction "1_1") (pintype "passive"))
      (node (ref "IC1") (pin "20") (pinfunction "IOUTB_20") (pintype "bidirectional"))
      (node (ref "R4") (pin "2") (pinfunction "2_2") (pintype "passive"))
      (node (ref "SJ7") (pin "1") (pinfunction "1_1") (pintype "passive"))
    )
    (net (code "91") (name "/IOUTB2") (class "Default")
      (node (ref "C11") (pin "1") (pinfunction "1_1") (pintype "passive"))
      (node (ref "IC2") (pin "20") (pinfunction "IOUTB_20") (pintype "bidirectional"))
      (node (ref "R6") (pin "2") (pinfunction "2_2") (pintype "passive"))
      (node (ref "SJ10") (pin "1") (pinfunction "1_1") (pintype "passive"))
    )
    (net (code "92") (name "/IOUTB3") (class "Default")
      (node (ref "C17") (pin "1") (pinfunction "1_1") (pintype "passive"))
      (node (ref "IC3") (pin "20") (pinfunction "IOUTB_20") (pintype "bidirectional"))
      (node (ref "R10") (pin "2") (pinfunction "2_2") (pintype "passive"))
      (node (ref "SJ16") (pin "1") (pinfunction "1_1") (pintype "passive"))
    )
    (net (code "93") (name "/IOUTB4") (class "Default")
      (node (ref "C23") (pin "1") (pinfunction "1_1") (pintype "passive"))
      (node (ref "IC4") (pin "20") (pinfunction "IOUTB_20") (pintype "bidirectional"))
      (node (ref "R14") (pin "2") (pinfunction "2_2") (pintype "passive"))
      (node (ref "SJ22") (pin "1") (pinfunction "1_1") (pintype "passive"))
    )
    (net (code "94") (name "/IOUTB5") (class "Default")
      (node (ref "C29") (pin "1") (pinfunction "1_1") (pintype "passive"))
      (node (ref "IC5") (pin "20") (pinfunction "IOUTB_20") (pintype "bidirectional"))
      (node (ref "R18") (pin "2") (pinfunction "2_2") (pintype "passive"))
      (node (ref "SJ28") (pin "1") (pinfunction "1_1") (pintype "passive"))
    )
    (net (code "95") (name "/IOUTB6") (class "Default")
      (node (ref "C35") (pin "1") (pinfunction "1_1") (pintype "passive"))
      (node (ref "IC6") (pin "20") (pinfunction "IOUTB_20") (pintype "bidirectional"))
      (node (ref "R22") (pin "2") (pinfunction "2_2") (pintype "passive"))
      (node (ref "SJ34") (pin "1") (pinfunction "1_1") (pintype "passive"))
    )
    (net (code "96") (name "/IOUTB7") (class "Default")
      (node (ref "C41") (pin "1") (pinfunction "1_1") (pintype "passive"))
      (node (ref "IC7") (pin "20") (pinfunction "IOUTB_20") (pintype "bidirectional"))
      (node (ref "R26") (pin "2") (pinfunction "2_2") (pintype "passive"))
      (node (ref "SJ40") (pin "1") (pinfunction "1_1") (pintype "passive"))
    )
    (net (code "97") (name "/IOUTB8") (class "Default")
      (node (ref "C47") (pin "1") (pinfunction "1_1") (pintype "passive"))
      (node (ref "IC8") (pin "20") (pinfunction "IOUTB_20") (pintype "bidirectional"))
      (node (ref "R30") (pin "2") (pinfunction "2_2") (pintype "passive"))
      (node (ref "SJ46") (pin "1") (pinfunction "1_1") (pintype "passive"))
    )
    (net (code "98") (name "/IOUTB9") (class "Default")
      (node (ref "C53") (pin "1") (pinfunction "1_1") (pintype "passive"))
      (node (ref "IC9") (pin "20") (pinfunction "IOUTB_20") (pintype "bidirectional"))
      (node (ref "R34") (pin "2") (pinfunction "2_2") (pintype "passive"))
      (node (ref "SJ52") (pin "1") (pinfunction "1_1") (pintype "passive"))
    )
    (net (code "99") (name "/IOUTB10") (class "Default")
      (node (ref "C59") (pin "1") (pinfunction "1_1") (pintype "passive"))
      (node (ref "IC10") (pin "20") (pinfunction "IOUTB_20") (pintype "bidirectional"))
      (node (ref "R38") (pin "2") (pinfunction "2_2") (pintype "passive"))
      (node (ref "SJ58") (pin "1") (pinfunction "1_1") (pintype "passive"))
    )
    (net (code "100") (name "/IOUTB11") (class "Default")
      (node (ref "C65") (pin "1") (pinfunction "1_1") (pintype "passive"))
      (node (ref "IC11") (pin "20") (pinfunction "IOUTB_20") (pintype "bidirectional"))
      (node (ref "R42") (pin "2") (pinfunction "2_2") (pintype "passive"))
      (node (ref "SJ64") (pin "1") (pinfunction "1_1") (pintype "passive"))
    )
    (net (code "101") (name "/IOUTB12") (class "Default")
      (node (ref "C71") (pin "1") (pinfunction "1_1") (pintype "passive"))
      (node (ref "IC12") (pin "20") (pinfunction "IOUTB_20") (pintype "bidirectional"))
      (node (ref "R46") (pin "2") (pinfunction "2_2") (pintype "passive"))
      (node (ref "SJ70") (pin "1") (pinfunction "1_1") (pintype "passive"))
    )
    (net (code "102") (name "/IOUTB13") (class "Default")
      (node (ref "C77") (pin "1") (pinfunction "1_1") (pintype "passive"))
      (node (ref "IC13") (pin "20") (pinfunction "IOUTB_20") (pintype "bidirectional"))
      (node (ref "R50") (pin "2") (pinfunction "2_2") (pintype "passive"))
      (node (ref "SJ76") (pin "1") (pinfunction "1_1") (pintype "passive"))
    )
    (net (code "103") (name "/IOUTB14") (class "Default")
      (node (ref "C95") (pin "1") (pinfunction "1_1") (pintype "passive"))
      (node (ref "IC16") (pin "20") (pinfunction "IOUTB_20") (pintype "bidirectional"))
      (node (ref "R62") (pin "2") (pinfunction "2_2") (pintype "passive"))
      (node (ref "SJ94") (pin "1") (pinfunction "1_1") (pintype "passive"))
    )
    (net (code "104") (name "/IOUTB15") (class "Default")
      (node (ref "C83") (pin "1") (pinfunction "1_1") (pintype "passive"))
      (node (ref "IC14") (pin "20") (pinfunction "IOUTB_20") (pintype "bidirectional"))
      (node (ref "R54") (pin "2") (pinfunction "2_2") (pintype "passive"))
      (node (ref "SJ82") (pin "1") (pinfunction "1_1") (pintype "passive"))
    )
    (net (code "105") (name "/IOUTB16") (class "Default")
      (node (ref "C101") (pin "1") (pinfunction "1_1") (pintype "passive"))
      (node (ref "IC17") (pin "20") (pinfunction "IOUTB_20") (pintype "bidirectional"))
      (node (ref "R66") (pin "2") (pinfunction "2_2") (pintype "passive"))
      (node (ref "SJ100") (pin "1") (pinfunction "1_1") (pintype "passive"))
    )
    (net (code "106") (name "/MCLK_A") (class "Default")
      (node (ref "IC1") (pin "8") (pinfunction "MCLK_8") (pintype "bidirectional"))
      (node (ref "IC2") (pin "8") (pinfunction "MCLK_8") (pintype "bidirectional"))
      (node (ref "IC3") (pin "8") (pinfunction "MCLK_8") (pintype "bidirectional"))
      (node (ref "IC4") (pin "8") (pinfunction "MCLK_8") (pintype "bidirectional"))
      (node (ref "J2") (pin "6") (pinfunction "6_6") (pintype "passive"))
    )
    (net (code "107") (name "/MCLK_B") (class "Default")
      (node (ref "IC5") (pin "8") (pinfunction "MCLK_8") (pintype "bidirectional"))
      (node (ref "IC6") (pin "8") (pinfunction "MCLK_8") (pintype "bidirectional"))
      (node (ref "IC7") (pin "8") (pinfunction "MCLK_8") (pintype "bidirectional"))
      (node (ref "IC8") (pin "8") (pinfunction "MCLK_8") (pintype "bidirectional"))
      (node (ref "J4") (pin "4") (pinfunction "4_4") (pintype "passive"))
    )
    (net (code "108") (name "/MCLK_C") (class "Default")
      (node (ref "IC10") (pin "8") (pinfunction "MCLK_8") (pintype "bidirectional"))
      (node (ref "IC11") (pin "8") (pinfunction "MCLK_8") (pintype "bidirectional"))
      (node (ref "IC12") (pin "8") (pinfunction "MCLK_8") (pintype "bidirectional"))
      (node (ref "IC9") (pin "8") (pinfunction "MCLK_8") (pintype "bidirectional"))
      (node (ref "J1") (pin "4") (pinfunction "4_4") (pintype "passive"))
    )
    (net (code "109") (name "/MCLK_D") (class "Default")
      (node (ref "IC13") (pin "8") (pinfunction "MCLK_8") (pintype "bidirectional"))
      (node (ref "IC14") (pin "8") (pinfunction "MCLK_8") (pintype "bidirectional"))
      (node (ref "IC16") (pin "8") (pinfunction "MCLK_8") (pintype "bidirectional"))
      (node (ref "IC17") (pin "8") (pinfunction "MCLK_8") (pintype "bidirectional"))
      (node (ref "J7") (pin "6") (pinfunction "6_6") (pintype "passive"))
    )
    (net (code "110") (name "/POT_A_1") (class "Default")
      (node (ref "R57") (pin "2") (pinfunction "2_2") (pintype "passive"))
      (node (ref "U2") (pin "4") (pinfunction "IN-_4") (pintype "input"))
      (node (ref "U3") (pin "2") (pinfunction "A_2") (pintype "passive"))
    )
    (net (code "111") (name "/POT_A_2") (class "Default")
      (node (ref "R59") (pin "2") (pinfunction "2_2") (pintype "passive"))
      (node (ref "U8") (pin "2") (pinfunction "A_2") (pintype "passive"))
      (node (ref "U9") (pin "4") (pinfunction "IN-_4") (pintype "input"))
    )
    (net (code "112") (name "/POT_A_3") (class "Default")
      (node (ref "R70") (pin "2") (pinfunction "2_2") (pintype "passive"))
      (node (ref "U17") (pin "2") (pinfunction "A_2") (pintype "passive"))
      (node (ref "U18") (pin "4") (pinfunction "IN-_4") (pintype "input"))
    )
    (net (code "113") (name "/POT_A_4") (class "Default")
      (node (ref "R71") (pin "2") (pinfunction "2_2") (pintype "passive"))
      (node (ref "U20") (pin "2") (pinfunction "A_2") (pintype "passive"))
      (node (ref "U21") (pin "4") (pinfunction "IN-_4") (pintype "input"))
    )
    (net (code "114") (name "/POT_A_5") (class "Default")
      (node (ref "R60") (pin "2") (pinfunction "2_2") (pintype "passive"))
      (node (ref "U11") (pin "2") (pinfunction "A_2") (pintype "passive"))
      (node (ref "U12") (pin "4") (pinfunction "IN-_4") (pintype "input"))
    )
    (net (code "115") (name "/POT_A_6") (class "Default")
      (node (ref "R69") (pin "2") (pinfunction "2_2") (pintype "passive"))
      (node (ref "U14") (pin "2") (pinfunction "A_2") (pintype "passive"))
      (node (ref "U15") (pin "4") (pinfunction "IN-_4") (pintype "input"))
    )
    (net (code "116") (name "/POT_A_7") (class "Default")
      (node (ref "R72") (pin "2") (pinfunction "2_2") (pintype "passive"))
      (node (ref "U23") (pin "2") (pinfunction "A_2") (pintype "passive"))
      (node (ref "U24") (pin "4") (pinfunction "IN-_4") (pintype "input"))
    )
    (net (code "117") (name "/POT_A_8") (class "Default")
      (node (ref "R73") (pin "2") (pinfunction "2_2") (pintype "passive"))
      (node (ref "U26") (pin "2") (pinfunction "A_2") (pintype "passive"))
      (node (ref "U27") (pin "4") (pinfunction "IN-_4") (pintype "input"))
    )
    (net (code "118") (name "/POT_A_9") (class "Default")
      (node (ref "R74") (pin "2") (pinfunction "2_2") (pintype "passive"))
      (node (ref "U29") (pin "2") (pinfunction "A_2") (pintype "passive"))
      (node (ref "U30") (pin "4") (pinfunction "IN-_4") (pintype "input"))
    )
    (net (code "119") (name "/POT_A_10") (class "Default")
      (node (ref "R75") (pin "2") (pinfunction "2_2") (pintype "passive"))
      (node (ref "U32") (pin "2") (pinfunction "A_2") (pintype "passive"))
      (node (ref "U33") (pin "4") (pinfunction "IN-_4") (pintype "input"))
    )
    (net (code "120") (name "/POT_A_11") (class "Default")
      (node (ref "R78") (pin "2") (pinfunction "2_2") (pintype "passive"))
      (node (ref "U41") (pin "2") (pinfunction "A_2") (pintype "passive"))
      (node (ref "U42") (pin "4") (pinfunction "IN-_4") (pintype "input"))
    )
    (net (code "121") (name "/POT_A_12") (class "Default")
      (node (ref "R79") (pin "2") (pinfunction "2_2") (pintype "passive"))
      (node (ref "U44") (pin "2") (pinfunction "A_2") (pintype "passive"))
      (node (ref "U45") (pin "4") (pinfunction "IN-_4") (pintype "input"))
    )
    (net (code "122") (name "/POT_A_13") (class "Default")
      (node (ref "R76") (pin "2") (pinfunction "2_2") (pintype "passive"))
      (node (ref "U35") (pin "2") (pinfunction "A_2") (pintype "passive"))
      (node (ref "U36") (pin "4") (pinfunction "IN-_4") (pintype "input"))
    )
    (net (code "123") (name "/POT_A_14") (class "Default")
      (node (ref "R77") (pin "2") (pinfunction "2_2") (pintype "passive"))
      (node (ref "U38") (pin "2") (pinfunction "A_2") (pintype "passive"))
      (node (ref "U39") (pin "4") (pinfunction "IN-_4") (pintype "input"))
    )
    (net (code "124") (name "/POT_A_15") (class "Default")
      (node (ref "R80") (pin "2") (pinfunction "2_2") (pintype "passive"))
      (node (ref "U47") (pin "2") (pinfunction "A_2") (pintype "passive"))
      (node (ref "U48") (pin "4") (pinfunction "IN-_4") (pintype "input"))
    )
    (net (code "125") (name "/POT_A_16") (class "Default")
      (node (ref "R81") (pin "2") (pinfunction "2_2") (pintype "passive"))
      (node (ref "U50") (pin "2") (pinfunction "A_2") (pintype "passive"))
      (node (ref "U51") (pin "4") (pinfunction "IN-_4") (pintype "input"))
    )
    (net (code "126") (name "/POT_W_1") (class "Default")
      (node (ref "JP3") (pin "1") (pinfunction "1_1") (pintype "passive"))
      (node (ref "U2") (pin "1") (pinfunction "OUT_1") (pintype "output"))
      (node (ref "U3") (pin "3") (pinfunction "W_3") (pintype "passive"))
    )
    (net (code "127") (name "/POT_W_2") (class "Default")
      (node (ref "JP4") (pin "1") (pinfunction "1_1") (pintype "passive"))
      (node (ref "U8") (pin "3") (pinfunction "W_3") (pintype "passive"))
      (node (ref "U9") (pin "1") (pinfunction "OUT_1") (pintype "output"))
    )
    (net (code "128") (name "/POT_W_3") (class "Default")
      (node (ref "JP6") (pin "1") (pinfunction "1_1") (pintype "passive"))
      (node (ref "U17") (pin "3") (pinfunction "W_3") (pintype "passive"))
      (node (ref "U18") (pin "1") (pinfunction "OUT_1") (pintype "output"))
    )
    (net (code "129") (name "/POT_W_4") (class "Default")
      (node (ref "JP7") (pin "1") (pinfunction "1_1") (pintype "passive"))
      (node (ref "U20") (pin "3") (pinfunction "W_3") (pintype "passive"))
      (node (ref "U21") (pin "1") (pinfunction "OUT_1") (pintype "output"))
    )
    (net (code "130") (name "/POT_W_5") (class "Default")
      (node (ref "JP1") (pin "1") (pinfunction "1_1") (pintype "passive"))
      (node (ref "U11") (pin "3") (pinfunction "W_3") (pintype "passive"))
      (node (ref "U12") (pin "1") (pinfunction "OUT_1") (pintype "output"))
    )
    (net (code "131") (name "/POT_W_6") (class "Default")
      (node (ref "JP2") (pin "1") (pinfunction "1_1") (pintype "passive"))
      (node (ref "U14") (pin "3") (pinfunction "W_3") (pintype "passive"))
      (node (ref "U15") (pin "1") (pinfunction "OUT_1") (pintype "output"))
    )
    (net (code "132") (name "/POT_W_7") (class "Default")
      (node (ref "JP5") (pin "1") (pinfunction "1_1") (pintype "passive"))
      (node (ref "U23") (pin "3") (pinfunction "W_3") (pintype "passive"))
      (node (ref "U24") (pin "1") (pinfunction "OUT_1") (pintype "output"))
    )
    (net (code "133") (name "/POT_W_8") (class "Default")
      (node (ref "JP8") (pin "1") (pinfunction "1_1") (pintype "passive"))
      (node (ref "U26") (pin "3") (pinfunction "W_3") (pintype "passive"))
      (node (ref "U27") (pin "1") (pinfunction "OUT_1") (pintype "output"))
    )
    (net (code "134") (name "/POT_W_9") (class "Default")
      (node (ref "JP9") (pin "1") (pinfunction "1_1") (pintype "passive"))
      (node (ref "U29") (pin "3") (pinfunction "W_3") (pintype "passive"))
      (node (ref "U30") (pin "1") (pinfunction "OUT_1") (pintype "output"))
    )
    (net (code "135") (name "/POT_W_10") (class "Default")
      (node (ref "JP10") (pin "1") (pinfunction "1_1") (pintype "passive"))
      (node (ref "U32") (pin "3") (pinfunction "W_3") (pintype "passive"))
      (node (ref "U33") (pin "1") (pinfunction "OUT_1") (pintype "output"))
    )
    (net (code "136") (name "/POT_W_11") (class "Default")
      (node (ref "JP11") (pin "1") (pinfunction "1_1") (pintype "passive"))
      (node (ref "U41") (pin "3") (pinfunction "W_3") (pintype "passive"))
      (node (ref "U42") (pin "1") (pinfunction "OUT_1") (pintype "output"))
    )
    (net (code "137") (name "/POT_W_12") (class "Default")
      (node (ref "JP12") (pin "1") (pinfunction "1_1") (pintype "passive"))
      (node (ref "U44") (pin "3") (pinfunction "W_3") (pintype "passive"))
      (node (ref "U45") (pin "1") (pinfunction "OUT_1") (pintype "output"))
    )
    (net (code "138") (name "/POT_W_13") (class "Default")
      (node (ref "JP13") (pin "1") (pinfunction "1_1") (pintype "passive"))
      (node (ref "U35") (pin "3") (pinfunction "W_3") (pintype "passive"))
      (node (ref "U36") (pin "1") (pinfunction "OUT_1") (pintype "output"))
    )
    (net (code "139") (name "/POT_W_14") (class "Default")
      (node (ref "JP14") (pin "1") (pinfunction "1_1") (pintype "passive"))
      (node (ref "U38") (pin "3") (pinfunction "W_3") (pintype "passive"))
      (node (ref "U39") (pin "1") (pinfunction "OUT_1") (pintype "output"))
    )
    (net (code "140") (name "/POT_W_15") (class "Default")
      (node (ref "JP15") (pin "1") (pinfunction "1_1") (pintype "passive"))
      (node (ref "U47") (pin "3") (pinfunction "W_3") (pintype "passive"))
      (node (ref "U48") (pin "1") (pinfunction "OUT_1") (pintype "output"))
    )
    (net (code "141") (name "/POT_W_16") (class "Default")
      (node (ref "JP16") (pin "1") (pinfunction "1_1") (pintype "passive"))
      (node (ref "U50") (pin "3") (pinfunction "W_3") (pintype "passive"))
      (node (ref "U51") (pin "1") (pinfunction "OUT_1") (pintype "output"))
    )
    (net (code "142") (name "/PSELECT_A") (class "Default")
      (node (ref "IC1") (pin "10") (pinfunction "PSELECT_10") (pintype "bidirectional"))
      (node (ref "IC2") (pin "10") (pinfunction "PSELECT_10") (pintype "bidirectional"))
      (node (ref "IC3") (pin "10") (pinfunction "PSELECT_10") (pintype "bidirectional"))
      (node (ref "IC4") (pin "10") (pinfunction "PSELECT_10") (pintype "bidirectional"))
      (node (ref "J2") (pin "4") (pinfunction "4_4") (pintype "passive"))
    )
    (net (code "143") (name "/PSELECT_B") (class "Default")
      (node (ref "IC5") (pin "10") (pinfunction "PSELECT_10") (pintype "bidirectional"))
      (node (ref "IC6") (pin "10") (pinfunction "PSELECT_10") (pintype "bidirectional"))
      (node (ref "IC7") (pin "10") (pinfunction "PSELECT_10") (pintype "bidirectional"))
      (node (ref "IC8") (pin "10") (pinfunction "PSELECT_10") (pintype "bidirectional"))
      (node (ref "J4") (pin "2") (pinfunction "2_2") (pintype "passive"))
    )
    (net (code "144") (name "/PSELECT_C") (class "Default")
      (node (ref "IC10") (pin "10") (pinfunction "PSELECT_10") (pintype "bidirectional"))
      (node (ref "IC11") (pin "10") (pinfunction "PSELECT_10") (pintype "bidirectional"))
      (node (ref "IC12") (pin "10") (pinfunction "PSELECT_10") (pintype "bidirectional"))
      (node (ref "IC9") (pin "10") (pinfunction "PSELECT_10") (pintype "bidirectional"))
      (node (ref "J1") (pin "2") (pinfunction "2_2") (pintype "passive"))
    )
    (net (code "145") (name "/PSELECT_D") (class "Default")
      (node (ref "IC13") (pin "10") (pinfunction "PSELECT_10") (pintype "bidirectional"))
      (node (ref "IC14") (pin "10") (pinfunction "PSELECT_10") (pintype "bidirectional"))
      (node (ref "IC16") (pin "10") (pinfunction "PSELECT_10") (pintype "bidirectional"))
      (node (ref "IC17") (pin "10") (pinfunction "PSELECT_10") (pintype "bidirectional"))
      (node (ref "J7") (pin "4") (pinfunction "4_4") (pintype "passive"))
    )
    (net (code "146") (name "/RESET_A") (class "Default")
      (node (ref "IC1") (pin "11") (pinfunction "RESET_11") (pintype "power_in"))
      (node (ref "IC2") (pin "11") (pinfunction "RESET_11") (pintype "power_in"))
      (node (ref "IC3") (pin "11") (pinfunction "RESET_11") (pintype "power_in"))
      (node (ref "IC4") (pin "11") (pinfunction "RESET_11") (pintype "power_in"))
      (node (ref "J2") (pin "16") (pinfunction "16_16") (pintype "passive"))
    )
    (net (code "147") (name "/RESET_B") (class "Default")
      (node (ref "IC5") (pin "11") (pinfunction "RESET_11") (pintype "power_in"))
      (node (ref "IC6") (pin "11") (pinfunction "RESET_11") (pintype "power_in"))
      (node (ref "IC7") (pin "11") (pinfunction "RESET_11") (pintype "power_in"))
      (node (ref "IC8") (pin "11") (pinfunction "RESET_11") (pintype "power_in"))
      (node (ref "J4") (pin "14") (pinfunction "14_14") (pintype "passive"))
    )
    (net (code "148") (name "/RESET_C") (class "Default")
      (node (ref "IC10") (pin "11") (pinfunction "RESET_11") (pintype "power_in"))
      (node (ref "IC11") (pin "11") (pinfunction "RESET_11") (pintype "power_in"))
      (node (ref "IC12") (pin "11") (pinfunction "RESET_11") (pintype "power_in"))
      (node (ref "IC9") (pin "11") (pinfunction "RESET_11") (pintype "power_in"))
      (node (ref "J1") (pin "14") (pinfunction "14_14") (pintype "passive"))
    )
    (net (code "149") (name "/RESET_D") (class "Default")
      (node (ref "IC13") (pin "11") (pinfunction "RESET_11") (pintype "power_in"))
      (node (ref "IC14") (pin "11") (pinfunction "RESET_11") (pintype "power_in"))
      (node (ref "IC16") (pin "11") (pinfunction "RESET_11") (pintype "power_in"))
      (node (ref "IC17") (pin "11") (pinfunction "RESET_11") (pintype "power_in"))
      (node (ref "J7") (pin "16") (pinfunction "16_16") (pintype "passive"))
    )
    (net (code "150") (name "/SCLK2_A") (class "Default")
      (node (ref "J2") (pin "11") (pinfunction "11_11") (pintype "passive"))
      (node (ref "U17") (pin "9") (pinfunction "SCLK_9") (pintype "input"))
      (node (ref "U20") (pin "9") (pinfunction "SCLK_9") (pintype "input"))
      (node (ref "U3") (pin "9") (pinfunction "SCLK_9") (pintype "input"))
      (node (ref "U8") (pin "9") (pinfunction "SCLK_9") (pintype "input"))
    )
    (net (code "151") (name "/SCLK2_B") (class "Default")
      (node (ref "J4") (pin "9") (pinfunction "9_9") (pintype "passive"))
      (node (ref "U11") (pin "9") (pinfunction "SCLK_9") (pintype "input"))
      (node (ref "U14") (pin "9") (pinfunction "SCLK_9") (pintype "input"))
      (node (ref "U23") (pin "9") (pinfunction "SCLK_9") (pintype "input"))
      (node (ref "U26") (pin "9") (pinfunction "SCLK_9") (pintype "input"))
    )
    (net (code "152") (name "/SCLK2_C") (class "Default")
      (node (ref "J1") (pin "9") (pinfunction "9_9") (pintype "passive"))
      (node (ref "U29") (pin "9") (pinfunction "SCLK_9") (pintype "input"))
      (node (ref "U32") (pin "9") (pinfunction "SCLK_9") (pintype "input"))
      (node (ref "U41") (pin "9") (pinfunction "SCLK_9") (pintype "input"))
      (node (ref "U44") (pin "9") (pinfunction "SCLK_9") (pintype "input"))
    )
    (net (code "153") (name "/SCLK2_D") (class "Default")
      (node (ref "J7") (pin "11") (pinfunction "11_11") (pintype "passive"))
      (node (ref "U35") (pin "9") (pinfunction "SCLK_9") (pintype "input"))
      (node (ref "U38") (pin "9") (pinfunction "SCLK_9") (pintype "input"))
      (node (ref "U47") (pin "9") (pinfunction "SCLK_9") (pintype "input"))
      (node (ref "U50") (pin "9") (pinfunction "SCLK_9") (pintype "input"))
    )
    (net (code "154") (name "/SCLK_1_A") (class "Default")
      (node (ref "IC1") (pin "14") (pinfunction "SCLK_14") (pintype "bidirectional"))
      (node (ref "IC2") (pin "14") (pinfunction "SCLK_14") (pintype "bidirectional"))
      (node (ref "IC3") (pin "14") (pinfunction "SCLK_14") (pintype "bidirectional"))
      (node (ref "IC4") (pin "14") (pinfunction "SCLK_14") (pintype "bidirectional"))
      (node (ref "J2") (pin "13") (pinfunction "13_13") (pintype "passive"))
    )
    (net (code "155") (name "/SCLK_1_B") (class "Default")
      (node (ref "IC5") (pin "14") (pinfunction "SCLK_14") (pintype "bidirectional"))
      (node (ref "IC6") (pin "14") (pinfunction "SCLK_14") (pintype "bidirectional"))
      (node (ref "IC7") (pin "14") (pinfunction "SCLK_14") (pintype "bidirectional"))
      (node (ref "IC8") (pin "14") (pinfunction "SCLK_14") (pintype "bidirectional"))
      (node (ref "J4") (pin "11") (pinfunction "11_11") (pintype "passive"))
    )
    (net (code "156") (name "/SCLK_1_C") (class "Default")
      (node (ref "IC10") (pin "14") (pinfunction "SCLK_14") (pintype "bidirectional"))
      (node (ref "IC11") (pin "14") (pinfunction "SCLK_14") (pintype "bidirectional"))
      (node (ref "IC12") (pin "14") (pinfunction "SCLK_14") (pintype "bidirectional"))
      (node (ref "IC9") (pin "14") (pinfunction "SCLK_14") (pintype "bidirectional"))
      (node (ref "J1") (pin "11") (pinfunction "11_11") (pintype "passive"))
    )
    (net (code "157") (name "/SCLK_1_D") (class "Default")
      (node (ref "IC13") (pin "14") (pinfunction "SCLK_14") (pintype "bidirectional"))
      (node (ref "IC14") (pin "14") (pinfunction "SCLK_14") (pintype "bidirectional"))
      (node (ref "IC16") (pin "14") (pinfunction "SCLK_14") (pintype "bidirectional"))
      (node (ref "IC17") (pin "14") (pinfunction "SCLK_14") (pintype "bidirectional"))
      (node (ref "J7") (pin "13") (pinfunction "13_13") (pintype "passive"))
    )
    (net (code "158") (name "/SDATA_1_A") (class "Default")
      (node (ref "IC1") (pin "13") (pinfunction "SDATA_13") (pintype "bidirectional"))
      (node (ref "IC2") (pin "13") (pinfunction "SDATA_13") (pintype "bidirectional"))
      (node (ref "IC3") (pin "13") (pinfunction "SDATA_13") (pintype "bidirectional"))
      (node (ref "IC4") (pin "13") (pinfunction "SDATA_13") (pintype "bidirectional"))
      (node (ref "J2") (pin "14") (pinfunction "14_14") (pintype "passive"))
    )
    (net (code "159") (name "/SDATA_1_B") (class "Default")
      (node (ref "IC5") (pin "13") (pinfunction "SDATA_13") (pintype "bidirectional"))
      (node (ref "IC6") (pin "13") (pinfunction "SDATA_13") (pintype "bidirectional"))
      (node (ref "IC7") (pin "13") (pinfunction "SDATA_13") (pintype "bidirectional"))
      (node (ref "IC8") (pin "13") (pinfunction "SDATA_13") (pintype "bidirectional"))
      (node (ref "J4") (pin "12") (pinfunction "12_12") (pintype "passive"))
    )
    (net (code "160") (name "/SDATA_1_C") (class "Default")
      (node (ref "IC10") (pin "13") (pinfunction "SDATA_13") (pintype "bidirectional"))
      (node (ref "IC11") (pin "13") (pinfunction "SDATA_13") (pintype "bidirectional"))
      (node (ref "IC12") (pin "13") (pinfunction "SDATA_13") (pintype "bidirectional"))
      (node (ref "IC9") (pin "13") (pinfunction "SDATA_13") (pintype "bidirectional"))
      (node (ref "J1") (pin "12") (pinfunction "12_12") (pintype "passive"))
    )
    (net (code "161") (name "/SDATA_1_D") (class "Default")
      (node (ref "IC13") (pin "13") (pinfunction "SDATA_13") (pintype "bidirectional"))
      (node (ref "IC14") (pin "13") (pinfunction "SDATA_13") (pintype "bidirectional"))
      (node (ref "IC16") (pin "13") (pinfunction "SDATA_13") (pintype "bidirectional"))
      (node (ref "IC17") (pin "13") (pinfunction "SDATA_13") (pintype "bidirectional"))
      (node (ref "J7") (pin "14") (pinfunction "14_14") (pintype "passive"))
    )
    (net (code "162") (name "/SDO_2_A") (class "Default")
      (node (ref "J2") (pin "9") (pinfunction "9_9") (pintype "passive"))
      (node (ref "U17") (pin "7") (pinfunction "SDO_7") (pintype "output"))
      (node (ref "U20") (pin "7") (pinfunction "SDO_7") (pintype "output"))
      (node (ref "U3") (pin "7") (pinfunction "SDO_7") (pintype "output"))
      (node (ref "U8") (pin "7") (pinfunction "SDO_7") (pintype "output"))
    )
    (net (code "163") (name "/SDO_2_B") (class "Default")
      (node (ref "J4") (pin "7") (pinfunction "7_7") (pintype "passive"))
      (node (ref "U11") (pin "7") (pinfunction "SDO_7") (pintype "output"))
      (node (ref "U14") (pin "7") (pinfunction "SDO_7") (pintype "output"))
      (node (ref "U23") (pin "7") (pinfunction "SDO_7") (pintype "output"))
      (node (ref "U26") (pin "7") (pinfunction "SDO_7") (pintype "output"))
    )
    (net (code "164") (name "/SDO_2_C") (class "Default")
      (node (ref "J1") (pin "7") (pinfunction "7_7") (pintype "passive"))
      (node (ref "U29") (pin "7") (pinfunction "SDO_7") (pintype "output"))
      (node (ref "U32") (pin "7") (pinfunction "SDO_7") (pintype "output"))
      (node (ref "U41") (pin "7") (pinfunction "SDO_7") (pintype "output"))
      (node (ref "U44") (pin "7") (pinfunction "SDO_7") (pintype "output"))
    )
    (net (code "165") (name "/SDO_2_D") (class "Default")
      (node (ref "J7") (pin "9") (pinfunction "9_9") (pintype "passive"))
      (node (ref "U35") (pin "7") (pinfunction "SDO_7") (pintype "output"))
      (node (ref "U38") (pin "7") (pinfunction "SDO_7") (pintype "output"))
      (node (ref "U47") (pin "7") (pinfunction "SDO_7") (pintype "output"))
      (node (ref "U50") (pin "7") (pinfunction "SDO_7") (pintype "output"))
    )
    (net (code "166") (name "/SIGN_BIT_OUT1") (class "Default")
      (node (ref "IC1") (pin "16") (pinfunction "SIGN_BIT_OUT_16") (pintype "bidirectional"))
      (node (ref "SJ2") (pin "1") (pinfunction "1_1") (pintype "passive"))
    )
    (net (code "167") (name "/SIGN_BIT_OUT2") (class "Default")
      (node (ref "IC2") (pin "16") (pinfunction "SIGN_BIT_OUT_16") (pintype "bidirectional"))
      (node (ref "SJ8") (pin "1") (pinfunction "1_1") (pintype "passive"))
    )
    (net (code "168") (name "/SIGN_BIT_OUT3") (class "Default")
      (node (ref "IC3") (pin "16") (pinfunction "SIGN_BIT_OUT_16") (pintype "bidirectional"))
      (node (ref "SJ14") (pin "1") (pinfunction "1_1") (pintype "passive"))
    )
    (net (code "169") (name "/SIGN_BIT_OUT4") (class "Default")
      (node (ref "IC4") (pin "16") (pinfunction "SIGN_BIT_OUT_16") (pintype "bidirectional"))
      (node (ref "SJ20") (pin "1") (pinfunction "1_1") (pintype "passive"))
    )
    (net (code "170") (name "/SIGN_BIT_OUT5") (class "Default")
      (node (ref "IC5") (pin "16") (pinfunction "SIGN_BIT_OUT_16") (pintype "bidirectional"))
      (node (ref "SJ26") (pin "1") (pinfunction "1_1") (pintype "passive"))
    )
    (net (code "171") (name "/SIGN_BIT_OUT6") (class "Default")
      (node (ref "IC6") (pin "16") (pinfunction "SIGN_BIT_OUT_16") (pintype "bidirectional"))
      (node (ref "SJ32") (pin "1") (pinfunction "1_1") (pintype "passive"))
    )
    (net (code "172") (name "/SIGN_BIT_OUT7") (class "Default")
      (node (ref "IC7") (pin "16") (pinfunction "SIGN_BIT_OUT_16") (pintype "bidirectional"))
      (node (ref "SJ38") (pin "1") (pinfunction "1_1") (pintype "passive"))
    )
    (net (code "173") (name "/SIGN_BIT_OUT8") (class "Default")
      (node (ref "IC8") (pin "16") (pinfunction "SIGN_BIT_OUT_16") (pintype "bidirectional"))
      (node (ref "SJ44") (pin "1") (pinfunction "1_1") (pintype "passive"))
    )
    (net (code "174") (name "/SIGN_BIT_OUT9") (class "Default")
      (node (ref "IC9") (pin "16") (pinfunction "SIGN_BIT_OUT_16") (pintype "bidirectional"))
      (node (ref "SJ50") (pin "1") (pinfunction "1_1") (pintype "passive"))
    )
    (net (code "175") (name "/SIGN_BIT_OUT10") (class "Default")
      (node (ref "IC10") (pin "16") (pinfunction "SIGN_BIT_OUT_16") (pintype "bidirectional"))
      (node (ref "SJ56") (pin "1") (pinfunction "1_1") (pintype "passive"))
    )
    (net (code "176") (name "/SIGN_BIT_OUT11") (class "Default")
      (node (ref "IC11") (pin "16") (pinfunction "SIGN_BIT_OUT_16") (pintype "bidirectional"))
      (node (ref "SJ62") (pin "1") (pinfunction "1_1") (pintype "passive"))
    )
    (net (code "177") (name "/SIGN_BIT_OUT12") (class "Default")
      (node (ref "IC12") (pin "16") (pinfunction "SIGN_BIT_OUT_16") (pintype "bidirectional"))
      (node (ref "SJ68") (pin "1") (pinfunction "1_1") (pintype "passive"))
    )
    (net (code "178") (name "/SIGN_BIT_OUT13") (class "Default")
      (node (ref "IC13") (pin "16") (pinfunction "SIGN_BIT_OUT_16") (pintype "bidirectional"))
      (node (ref "SJ74") (pin "1") (pinfunction "1_1") (pintype "passive"))
    )
    (net (code "179") (name "/SIGN_BIT_OUT14") (class "Default")
      (node (ref "IC16") (pin "16") (pinfunction "SIGN_BIT_OUT_16") (pintype "bidirectional"))
      (node (ref "SJ92") (pin "1") (pinfunction "1_1") (pintype "passive"))
    )
    (net (code "180") (name "/SIGN_BIT_OUT15") (class "Default")
      (node (ref "IC14") (pin "16") (pinfunction "SIGN_BIT_OUT_16") (pintype "bidirectional"))
      (node (ref "SJ80") (pin "1") (pinfunction "1_1") (pintype "passive"))
    )
    (net (code "181") (name "/SIGN_BIT_OUT16") (class "Default")
      (node (ref "IC17") (pin "16") (pinfunction "SIGN_BIT_OUT_16") (pintype "bidirectional"))
      (node (ref "SJ98") (pin "1") (pinfunction "1_1") (pintype "passive"))
    )
    (net (code "182") (name "/SLEEP_A") (class "Default")
      (node (ref "IC1") (pin "12") (pinfunction "SLEEP_12") (pintype "bidirectional"))
      (node (ref "IC2") (pin "12") (pinfunction "SLEEP_12") (pintype "bidirectional"))
      (node (ref "IC3") (pin "12") (pinfunction "SLEEP_12") (pintype "bidirectional"))
      (node (ref "IC4") (pin "12") (pinfunction "SLEEP_12") (pintype "bidirectional"))
      (node (ref "J2") (pin "15") (pinfunction "15_15") (pintype "passive"))
    )
    (net (code "183") (name "/SLEEP_B") (class "Default")
      (node (ref "IC5") (pin "12") (pinfunction "SLEEP_12") (pintype "bidirectional"))
      (node (ref "IC6") (pin "12") (pinfunction "SLEEP_12") (pintype "bidirectional"))
      (node (ref "IC7") (pin "12") (pinfunction "SLEEP_12") (pintype "bidirectional"))
      (node (ref "IC8") (pin "12") (pinfunction "SLEEP_12") (pintype "bidirectional"))
      (node (ref "J4") (pin "13") (pinfunction "13_13") (pintype "passive"))
    )
    (net (code "184") (name "/SLEEP_C") (class "Default")
      (node (ref "IC10") (pin "12") (pinfunction "SLEEP_12") (pintype "bidirectional"))
      (node (ref "IC11") (pin "12") (pinfunction "SLEEP_12") (pintype "bidirectional"))
      (node (ref "IC12") (pin "12") (pinfunction "SLEEP_12") (pintype "bidirectional"))
      (node (ref "IC9") (pin "12") (pinfunction "SLEEP_12") (pintype "bidirectional"))
      (node (ref "J1") (pin "13") (pinfunction "13_13") (pintype "passive"))
    )
    (net (code "185") (name "/SLEEP_D") (class "Default")
      (node (ref "IC13") (pin "12") (pinfunction "SLEEP_12") (pintype "bidirectional"))
      (node (ref "IC14") (pin "12") (pinfunction "SLEEP_12") (pintype "bidirectional"))
      (node (ref "IC16") (pin "12") (pinfunction "SLEEP_12") (pintype "bidirectional"))
      (node (ref "IC17") (pin "12") (pinfunction "SLEEP_12") (pintype "bidirectional"))
      (node (ref "J7") (pin "15") (pinfunction "15_15") (pintype "passive"))
    )
    (net (code "186") (name "/VNEG_1") (class "Default")
      (node (ref "C106") (pin "1") (pinfunction "1_1") (pintype "passive"))
      (node (ref "C90") (pin "2") (pinfunction "2_2") (pintype "passive"))
      (node (ref "U1") (pin "1") (pinfunction "OUT_1") (pintype "output"))
      (node (ref "U2") (pin "2") (pinfunction "GND_2") (pintype "passive"))
      (node (ref "U3") (pin "4") (pinfunction "VSS_4") (pintype "power_in"))
    )
    (net (code "187") (name "/VNEG_2") (class "Default")
      (node (ref "C117") (pin "2") (pinfunction "2_2") (pintype "passive"))
      (node (ref "C119") (pin "1") (pinfunction "1_1") (pintype "passive"))
      (node (ref "U7") (pin "1") (pinfunction "OUT_1") (pintype "output"))
      (node (ref "U8") (pin "4") (pinfunction "VSS_4") (pintype "power_in"))
      (node (ref "U9") (pin "2") (pinfunction "GND_2") (pintype "passive"))
    )
    (net (code "188") (name "/VNEG_3") (class "Default")
      (node (ref "C141") (pin "2") (pinfunction "2_2") (pintype "passive"))
      (node (ref "C143") (pin "1") (pinfunction "1_1") (pintype "passive"))
      (node (ref "U16") (pin "1") (pinfunction "OUT_1") (pintype "output"))
      (node (ref "U17") (pin "4") (pinfunction "VSS_4") (pintype "power_in"))
      (node (ref "U18") (pin "2") (pinfunction "GND_2") (pintype "passive"))
    )
    (net (code "189") (name "/VNEG_4") (class "Default")
      (node (ref "C149") (pin "2") (pinfunction "2_2") (pintype "passive"))
      (node (ref "C151") (pin "1") (pinfunction "1_1") (pintype "passive"))
      (node (ref "U19") (pin "1") (pinfunction "OUT_1") (pintype "output"))
      (node (ref "U20") (pin "4") (pinfunction "VSS_4") (pintype "power_in"))
      (node (ref "U21") (pin "2") (pinfunction "GND_2") (pintype "passive"))
    )
    (net (code "190") (name "/VNEG_5") (class "Default")
      (node (ref "C125") (pin "2") (pinfunction "2_2") (pintype "passive"))
      (node (ref "C127") (pin "1") (pinfunction "1_1") (pintype "passive"))
      (node (ref "U10") (pin "1") (pinfunction "OUT_1") (pintype "output"))
      (node (ref "U11") (pin "4") (pinfunction "VSS_4") (pintype "power_in"))
      (node (ref "U12") (pin "2") (pinfunction "GND_2") (pintype "passive"))
    )
    (net (code "191") (name "/VNEG_6") (class "Default")
      (node (ref "C133") (pin "2") (pinfunction "2_2") (pintype "passive"))
      (node (ref "C135") (pin "1") (pinfunction "1_1") (pintype "passive"))
      (node (ref "U13") (pin "1") (pinfunction "OUT_1") (pintype "output"))
      (node (ref "U14") (pin "4") (pinfunction "VSS_4") (pintype "power_in"))
      (node (ref "U15") (pin "2") (pinfunction "GND_2") (pintype "passive"))
    )
    (net (code "192") (name "/VNEG_7") (class "Default")
      (node (ref "C157") (pin "2") (pinfunction "2_2") (pintype "passive"))
      (node (ref "C159") (pin "1") (pinfunction "1_1") (pintype "passive"))
      (node (ref "U22") (pin "1") (pinfunction "OUT_1") (pintype "output"))
      (node (ref "U23") (pin "4") (pinfunction "VSS_4") (pintype "power_in"))
      (node (ref "U24") (pin "2") (pinfunction "GND_2") (pintype "passive"))
    )
    (net (code "193") (name "/VNEG_8") (class "Default")
      (node (ref "C165") (pin "2") (pinfunction "2_2") (pintype "passive"))
      (node (ref "C167") (pin "1") (pinfunction "1_1") (pintype "passive"))
      (node (ref "U25") (pin "1") (pinfunction "OUT_1") (pintype "output"))
      (node (ref "U26") (pin "4") (pinfunction "VSS_4") (pintype "power_in"))
      (node (ref "U27") (pin "2") (pinfunction "GND_2") (pintype "passive"))
    )
    (net (code "194") (name "/VNEG_9") (class "Default")
      (node (ref "C173") (pin "2") (pinfunction "2_2") (pintype "passive"))
      (node (ref "C175") (pin "1") (pinfunction "1_1") (pintype "passive"))
      (node (ref "U28") (pin "1") (pinfunction "OUT_1") (pintype "output"))
      (node (ref "U29") (pin "4") (pinfunction "VSS_4") (pintype "power_in"))
      (node (ref "U30") (pin "2") (pinfunction "GND_2") (pintype "passive"))
    )
    (net (code "195") (name "/VNEG_10") (class "Default")
      (node (ref "C181") (pin "2") (pinfunction "2_2") (pintype "passive"))
      (node (ref "C183") (pin "1") (pinfunction "1_1") (pintype "passive"))
      (node (ref "U31") (pin "1") (pinfunction "OUT_1") (pintype "output"))
      (node (ref "U32") (pin "4") (pinfunction "VSS_4") (pintype "power_in"))
      (node (ref "U33") (pin "2") (pinfunction "GND_2") (pintype "passive"))
    )
    (net (code "196") (name "/VNEG_11") (class "Default")
      (node (ref "C205") (pin "2") (pinfunction "2_2") (pintype "passive"))
      (node (ref "C207") (pin "1") (pinfunction "1_1") (pintype "passive"))
      (node (ref "U40") (pin "1") (pinfunction "OUT_1") (pintype "output"))
      (node (ref "U41") (pin "4") (pinfunction "VSS_4") (pintype "power_in"))
      (node (ref "U42") (pin "2") (pinfunction "GND_2") (pintype "passive"))
    )
    (net (code "197") (name "/VNEG_12") (class "Default")
      (node (ref "C213") (pin "2") (pinfunction "2_2") (pintype "passive"))
      (node (ref "C215") (pin "1") (pinfunction "1_1") (pintype "passive"))
      (node (ref "U43") (pin "1") (pinfunction "OUT_1") (pintype "output"))
      (node (ref "U44") (pin "4") (pinfunction "VSS_4") (pintype "power_in"))
      (node (ref "U45") (pin "2") (pinfunction "GND_2") (pintype "passive"))
    )
    (net (code "198") (name "/VNEG_13") (class "Default")
      (node (ref "C189") (pin "2") (pinfunction "2_2") (pintype "passive"))
      (node (ref "C191") (pin "1") (pinfunction "1_1") (pintype "passive"))
      (node (ref "U34") (pin "1") (pinfunction "OUT_1") (pintype "output"))
      (node (ref "U35") (pin "4") (pinfunction "VSS_4") (pintype "power_in"))
      (node (ref "U36") (pin "2") (pinfunction "GND_2") (pintype "passive"))
    )
    (net (code "199") (name "/VNEG_14") (class "Default")
      (node (ref "C197") (pin "2") (pinfunction "2_2") (pintype "passive"))
      (node (ref "C199") (pin "1") (pinfunction "1_1") (pintype "passive"))
      (node (ref "U37") (pin "1") (pinfunction "OUT_1") (pintype "output"))
      (node (ref "U38") (pin "4") (pinfunction "VSS_4") (pintype "power_in"))
      (node (ref "U39") (pin "2") (pinfunction "GND_2") (pintype "passive"))
    )
    (net (code "200") (name "/VNEG_15") (class "Default")
      (node (ref "C221") (pin "2") (pinfunction "2_2") (pintype "passive"))
      (node (ref "C223") (pin "1") (pinfunction "1_1") (pintype "passive"))
      (node (ref "U46") (pin "1") (pinfunction "OUT_1") (pintype "output"))
      (node (ref "U47") (pin "4") (pinfunction "VSS_4") (pintype "power_in"))
      (node (ref "U48") (pin "2") (pinfunction "GND_2") (pintype "passive"))
    )
    (net (code "201") (name "/VNEG_16") (class "Default")
      (node (ref "C229") (pin "2") (pinfunction "2_2") (pintype "passive"))
      (node (ref "C231") (pin "1") (pinfunction "1_1") (pintype "passive"))
      (node (ref "U49") (pin "1") (pinfunction "OUT_1") (pintype "output"))
      (node (ref "U50") (pin "4") (pinfunction "VSS_4") (pintype "power_in"))
      (node (ref "U51") (pin "2") (pinfunction "GND_2") (pintype "passive"))
    )
    (net (code "202") (name "GND") (class "Default")
      (node (ref "C1") (pin "2") (pinfunction "2_2") (pintype "passive"))
      (node (ref "C101") (pin "2") (pinfunction "2_2") (pintype "passive"))
      (node (ref "C102") (pin "2") (pinfunction "2_2") (pintype "passive"))
      (node (ref "C104") (pin "2") (pinfunction "2_2") (pintype "passive"))
      (node (ref "C106") (pin "2") (pinfunction "2_2") (pintype "passive"))
      (node (ref "C107") (pin "2") (pinfunction "2_2") (pintype "passive"))
      (node (ref "C11") (pin "2") (pinfunction "2_2") (pintype "passive"))
      (node (ref "C113") (pin "1") (pinfunction "1_1") (pintype "passive"))
      (node (ref "C114") (pin "1") (pinfunction "1_1") (pintype "passive"))
      (node (ref "C116") (pin "1") (pinfunction "1_1") (pintype "passive"))
      (node (ref "C117") (pin "1") (pinfunction "1_1") (pintype "passive"))
      (node (ref "C118") (pin "2") (pinfunction "2_2") (pintype "passive"))
      (node (ref "C119") (pin "2") (pinfunction "2_2") (pintype "passive"))
      (node (ref "C12") (pin "2") (pinfunction "2_2") (pintype "passive"))
      (node (ref "C120") (pin "2") (pinfunction "2_2") (pintype "passive"))
      (node (ref "C121") (pin "1") (pinfunction "1_1") (pintype "passive"))
      (node (ref "C122") (pin "1") (pinfunction "1_1") (pintype "passive"))
      (node (ref "C124") (pin "1") (pinfunction "1_1") (pintype "passive"))
      (node (ref "C125") (pin "1") (pinfunction "1_1") (pintype "passive"))
      (node (ref "C126") (pin "2") (pinfunction "2_2") (pintype "passive"))
      (node (ref "C127") (pin "2") (pinfunction "2_2") (pintype "passive"))
      (node (ref "C128") (pin "2") (pinfunction "2_2") (pintype "passive"))
      (node (ref "C129") (pin "1") (pinfunction "1_1") (pintype "passive"))
      (node (ref "C13") (pin "2") (pinfunction "2_2") (pintype "passive"))
      (node (ref "C130") (pin "1") (pinfunction "1_1") (pintype "passive"))
      (node (ref "C132") (pin "1") (pinfunction "1_1") (pintype "passive"))
      (node (ref "C133") (pin "1") (pinfunction "1_1") (pintype "passive"))
      (node (ref "C134") (pin "2") (pinfunction "2_2") (pintype "passive"))
      (node (ref "C135") (pin "2") (pinfunction "2_2") (pintype "passive"))
      (node (ref "C136") (pin "2") (pinfunction "2_2") (pintype "passive"))
      (node (ref "C137") (pin "1") (pinfunction "1_1") (pintype "passive"))
      (node (ref "C138") (pin "1") (pinfunction "1_1") (pintype "passive"))
      (node (ref "C14") (pin "2") (pinfunction "2_2") (pintype "passive"))
      (node (ref "C140") (pin "1") (pinfunction "1_1") (pintype "passive"))
      (node (ref "C141") (pin "1") (pinfunction "1_1") (pintype "passive"))
      (node (ref "C142") (pin "2") (pinfunction "2_2") (pintype "passive"))
      (node (ref "C143") (pin "2") (pinfunction "2_2") (pintype "passive"))
      (node (ref "C144") (pin "2") (pinfunction "2_2") (pintype "passive"))
      (node (ref "C145") (pin "1") (pinfunction "1_1") (pintype "passive"))
      (node (ref "C146") (pin "1") (pinfunction "1_1") (pintype "passive"))
      (node (ref "C148") (pin "1") (pinfunction "1_1") (pintype "passive"))
      (node (ref "C149") (pin "1") (pinfunction "1_1") (pintype "passive"))
      (node (ref "C15") (pin "2") (pinfunction "2_2") (pintype "passive"))
      (node (ref "C150") (pin "2") (pinfunction "2_2") (pintype "passive"))
      (node (ref "C151") (pin "2") (pinfunction "2_2") (pintype "passive"))
      (node (ref "C152") (pin "2") (pinfunction "2_2") (pintype "passive"))
      (node (ref "C153") (pin "1") (pinfunction "1_1") (pintype "passive"))
      (node (ref "C154") (pin "1") (pinfunction "1_1") (pintype "passive"))
      (node (ref "C156") (pin "1") (pinfunction "1_1") (pintype "passive"))
      (node (ref "C157") (pin "1") (pinfunction "1_1") (pintype "passive"))
      (node (ref "C158") (pin "2") (pinfunction "2_2") (pintype "passive"))
      (node (ref "C159") (pin "2") (pinfunction "2_2") (pintype "passive"))
      (node (ref "C160") (pin "2") (pinfunction "2_2") (pintype "passive"))
      (node (ref "C161") (pin "1") (pinfunction "1_1") (pintype "passive"))
      (node (ref "C162") (pin "1") (pinfunction "1_1") (pintype "passive"))
      (node (ref "C164") (pin "1") (pinfunction "1_1") (pintype "passive"))
      (node (ref "C165") (pin "1") (pinfunction "1_1") (pintype "passive"))
      (node (ref "C166") (pin "2") (pinfunction "2_2") (pintype "passive"))
      (node (ref "C167") (pin "2") (pinfunction "2_2") (pintype "passive"))
      (node (ref "C168") (pin "2") (pinfunction "2_2") (pintype "passive"))
      (node (ref "C169") (pin "1") (pinfunction "1_1") (pintype "passive"))
      (node (ref "C17") (pin "2") (pinfunction "2_2") (pintype "passive"))
      (node (ref "C170") (pin "1") (pinfunction "1_1") (pintype "passive"))
      (node (ref "C172") (pin "1") (pinfunction "1_1") (pintype "passive"))
      (node (ref "C173") (pin "1") (pinfunction "1_1") (pintype "passive"))
      (node (ref "C174") (pin "2") (pinfunction "2_2") (pintype "passive"))
      (node (ref "C175") (pin "2") (pinfunction "2_2") (pintype "passive"))
      (node (ref "C176") (pin "2") (pinfunction "2_2") (pintype "passive"))
      (node (ref "C177") (pin "1") (pinfunction "1_1") (pintype "passive"))
      (node (ref "C178") (pin "1") (pinfunction "1_1") (pintype "passive"))
      (node (ref "C18") (pin "2") (pinfunction "2_2") (pintype "passive"))
      (node (ref "C180") (pin "1") (pinfunction "1_1") (pintype "passive"))
      (node (ref "C181") (pin "1") (pinfunction "1_1") (pintype "passive"))
      (node (ref "C182") (pin "2") (pinfunction "2_2") (pintype "passive"))
      (node (ref "C183") (pin "2") (pinfunction "2_2") (pintype "passive"))
      (node (ref "C184") (pin "2") (pinfunction "2_2") (pintype "passive"))
      (node (ref "C185") (pin "1") (pinfunction "1_1") (pintype "passive"))
      (node (ref "C186") (pin "1") (pinfunction "1_1") (pintype "passive"))
      (node (ref "C188") (pin "1") (pinfunction "1_1") (pintype "passive"))
      (node (ref "C189") (pin "1") (pinfunction "1_1") (pintype "passive"))
      (node (ref "C19") (pin "2") (pinfunction "2_2") (pintype "passive"))
      (node (ref "C190") (pin "2") (pinfunction "2_2") (pintype "passive"))
      (node (ref "C191") (pin "2") (pinfunction "2_2") (pintype "passive"))
      (node (ref "C192") (pin "2") (pinfunction "2_2") (pintype "passive"))
      (node (ref "C193") (pin "1") (pinfunction "1_1") (pintype "passive"))
      (node (ref "C194") (pin "1") (pinfunction "1_1") (pintype "passive"))
      (node (ref "C196") (pin "1") (pinfunction "1_1") (pintype "passive"))
      (node (ref "C197") (pin "1") (pinfunction "1_1") (pintype "passive"))
      (node (ref "C198") (pin "2") (pinfunction "2_2") (pintype "passive"))
      (node (ref "C199") (pin "2") (pinfunction "2_2") (pintype "passive"))
      (node (ref "C2") (pin "2") (pinfunction "2_2") (pintype "passive"))
      (node (ref "C20") (pin "2") (pinfunction "2_2") (pintype "passive"))
      (node (ref "C200") (pin "2") (pinfunction "2_2") (pintype "passive"))
      (node (ref "C201") (pin "1") (pinfunction "1_1") (pintype "passive"))
      (node (ref "C202") (pin "1") (pinfunction "1_1") (pintype "passive"))
      (node (ref "C204") (pin "1") (pinfunction "1_1") (pintype "passive"))
      (node (ref "C205") (pin "1") (pinfunction "1_1") (pintype "passive"))
      (node (ref "C206") (pin "2") (pinfunction "2_2") (pintype "passive"))
      (node (ref "C207") (pin "2") (pinfunction "2_2") (pintype "passive"))
      (node (ref "C208") (pin "2") (pinfunction "2_2") (pintype "passive"))
      (node (ref "C209") (pin "1") (pinfunction "1_1") (pintype "passive"))
      (node (ref "C21") (pin "2") (pinfunction "2_2") (pintype "passive"))
      (node (ref "C210") (pin "1") (pinfunction "1_1") (pintype "passive"))
      (node (ref "C212") (pin "1") (pinfunction "1_1") (pintype "passive"))
      (node (ref "C213") (pin "1") (pinfunction "1_1") (pintype "passive"))
      (node (ref "C214") (pin "2") (pinfunction "2_2") (pintype "passive"))
      (node (ref "C215") (pin "2") (pinfunction "2_2") (pintype "passive"))
      (node (ref "C216") (pin "2") (pinfunction "2_2") (pintype "passive"))
      (node (ref "C217") (pin "1") (pinfunction "1_1") (pintype "passive"))
      (node (ref "C218") (pin "1") (pinfunction "1_1") (pintype "passive"))
      (node (ref "C220") (pin "1") (pinfunction "1_1") (pintype "passive"))
      (node (ref "C221") (pin "1") (pinfunction "1_1") (pintype "passive"))
      (node (ref "C222") (pin "2") (pinfunction "2_2") (pintype "passive"))
      (node (ref "C223") (pin "2") (pinfunction "2_2") (pintype "passive"))
      (node (ref "C224") (pin "2") (pinfunction "2_2") (pintype "passive"))
      (node (ref "C225") (pin "1") (pinfunction "1_1") (pintype "passive"))
      (node (ref "C226") (pin "1") (pinfunction "1_1") (pintype "passive"))
      (node (ref "C228") (pin "1") (pinfunction "1_1") (pintype "passive"))
      (node (ref "C229") (pin "1") (pinfunction "1_1") (pintype "passive"))
      (node (ref "C23") (pin "2") (pinfunction "2_2") (pintype "passive"))
      (node (ref "C230") (pin "2") (pinfunction "2_2") (pintype "passive"))
      (node (ref "C231") (pin "2") (pinfunction "2_2") (pintype "passive"))
      (node (ref "C232") (pin "2") (pinfunction "2_2") (pintype "passive"))
      (node (ref "C24") (pin "2") (pinfunction "2_2") (pintype "passive"))
      (node (ref "C25") (pin "2") (pinfunction "2_2") (pintype "passive"))
      (node (ref "C26") (pin "2") (pinfunction "2_2") (pintype "passive"))
      (node (ref "C27") (pin "2") (pinfunction "2_2") (pintype "passive"))
      (node (ref "C29") (pin "2") (pinfunction "2_2") (pintype "passive"))
      (node (ref "C3") (pin "2") (pinfunction "2_2") (pintype "passive"))
      (node (ref "C30") (pin "2") (pinfunction "2_2") (pintype "passive"))
      (node (ref "C31") (pin "2") (pinfunction "2_2") (pintype "passive"))
      (node (ref "C32") (pin "2") (pinfunction "2_2") (pintype "passive"))
      (node (ref "C33") (pin "2") (pinfunction "2_2") (pintype "passive"))
      (node (ref "C35") (pin "2") (pinfunction "2_2") (pintype "passive"))
      (node (ref "C36") (pin "2") (pinfunction "2_2") (pintype "passive"))
      (node (ref "C37") (pin "2") (pinfunction "2_2") (pintype "passive"))
      (node (ref "C38") (pin "2") (pinfunction "2_2") (pintype "passive"))
      (node (ref "C39") (pin "2") (pinfunction "2_2") (pintype "passive"))
      (node (ref "C4") (pin "2") (pinfunction "2_2") (pintype "passive"))
      (node (ref "C41") (pin "2") (pinfunction "2_2") (pintype "passive"))
      (node (ref "C42") (pin "2") (pinfunction "2_2") (pintype "passive"))
      (node (ref "C43") (pin "2") (pinfunction "2_2") (pintype "passive"))
      (node (ref "C44") (pin "2") (pinfunction "2_2") (pintype "passive"))
      (node (ref "C45") (pin "2") (pinfunction "2_2") (pintype "passive"))
      (node (ref "C47") (pin "2") (pinfunction "2_2") (pintype "passive"))
      (node (ref "C48") (pin "2") (pinfunction "2_2") (pintype "passive"))
      (node (ref "C49") (pin "2") (pinfunction "2_2") (pintype "passive"))
      (node (ref "C50") (pin "2") (pinfunction "2_2") (pintype "passive"))
      (node (ref "C51") (pin "2") (pinfunction "2_2") (pintype "passive"))
      (node (ref "C53") (pin "2") (pinfunction "2_2") (pintype "passive"))
      (node (ref "C54") (pin "2") (pinfunction "2_2") (pintype "passive"))
      (node (ref "C55") (pin "2") (pinfunction "2_2") (pintype "passive"))
      (node (ref "C56") (pin "2") (pinfunction "2_2") (pintype "passive"))
      (node (ref "C57") (pin "2") (pinfunction "2_2") (pintype "passive"))
      (node (ref "C59") (pin "2") (pinfunction "2_2") (pintype "passive"))
      (node (ref "C6") (pin "2") (pinfunction "2_2") (pintype "passive"))
      (node (ref "C60") (pin "2") (pinfunction "2_2") (pintype "passive"))
      (node (ref "C61") (pin "2") (pinfunction "2_2") (pintype "passive"))
      (node (ref "C62") (pin "2") (pinfunction "2_2") (pintype "passive"))
      (node (ref "C63") (pin "2") (pinfunction "2_2") (pintype "passive"))
      (node (ref "C65") (pin "2") (pinfunction "2_2") (pintype "passive"))
      (node (ref "C66") (pin "2") (pinfunction "2_2") (pintype "passive"))
      (node (ref "C67") (pin "2") (pinfunction "2_2") (pintype "passive"))
      (node (ref "C68") (pin "2") (pinfunction "2_2") (pintype "passive"))
      (node (ref "C69") (pin "2") (pinfunction "2_2") (pintype "passive"))
      (node (ref "C7") (pin "2") (pinfunction "2_2") (pintype "passive"))
      (node (ref "C71") (pin "2") (pinfunction "2_2") (pintype "passive"))
      (node (ref "C72") (pin "2") (pinfunction "2_2") (pintype "passive"))
      (node (ref "C73") (pin "2") (pinfunction "2_2") (pintype "passive"))
      (node (ref "C74") (pin "2") (pinfunction "2_2") (pintype "passive"))
      (node (ref "C75") (pin "2") (pinfunction "2_2") (pintype "passive"))
      (node (ref "C77") (pin "2") (pinfunction "2_2") (pintype "passive"))
      (node (ref "C78") (pin "2") (pinfunction "2_2") (pintype "passive"))
      (node (ref "C79") (pin "2") (pinfunction "2_2") (pintype "passive"))
      (node (ref "C8") (pin "2") (pinfunction "2_2") (pintype "passive"))
      (node (ref "C80") (pin "2") (pinfunction "2_2") (pintype "passive"))
      (node (ref "C81") (pin "2") (pinfunction "2_2") (pintype "passive"))
      (node (ref "C83") (pin "2") (pinfunction "2_2") (pintype "passive"))
      (node (ref "C84") (pin "2") (pinfunction "2_2") (pintype "passive"))
      (node (ref "C86") (pin "1") (pinfunction "1_1") (pintype "passive"))
      (node (ref "C87") (pin "1") (pinfunction "1_1") (pintype "passive"))
      (node (ref "C89") (pin "1") (pinfunction "1_1") (pintype "passive"))
      (node (ref "C9") (pin "2") (pinfunction "2_2") (pintype "passive"))
      (node (ref "C90") (pin "1") (pinfunction "1_1") (pintype "passive"))
      (node (ref "C91") (pin "2") (pinfunction "2_2") (pintype "passive"))
      (node (ref "C92") (pin "2") (pinfunction "2_2") (pintype "passive"))
      (node (ref "C93") (pin "2") (pinfunction "2_2") (pintype "passive"))
      (node (ref "C95") (pin "2") (pinfunction "2_2") (pintype "passive"))
      (node (ref "C96") (pin "2") (pinfunction "2_2") (pintype "passive"))
      (node (ref "C97") (pin "2") (pinfunction "2_2") (pintype "passive"))
      (node (ref "C98") (pin "2") (pinfunction "2_2") (pintype "passive"))
      (node (ref "C99") (pin "2") (pinfunction "2_2") (pintype "passive"))
      (node (ref "IC1") (pin "18") (pinfunction "AGND_18") (pintype "power_in"))
      (node (ref "IC1") (pin "7") (pinfunction "DGND_7") (pintype "power_in"))
      (node (ref "IC10") (pin "18") (pinfunction "AGND_18") (pintype "power_in"))
      (node (ref "IC10") (pin "7") (pinfunction "DGND_7") (pintype "power_in"))
      (node (ref "IC11") (pin "18") (pinfunction "AGND_18") (pintype "power_in"))
      (node (ref "IC11") (pin "7") (pinfunction "DGND_7") (pintype "power_in"))
      (node (ref "IC12") (pin "18") (pinfunction "AGND_18") (pintype "power_in"))
      (node (ref "IC12") (pin "7") (pinfunction "DGND_7") (pintype "power_in"))
      (node (ref "IC13") (pin "18") (pinfunction "AGND_18") (pintype "power_in"))
      (node (ref "IC13") (pin "7") (pinfunction "DGND_7") (pintype "power_in"))
      (node (ref "IC14") (pin "18") (pinfunction "AGND_18") (pintype "power_in"))
      (node (ref "IC14") (pin "7") (pinfunction "DGND_7") (pintype "power_in"))
      (node (ref "IC16") (pin "18") (pinfunction "AGND_18") (pintype "power_in"))
      (node (ref "IC16") (pin "7") (pinfunction "DGND_7") (pintype "power_in"))
      (node (ref "IC17") (pin "18") (pinfunction "AGND_18") (pintype "power_in"))
      (node (ref "IC17") (pin "7") (pinfunction "DGND_7") (pintype "power_in"))
      (node (ref "IC2") (pin "18") (pinfunction "AGND_18") (pintype "power_in"))
      (node (ref "IC2") (pin "7") (pinfunction "DGND_7") (pintype "power_in"))
      (node (ref "IC3") (pin "18") (pinfunction "AGND_18") (pintype "power_in"))
      (node (ref "IC3") (pin "7") (pinfunction "DGND_7") (pintype "power_in"))
      (node (ref "IC4") (pin "18") (pinfunction "AGND_18") (pintype "power_in"))
      (node (ref "IC4") (pin "7") (pinfunction "DGND_7") (pintype "power_in"))
      (node (ref "IC5") (pin "18") (pinfunction "AGND_18") (pintype "power_in"))
      (node (ref "IC5") (pin "7") (pinfunction "DGND_7") (pintype "power_in"))
      (node (ref "IC6") (pin "18") (pinfunction "AGND_18") (pintype "power_in"))
      (node (ref "IC6") (pin "7") (pinfunction "DGND_7") (pintype "power_in"))
      (node (ref "IC7") (pin "18") (pinfunction "AGND_18") (pintype "power_in"))
      (node (ref "IC7") (pin "7") (pinfunction "DGND_7") (pintype "power_in"))
      (node (ref "IC8") (pin "18") (pinfunction "AGND_18") (pintype "power_in"))
      (node (ref "IC8") (pin "7") (pinfunction "DGND_7") (pintype "power_in"))
      (node (ref "IC9") (pin "18") (pinfunction "AGND_18") (pintype "power_in"))
      (node (ref "IC9") (pin "7") (pinfunction "DGND_7") (pintype "power_in"))
      (node (ref "J2") (pin "2") (pinfunction "2_2") (pintype "passive"))
      (node (ref "J7") (pin "2") (pinfunction "2_2") (pintype "passive"))
      (node (ref "JP1") (pin "2") (pinfunction "2_2") (pintype "passive"))
      (node (ref "JP10") (pin "2") (pinfunction "2_2") (pintype "passive"))
      (node (ref "JP11") (pin "2") (pinfunction "2_2") (pintype "passive"))
      (node (ref "JP12") (pin "2") (pinfunction "2_2") (pintype "passive"))
      (node (ref "JP13") (pin "2") (pinfunction "2_2") (pintype "passive"))
      (node (ref "JP14") (pin "2") (pinfunction "2_2") (pintype "passive"))
      (node (ref "JP15") (pin "2") (pinfunction "2_2") (pintype "passive"))
      (node (ref "JP16") (pin "2") (pinfunction "2_2") (pintype "passive"))
      (node (ref "JP2") (pin "2") (pinfunction "2_2") (pintype "passive"))
      (node (ref "JP3") (pin "2") (pinfunction "2_2") (pintype "passive"))
      (node (ref "JP4") (pin "2") (pinfunction "2_2") (pintype "passive"))
      (node (ref "JP5") (pin "2") (pinfunction "2_2") (pintype "passive"))
      (node (ref "JP6") (pin "2") (pinfunction "2_2") (pintype "passive"))
      (node (ref "JP7") (pin "2") (pinfunction "2_2") (pintype "passive"))
      (node (ref "JP8") (pin "2") (pinfunction "2_2") (pintype "passive"))
      (node (ref "JP9") (pin "2") (pinfunction "2_2") (pintype "passive"))
      (node (ref "LDO") (pin "2") (pinfunction "GND_2") (pintype "bidirectional"))
      (node (ref "LDO10") (pin "2") (pinfunction "GND_2") (pintype "bidirectional"))
      (node (ref "LDO11") (pin "2") (pinfunction "GND_2") (pintype "bidirectional"))
      (node (ref "LDO12") (pin "2") (pinfunction "GND_2") (pintype "bidirectional"))
      (node (ref "LDO13") (pin "2") (pinfunction "GND_2") (pintype "bidirectional"))
      (node (ref "LDO14") (pin "2") (pinfunction "GND_2") (pintype "bidirectional"))
      (node (ref "LDO15") (pin "2") (pinfunction "GND_2") (pintype "bidirectional"))
      (node (ref "LDO16") (pin "2") (pinfunction "GND_2") (pintype "bidirectional"))
      (node (ref "LDO2") (pin "2") (pinfunction "GND_2") (pintype "bidirectional"))
      (node (ref "LDO3") (pin "2") (pinfunction "GND_2") (pintype "bidirectional"))
      (node (ref "LDO4") (pin "2") (pinfunction "GND_2") (pintype "bidirectional"))
      (node (ref "LDO5") (pin "2") (pinfunction "GND_2") (pintype "bidirectional"))
      (node (ref "LDO6") (pin "2") (pinfunction "GND_2") (pintype "bidirectional"))
      (node (ref "LDO7") (pin "2") (pinfunction "GND_2") (pintype "bidirectional"))
      (node (ref "LDO8") (pin "2") (pinfunction "GND_2") (pintype "bidirectional"))
      (node (ref "LDO9") (pin "2") (pinfunction "GND_2") (pintype "bidirectional"))
      (node (ref "LSP1") (pin "MP") (pinfunction "MP_MP") (pintype "passive"))
      (node (ref "LSP10") (pin "MP") (pinfunction "MP_MP") (pintype "passive"))
      (node (ref "LSP11") (pin "MP") (pinfunction "MP_MP") (pintype "passive"))
      (node (ref "LSP12") (pin "MP") (pinfunction "MP_MP") (pintype "passive"))
      (node (ref "LSP13") (pin "MP") (pinfunction "MP_MP") (pintype "passive"))
      (node (ref "LSP14") (pin "MP") (pinfunction "MP_MP") (pintype "passive"))
      (node (ref "LSP15") (pin "MP") (pinfunction "MP_MP") (pintype "passive"))
      (node (ref "LSP16") (pin "MP") (pinfunction "MP_MP") (pintype "passive"))
      (node (ref "LSP17") (pin "MP") (pinfunction "MP_MP") (pintype "passive"))
      (node (ref "LSP18") (pin "MP") (pinfunction "MP_MP") (pintype "passive"))
      (node (ref "LSP19") (pin "MP") (pinfunction "MP_MP") (pintype "passive"))
      (node (ref "LSP2") (pin "MP") (pinfunction "MP_MP") (pintype "passive"))
      (node (ref "LSP20") (pin "MP") (pinfunction "MP_MP") (pintype "passive"))
      (node (ref "LSP3") (pin "MP") (pinfunction "MP_MP") (pintype "passive"))
      (node (ref "LSP4") (pin "MP") (pinfunction "MP_MP") (pintype "passive"))
      (node (ref "LSP5") (pin "MP") (pinfunction "MP_MP") (pintype "passive"))
      (node (ref "LSP6") (pin "MP") (pinfunction "MP_MP") (pintype "passive"))
      (node (ref "LSP7") (pin "MP") (pinfunction "MP_MP") (pintype "passive"))
      (node (ref "LSP8") (pin "MP") (pinfunction "MP_MP") (pintype "passive"))
      (node (ref "LSP9") (pin "MP") (pinfunction "MP_MP") (pintype "passive"))
      (node (ref "R1") (pin "2") (pinfunction "2_2") (pintype "passive"))
      (node (ref "R10") (pin "1") (pinfunction "1_1") (pintype "passive"))
      (node (ref "R11") (pin "1") (pinfunction "1_1") (pintype "passive"))
      (node (ref "R13") (pin "2") (pinfunction "2_2") (pintype "passive"))
      (node (ref "R14") (pin "1") (pinfunction "1_1") (pintype "passive"))
      (node (ref "R15") (pin "1") (pinfunction "1_1") (pintype "passive"))
      (node (ref "R17") (pin "2") (pinfunction "2_2") (pintype "passive"))
      (node (ref "R18") (pin "1") (pinfunction "1_1") (pintype "passive"))
      (node (ref "R19") (pin "1") (pinfunction "1_1") (pintype "passive"))
      (node (ref "R2") (pin "2") (pinfunction "2_2") (pintype "passive"))
      (node (ref "R21") (pin "2") (pinfunction "2_2") (pintype "passive"))
      (node (ref "R22") (pin "1") (pinfunction "1_1") (pintype "passive"))
      (node (ref "R23") (pin "1") (pinfunction "1_1") (pintype "passive"))
      (node (ref "R25") (pin "2") (pinfunction "2_2") (pintype "passive"))
      (node (ref "R26") (pin "1") (pinfunction "1_1") (pintype "passive"))
      (node (ref "R27") (pin "1") (pinfunction "1_1") (pintype "passive"))
      (node (ref "R29") (pin "2") (pinfunction "2_2") (pintype "passive"))
      (node (ref "R30") (pin "1") (pinfunction "1_1") (pintype "passive"))
      (node (ref "R31") (pin "1") (pinfunction "1_1") (pintype "passive"))
      (node (ref "R33") (pin "2") (pinfunction "2_2") (pintype "passive"))
      (node (ref "R34") (pin "1") (pinfunction "1_1") (pintype "passive"))
      (node (ref "R35") (pin "1") (pinfunction "1_1") (pintype "passive"))
      (node (ref "R37") (pin "2") (pinfunction "2_2") (pintype "passive"))
      (node (ref "R38") (pin "1") (pinfunction "1_1") (pintype "passive"))
      (node (ref "R39") (pin "1") (pinfunction "1_1") (pintype "passive"))
      (node (ref "R4") (pin "1") (pinfunction "1_1") (pintype "passive"))
      (node (ref "R41") (pin "2") (pinfunction "2_2") (pintype "passive"))
      (node (ref "R42") (pin "1") (pinfunction "1_1") (pintype "passive"))
      (node (ref "R43") (pin "1") (pinfunction "1_1") (pintype "passive"))
      (node (ref "R45") (pin "2") (pinfunction "2_2") (pintype "passive"))
      (node (ref "R46") (pin "1") (pinfunction "1_1") (pintype "passive"))
      (node (ref "R47") (pin "1") (pinfunction "1_1") (pintype "passive"))
      (node (ref "R49") (pin "2") (pinfunction "2_2") (pintype "passive"))
      (node (ref "R5") (pin "1") (pinfunction "1_1") (pintype "passive"))
      (node (ref "R50") (pin "1") (pinfunction "1_1") (pintype "passive"))
      (node (ref "R51") (pin "1") (pinfunction "1_1") (pintype "passive"))
      (node (ref "R53") (pin "2") (pinfunction "2_2") (pintype "passive"))
      (node (ref "R54") (pin "1") (pinfunction "1_1") (pintype "passive"))
      (node (ref "R55") (pin "1") (pinfunction "1_1") (pintype "passive"))
      (node (ref "R6") (pin "1") (pinfunction "1_1") (pintype "passive"))
      (node (ref "R61") (pin "2") (pinfunction "2_2") (pintype "passive"))
      (node (ref "R62") (pin "1") (pinfunction "1_1") (pintype "passive"))
      (node (ref "R63") (pin "1") (pinfunction "1_1") (pintype "passive"))
      (node (ref "R65") (pin "2") (pinfunction "2_2") (pintype "passive"))
      (node (ref "R66") (pin "1") (pinfunction "1_1") (pintype "passive"))
      (node (ref "R67") (pin "1") (pinfunction "1_1") (pintype "passive"))
      (node (ref "R7") (pin "1") (pinfunction "1_1") (pintype "passive"))
      (node (ref "R9") (pin "2") (pinfunction "2_2") (pintype "passive"))
      (node (ref "SJ10") (pin "2") (pinfunction "2_2") (pintype "passive"))
      (node (ref "SJ100") (pin "2") (pinfunction "2_2") (pintype "passive"))
      (node (ref "SJ15") (pin "1") (pinfunction "1_1") (pintype "passive"))
      (node (ref "SJ16") (pin "2") (pinfunction "2_2") (pintype "passive"))
      (node (ref "SJ21") (pin "1") (pinfunction "1_1") (pintype "passive"))
      (node (ref "SJ22") (pin "2") (pinfunction "2_2") (pintype "passive"))
      (node (ref "SJ27") (pin "1") (pinfunction "1_1") (pintype "passive"))
      (node (ref "SJ28") (pin "2") (pinfunction "2_2") (pintype "passive"))
      (node (ref "SJ3") (pin "1") (pinfunction "1_1") (pintype "passive"))
      (node (ref "SJ33") (pin "1") (pinfunction "1_1") (pintype "passive"))
      (node (ref "SJ34") (pin "2") (pinfunction "2_2") (pintype "passive"))
      (node (ref "SJ39") (pin "1") (pinfunction "1_1") (pintype "passive"))
      (node (ref "SJ40") (pin "2") (pinfunction "2_2") (pintype "passive"))
      (node (ref "SJ45") (pin "1") (pinfunction "1_1") (pintype "passive"))
      (node (ref "SJ46") (pin "2") (pinfunction "2_2") (pintype "passive"))
      (node (ref "SJ51") (pin "1") (pinfunction "1_1") (pintype "passive"))
      (node (ref "SJ52") (pin "2") (pinfunction "2_2") (pintype "passive"))
      (node (ref "SJ57") (pin "1") (pinfunction "1_1") (pintype "passive"))
      (node (ref "SJ58") (pin "2") (pinfunction "2_2") (pintype "passive"))
      (node (ref "SJ63") (pin "1") (pinfunction "1_1") (pintype "passive"))
      (node (ref "SJ64") (pin "2") (pinfunction "2_2") (pintype "passive"))
      (node (ref "SJ69") (pin "1") (pinfunction "1_1") (pintype "passive"))
      (node (ref "SJ7") (pin "2") (pinfunction "2_2") (pintype "passive"))
      (node (ref "SJ70") (pin "2") (pinfunction "2_2") (pintype "passive"))
      (node (ref "SJ75") (pin "1") (pinfunction "1_1") (pintype "passive"))
      (node (ref "SJ76") (pin "2") (pinfunction "2_2") (pintype "passive"))
      (node (ref "SJ81") (pin "1") (pinfunction "1_1") (pintype "passive"))
      (node (ref "SJ82") (pin "2") (pinfunction "2_2") (pintype "passive"))
      (node (ref "SJ9") (pin "1") (pinfunction "1_1") (pintype "passive"))
      (node (ref "SJ93") (pin "1") (pinfunction "1_1") (pintype "passive"))
      (node (ref "SJ94") (pin "2") (pinfunction "2_2") (pintype "passive"))
      (node (ref "SJ99") (pin "1") (pinfunction "1_1") (pintype "passive"))
      (node (ref "U1") (pin "4") (pinfunction "GND_4") (pintype "passive"))
      (node (ref "U10") (pin "4") (pinfunction "GND_4") (pintype "passive"))
      (node (ref "U11") (pin "6") (pinfunction "GND_6") (pintype "passive"))
      (node (ref "U12") (pin "3") (pinfunction "IN+_3") (pintype "input"))
      (node (ref "U13") (pin "4") (pinfunction "GND_4") (pintype "passive"))
      (node (ref "U14") (pin "6") (pinfunction "GND_6") (pintype "passive"))
      (node (ref "U15") (pin "3") (pinfunction "IN+_3") (pintype "input"))
      (node (ref "U16") (pin "4") (pinfunction "GND_4") (pintype "passive"))
      (node (ref "U17") (pin "6") (pinfunction "GND_6") (pintype "passive"))
      (node (ref "U18") (pin "3") (pinfunction "IN+_3") (pintype "input"))
      (node (ref "U19") (pin "4") (pinfunction "GND_4") (pintype "passive"))
      (node (ref "U2") (pin "3") (pinfunction "IN+_3") (pintype "input"))
      (node (ref "U20") (pin "6") (pinfunction "GND_6") (pintype "passive"))
      (node (ref "U21") (pin "3") (pinfunction "IN+_3") (pintype "input"))
      (node (ref "U22") (pin "4") (pinfunction "GND_4") (pintype "passive"))
      (node (ref "U23") (pin "6") (pinfunction "GND_6") (pintype "passive"))
      (node (ref "U24") (pin "3") (pinfunction "IN+_3") (pintype "input"))
      (node (ref "U25") (pin "4") (pinfunction "GND_4") (pintype "passive"))
      (node (ref "U26") (pin "6") (pinfunction "GND_6") (pintype "passive"))
      (node (ref "U27") (pin "3") (pinfunction "IN+_3") (pintype "input"))
      (node (ref "U28") (pin "4") (pinfunction "GND_4") (pintype "passive"))
      (node (ref "U29") (pin "6") (pinfunction "GND_6") (pintype "passive"))
      (node (ref "U3") (pin "6") (pinfunction "GND_6") (pintype "passive"))
      (node (ref "U30") (pin "3") (pinfunction "IN+_3") (pintype "input"))
      (node (ref "U31") (pin "4") (pinfunction "GND_4") (pintype "passive"))
      (node (ref "U32") (pin "6") (pinfunction "GND_6") (pintype "passive"))
      (node (ref "U33") (pin "3") (pinfunction "IN+_3") (pintype "input"))
      (node (ref "U34") (pin "4") (pinfunction "GND_4") (pintype "passive"))
      (node (ref "U35") (pin "6") (pinfunction "GND_6") (pintype "passive"))
      (node (ref "U36") (pin "3") (pinfunction "IN+_3") (pintype "input"))
      (node (ref "U37") (pin "4") (pinfunction "GND_4") (pintype "passive"))
      (node (ref "U38") (pin "6") (pinfunction "GND_6") (pintype "passive"))
      (node (ref "U39") (pin "3") (pinfunction "IN+_3") (pintype "input"))
      (node (ref "U40") (pin "4") (pinfunction "GND_4") (pintype "passive"))
      (node (ref "U41") (pin "6") (pinfunction "GND_6") (pintype "passive"))
      (node (ref "U42") (pin "3") (pinfunction "IN+_3") (pintype "input"))
      (node (ref "U43") (pin "4") (pinfunction "GND_4") (pintype "passive"))
      (node (ref "U44") (pin "6") (pinfunction "GND_6") (pintype "passive"))
      (node (ref "U45") (pin "3") (pinfunction "IN+_3") (pintype "input"))
      (node (ref "U46") (pin "4") (pinfunction "GND_4") (pintype "passive"))
      (node (ref "U47") (pin "6") (pinfunction "GND_6") (pintype "passive"))
      (node (ref "U48") (pin "3") (pinfunction "IN+_3") (pintype "input"))
      (node (ref "U49") (pin "4") (pinfunction "GND_4") (pintype "passive"))
      (node (ref "U50") (pin "6") (pinfunction "GND_6") (pintype "passive"))
      (node (ref "U51") (pin "3") (pinfunction "IN+_3") (pintype "input"))
      (node (ref "U7") (pin "4") (pinfunction "GND_4") (pintype "passive"))
      (node (ref "U8") (pin "6") (pinfunction "GND_6") (pintype "passive"))
      (node (ref "U9") (pin "3") (pinfunction "IN+_3") (pintype "input"))
    )
    (net (code "203") (name "Net-(IC1-CAP{slash}2,5V)") (class "Default")
      (node (ref "C3") (pin "1") (pinfunction "1_1") (pintype "passive"))
      (node (ref "IC1") (pin "6") (pinfunction "CAP/2,5V_6") (pintype "bidirectional"))
    )
    (net (code "204") (name "Net-(IC1-COMP)") (class "Default")
      (node (ref "C5") (pin "1") (pinfunction "1_1") (pintype "passive"))
      (node (ref "IC1") (pin "3") (pinfunction "COMP_3") (pintype "bidirectional"))
    )
    (net (code "205") (name "Net-(IC1-FS_ADJUST)") (class "Default")
      (node (ref "IC1") (pin "1") (pinfunction "FS_ADJUST_1") (pintype "bidirectional"))
      (node (ref "R1") (pin "1") (pinfunction "1_1") (pintype "passive"))
    )
    (net (code "206") (name "Net-(IC1-REFOUT)") (class "Default")
      (node (ref "C4") (pin "1") (pinfunction "1_1") (pintype "passive"))
      (node (ref "IC1") (pin "2") (pinfunction "REFOUT_2") (pintype "bidirectional"))
    )
    (net (code "207") (name "Net-(IC1-VIN)") (class "Default")
      (node (ref "IC1") (pin "17") (pinfunction "VIN_17") (pintype "bidirectional"))
      (node (ref "SJ3") (pin "2") (pinfunction "2_2") (pintype "passive"))
      (node (ref "SJ5") (pin "1") (pinfunction "1_1") (pintype "passive"))
    )
    (net (code "208") (name "Net-(IC2-CAP{slash}2,5V)") (class "Default")
      (node (ref "C8") (pin "1") (pinfunction "1_1") (pintype "passive"))
      (node (ref "IC2") (pin "6") (pinfunction "CAP/2,5V_6") (pintype "bidirectional"))
    )
    (net (code "209") (name "Net-(IC2-COMP)") (class "Default")
      (node (ref "C10") (pin "1") (pinfunction "1_1") (pintype "passive"))
      (node (ref "IC2") (pin "3") (pinfunction "COMP_3") (pintype "bidirectional"))
    )
    (net (code "210") (name "Net-(IC2-FS_ADJUST)") (class "Default")
      (node (ref "IC2") (pin "1") (pinfunction "FS_ADJUST_1") (pintype "bidirectional"))
      (node (ref "R2") (pin "1") (pinfunction "1_1") (pintype "passive"))
    )
    (net (code "211") (name "Net-(IC2-REFOUT)") (class "Default")
      (node (ref "C9") (pin "1") (pinfunction "1_1") (pintype "passive"))
      (node (ref "IC2") (pin "2") (pinfunction "REFOUT_2") (pintype "bidirectional"))
    )
    (net (code "212") (name "Net-(IC2-VIN)") (class "Default")
      (node (ref "IC2") (pin "17") (pinfunction "VIN_17") (pintype "bidirectional"))
      (node (ref "SJ12") (pin "1") (pinfunction "1_1") (pintype "passive"))
      (node (ref "SJ9") (pin "2") (pinfunction "2_2") (pintype "passive"))
    )
    (net (code "213") (name "Net-(IC3-CAP{slash}2,5V)") (class "Default")
      (node (ref "C14") (pin "1") (pinfunction "1_1") (pintype "passive"))
      (node (ref "IC3") (pin "6") (pinfunction "CAP/2,5V_6") (pintype "bidirectional"))
    )
    (net (code "214") (name "Net-(IC3-COMP)") (class "Default")
      (node (ref "C16") (pin "1") (pinfunction "1_1") (pintype "passive"))
      (node (ref "IC3") (pin "3") (pinfunction "COMP_3") (pintype "bidirectional"))
    )
    (net (code "215") (name "Net-(IC3-FS_ADJUST)") (class "Default")
      (node (ref "IC3") (pin "1") (pinfunction "FS_ADJUST_1") (pintype "bidirectional"))
      (node (ref "R9") (pin "1") (pinfunction "1_1") (pintype "passive"))
    )
    (net (code "216") (name "Net-(IC3-REFOUT)") (class "Default")
      (node (ref "C15") (pin "1") (pinfunction "1_1") (pintype "passive"))
      (node (ref "IC3") (pin "2") (pinfunction "REFOUT_2") (pintype "bidirectional"))
    )
    (net (code "217") (name "Net-(IC3-VIN)") (class "Default")
      (node (ref "IC3") (pin "17") (pinfunction "VIN_17") (pintype "bidirectional"))
      (node (ref "SJ15") (pin "2") (pinfunction "2_2") (pintype "passive"))
      (node (ref "SJ18") (pin "1") (pinfunction "1_1") (pintype "passive"))
    )
    (net (code "218") (name "Net-(IC4-CAP{slash}2,5V)") (class "Default")
      (node (ref "C20") (pin "1") (pinfunction "1_1") (pintype "passive"))
      (node (ref "IC4") (pin "6") (pinfunction "CAP/2,5V_6") (pintype "bidirectional"))
    )
    (net (code "219") (name "Net-(IC4-COMP)") (class "Default")
      (node (ref "C22") (pin "1") (pinfunction "1_1") (pintype "passive"))
      (node (ref "IC4") (pin "3") (pinfunction "COMP_3") (pintype "bidirectional"))
    )
    (net (code "220") (name "Net-(IC4-FS_ADJUST)") (class "Default")
      (node (ref "IC4") (pin "1") (pinfunction "FS_ADJUST_1") (pintype "bidirectional"))
      (node (ref "R13") (pin "1") (pinfunction "1_1") (pintype "passive"))
    )
    (net (code "221") (name "Net-(IC4-REFOUT)") (class "Default")
      (node (ref "C21") (pin "1") (pinfunction "1_1") (pintype "passive"))
      (node (ref "IC4") (pin "2") (pinfunction "REFOUT_2") (pintype "bidirectional"))
    )
    (net (code "222") (name "Net-(IC4-VIN)") (class "Default")
      (node (ref "IC4") (pin "17") (pinfunction "VIN_17") (pintype "bidirectional"))
      (node (ref "SJ21") (pin "2") (pinfunction "2_2") (pintype "passive"))
      (node (ref "SJ24") (pin "1") (pinfunction "1_1") (pintype "passive"))
    )
    (net (code "223") (name "Net-(IC5-CAP{slash}2,5V)") (class "Default")
      (node (ref "C26") (pin "1") (pinfunction "1_1") (pintype "passive"))
      (node (ref "IC5") (pin "6") (pinfunction "CAP/2,5V_6") (pintype "bidirectional"))
    )
    (net (code "224") (name "Net-(IC5-COMP)") (class "Default")
      (node (ref "C28") (pin "1") (pinfunction "1_1") (pintype "passive"))
      (node (ref "IC5") (pin "3") (pinfunction "COMP_3") (pintype "bidirectional"))
    )
    (net (code "225") (name "Net-(IC5-FS_ADJUST)") (class "Default")
      (node (ref "IC5") (pin "1") (pinfunction "FS_ADJUST_1") (pintype "bidirectional"))
      (node (ref "R17") (pin "1") (pinfunction "1_1") (pintype "passive"))
    )
    (net (code "226") (name "Net-(IC5-REFOUT)") (class "Default")
      (node (ref "C27") (pin "1") (pinfunction "1_1") (pintype "passive"))
      (node (ref "IC5") (pin "2") (pinfunction "REFOUT_2") (pintype "bidirectional"))
    )
    (net (code "227") (name "Net-(IC5-VIN)") (class "Default")
      (node (ref "IC5") (pin "17") (pinfunction "VIN_17") (pintype "bidirectional"))
      (node (ref "SJ27") (pin "2") (pinfunction "2_2") (pintype "passive"))
      (node (ref "SJ30") (pin "1") (pinfunction "1_1") (pintype "passive"))
    )
    (net (code "228") (name "Net-(IC6-CAP{slash}2,5V)") (class "Default")
      (node (ref "C32") (pin "1") (pinfunction "1_1") (pintype "passive"))
      (node (ref "IC6") (pin "6") (pinfunction "CAP/2,5V_6") (pintype "bidirectional"))
    )
    (net (code "229") (name "Net-(IC6-COMP)") (class "Default")
      (node (ref "C34") (pin "1") (pinfunction "1_1") (pintype "passive"))
      (node (ref "IC6") (pin "3") (pinfunction "COMP_3") (pintype "bidirectional"))
    )
    (net (code "230") (name "Net-(IC6-FS_ADJUST)") (class "Default")
      (node (ref "IC6") (pin "1") (pinfunction "FS_ADJUST_1") (pintype "bidirectional"))
      (node (ref "R21") (pin "1") (pinfunction "1_1") (pintype "passive"))
    )
    (net (code "231") (name "Net-(IC6-REFOUT)") (class "Default")
      (node (ref "C33") (pin "1") (pinfunction "1_1") (pintype "passive"))
      (node (ref "IC6") (pin "2") (pinfunction "REFOUT_2") (pintype "bidirectional"))
    )
    (net (code "232") (name "Net-(IC6-VIN)") (class "Default")
      (node (ref "IC6") (pin "17") (pinfunction "VIN_17") (pintype "bidirectional"))
      (node (ref "SJ33") (pin "2") (pinfunction "2_2") (pintype "passive"))
      (node (ref "SJ36") (pin "1") (pinfunction "1_1") (pintype "passive"))
    )
    (net (code "233") (name "Net-(IC7-CAP{slash}2,5V)") (class "Default")
      (node (ref "C38") (pin "1") (pinfunction "1_1") (pintype "passive"))
      (node (ref "IC7") (pin "6") (pinfunction "CAP/2,5V_6") (pintype "bidirectional"))
    )
    (net (code "234") (name "Net-(IC7-COMP)") (class "Default")
      (node (ref "C40") (pin "1") (pinfunction "1_1") (pintype "passive"))
      (node (ref "IC7") (pin "3") (pinfunction "COMP_3") (pintype "bidirectional"))
    )
    (net (code "235") (name "Net-(IC7-FS_ADJUST)") (class "Default")
      (node (ref "IC7") (pin "1") (pinfunction "FS_ADJUST_1") (pintype "bidirectional"))
      (node (ref "R25") (pin "1") (pinfunction "1_1") (pintype "passive"))
    )
    (net (code "236") (name "Net-(IC7-REFOUT)") (class "Default")
      (node (ref "C39") (pin "1") (pinfunction "1_1") (pintype "passive"))
      (node (ref "IC7") (pin "2") (pinfunction "REFOUT_2") (pintype "bidirectional"))
    )
    (net (code "237") (name "Net-(IC7-VIN)") (class "Default")
      (node (ref "IC7") (pin "17") (pinfunction "VIN_17") (pintype "bidirectional"))
      (node (ref "SJ39") (pin "2") (pinfunction "2_2") (pintype "passive"))
      (node (ref "SJ42") (pin "1") (pinfunction "1_1") (pintype "passive"))
    )
    (net (code "238") (name "Net-(IC8-CAP{slash}2,5V)") (class "Default")
      (node (ref "C44") (pin "1") (pinfunction "1_1") (pintype "passive"))
      (node (ref "IC8") (pin "6") (pinfunction "CAP/2,5V_6") (pintype "bidirectional"))
    )
    (net (code "239") (name "Net-(IC8-COMP)") (class "Default")
      (node (ref "C46") (pin "1") (pinfunction "1_1") (pintype "passive"))
      (node (ref "IC8") (pin "3") (pinfunction "COMP_3") (pintype "bidirectional"))
    )
    (net (code "240") (name "Net-(IC8-FS_ADJUST)") (class "Default")
      (node (ref "IC8") (pin "1") (pinfunction "FS_ADJUST_1") (pintype "bidirectional"))
      (node (ref "R29") (pin "1") (pinfunction "1_1") (pintype "passive"))
    )
    (net (code "241") (name "Net-(IC8-REFOUT)") (class "Default")
      (node (ref "C45") (pin "1") (pinfunction "1_1") (pintype "passive"))
      (node (ref "IC8") (pin "2") (pinfunction "REFOUT_2") (pintype "bidirectional"))
    )
    (net (code "242") (name "Net-(IC8-VIN)") (class "Default")
      (node (ref "IC8") (pin "17") (pinfunction "VIN_17") (pintype "bidirectional"))
      (node (ref "SJ45") (pin "2") (pinfunction "2_2") (pintype "passive"))
      (node (ref "SJ48") (pin "1") (pinfunction "1_1") (pintype "passive"))
    )
    (net (code "243") (name "Net-(IC9-CAP{slash}2,5V)") (class "Default")
      (node (ref "C50") (pin "1") (pinfunction "1_1") (pintype "passive"))
      (node (ref "IC9") (pin "6") (pinfunction "CAP/2,5V_6") (pintype "bidirectional"))
    )
    (net (code "244") (name "Net-(IC9-COMP)") (class "Default")
      (node (ref "C52") (pin "1") (pinfunction "1_1") (pintype "passive"))
      (node (ref "IC9") (pin "3") (pinfunction "COMP_3") (pintype "bidirectional"))
    )
    (net (code "245") (name "Net-(IC9-FS_ADJUST)") (class "Default")
      (node (ref "IC9") (pin "1") (pinfunction "FS_ADJUST_1") (pintype "bidirectional"))
      (node (ref "R33") (pin "1") (pinfunction "1_1") (pintype "passive"))
    )
    (net (code "246") (name "Net-(IC9-REFOUT)") (class "Default")
      (node (ref "C51") (pin "1") (pinfunction "1_1") (pintype "passive"))
      (node (ref "IC9") (pin "2") (pinfunction "REFOUT_2") (pintype "bidirectional"))
    )
    (net (code "247") (name "Net-(IC9-VIN)") (class "Default")
      (node (ref "IC9") (pin "17") (pinfunction "VIN_17") (pintype "bidirectional"))
      (node (ref "SJ51") (pin "2") (pinfunction "2_2") (pintype "passive"))
      (node (ref "SJ54") (pin "1") (pinfunction "1_1") (pintype "passive"))
    )
    (net (code "248") (name "Net-(IC10-CAP{slash}2,5V)") (class "Default")
      (node (ref "C56") (pin "1") (pinfunction "1_1") (pintype "passive"))
      (node (ref "IC10") (pin "6") (pinfunction "CAP/2,5V_6") (pintype "bidirectional"))
    )
    (net (code "249") (name "Net-(IC10-COMP)") (class "Default")
      (node (ref "C58") (pin "1") (pinfunction "1_1") (pintype "passive"))
      (node (ref "IC10") (pin "3") (pinfunction "COMP_3") (pintype "bidirectional"))
    )
    (net (code "250") (name "Net-(IC10-FS_ADJUST)") (class "Default")
      (node (ref "IC10") (pin "1") (pinfunction "FS_ADJUST_1") (pintype "bidirectional"))
      (node (ref "R37") (pin "1") (pinfunction "1_1") (pintype "passive"))
    )
    (net (code "251") (name "Net-(IC10-REFOUT)") (class "Default")
      (node (ref "C57") (pin "1") (pinfunction "1_1") (pintype "passive"))
      (node (ref "IC10") (pin "2") (pinfunction "REFOUT_2") (pintype "bidirectional"))
    )
    (net (code "252") (name "Net-(IC10-VIN)") (class "Default")
      (node (ref "IC10") (pin "17") (pinfunction "VIN_17") (pintype "bidirectional"))
      (node (ref "SJ57") (pin "2") (pinfunction "2_2") (pintype "passive"))
      (node (ref "SJ60") (pin "1") (pinfunction "1_1") (pintype "passive"))
    )
    (net (code "253") (name "Net-(IC11-CAP{slash}2,5V)") (class "Default")
      (node (ref "C62") (pin "1") (pinfunction "1_1") (pintype "passive"))
      (node (ref "IC11") (pin "6") (pinfunction "CAP/2,5V_6") (pintype "bidirectional"))
    )
    (net (code "254") (name "Net-(IC11-COMP)") (class "Default")
      (node (ref "C64") (pin "1") (pinfunction "1_1") (pintype "passive"))
      (node (ref "IC11") (pin "3") (pinfunction "COMP_3") (pintype "bidirectional"))
    )
    (net (code "255") (name "Net-(IC11-FS_ADJUST)") (class "Default")
      (node (ref "IC11") (pin "1") (pinfunction "FS_ADJUST_1") (pintype "bidirectional"))
      (node (ref "R41") (pin "1") (pinfunction "1_1") (pintype "passive"))
    )
    (net (code "256") (name "Net-(IC11-REFOUT)") (class "Default")
      (node (ref "C63") (pin "1") (pinfunction "1_1") (pintype "passive"))
      (node (ref "IC11") (pin "2") (pinfunction "REFOUT_2") (pintype "bidirectional"))
    )
    (net (code "257") (name "Net-(IC11-VIN)") (class "Default")
      (node (ref "IC11") (pin "17") (pinfunction "VIN_17") (pintype "bidirectional"))
      (node (ref "SJ63") (pin "2") (pinfunction "2_2") (pintype "passive"))
      (node (ref "SJ66") (pin "1") (pinfunction "1_1") (pintype "passive"))
    )
    (net (code "258") (name "Net-(IC12-CAP{slash}2,5V)") (class "Default")
      (node (ref "C68") (pin "1") (pinfunction "1_1") (pintype "passive"))
      (node (ref "IC12") (pin "6") (pinfunction "CAP/2,5V_6") (pintype "bidirectional"))
    )
    (net (code "259") (name "Net-(IC12-COMP)") (class "Default")
      (node (ref "C70") (pin "1") (pinfunction "1_1") (pintype "passive"))
      (node (ref "IC12") (pin "3") (pinfunction "COMP_3") (pintype "bidirectional"))
    )
    (net (code "260") (name "Net-(IC12-FS_ADJUST)") (class "Default")
      (node (ref "IC12") (pin "1") (pinfunction "FS_ADJUST_1") (pintype "bidirectional"))
      (node (ref "R45") (pin "1") (pinfunction "1_1") (pintype "passive"))
    )
    (net (code "261") (name "Net-(IC12-REFOUT)") (class "Default")
      (node (ref "C69") (pin "1") (pinfunction "1_1") (pintype "passive"))
      (node (ref "IC12") (pin "2") (pinfunction "REFOUT_2") (pintype "bidirectional"))
    )
    (net (code "262") (name "Net-(IC12-VIN)") (class "Default")
      (node (ref "IC12") (pin "17") (pinfunction "VIN_17") (pintype "bidirectional"))
      (node (ref "SJ69") (pin "2") (pinfunction "2_2") (pintype "passive"))
      (node (ref "SJ72") (pin "1") (pinfunction "1_1") (pintype "passive"))
    )
    (net (code "263") (name "Net-(IC13-CAP{slash}2,5V)") (class "Default")
      (node (ref "C74") (pin "1") (pinfunction "1_1") (pintype "passive"))
      (node (ref "IC13") (pin "6") (pinfunction "CAP/2,5V_6") (pintype "bidirectional"))
    )
    (net (code "264") (name "Net-(IC13-COMP)") (class "Default")
      (node (ref "C76") (pin "1") (pinfunction "1_1") (pintype "passive"))
      (node (ref "IC13") (pin "3") (pinfunction "COMP_3") (pintype "bidirectional"))
    )
    (net (code "265") (name "Net-(IC13-FS_ADJUST)") (class "Default")
      (node (ref "IC13") (pin "1") (pinfunction "FS_ADJUST_1") (pintype "bidirectional"))
      (node (ref "R49") (pin "1") (pinfunction "1_1") (pintype "passive"))
    )
    (net (code "266") (name "Net-(IC13-REFOUT)") (class "Default")
      (node (ref "C75") (pin "1") (pinfunction "1_1") (pintype "passive"))
      (node (ref "IC13") (pin "2") (pinfunction "REFOUT_2") (pintype "bidirectional"))
    )
    (net (code "267") (name "Net-(IC13-VIN)") (class "Default")
      (node (ref "IC13") (pin "17") (pinfunction "VIN_17") (pintype "bidirectional"))
      (node (ref "SJ75") (pin "2") (pinfunction "2_2") (pintype "passive"))
      (node (ref "SJ78") (pin "1") (pinfunction "1_1") (pintype "passive"))
    )
    (net (code "268") (name "Net-(IC14-CAP{slash}2,5V)") (class "Default")
      (node (ref "C80") (pin "1") (pinfunction "1_1") (pintype "passive"))
      (node (ref "IC14") (pin "6") (pinfunction "CAP/2,5V_6") (pintype "bidirectional"))
    )
    (net (code "269") (name "Net-(IC14-COMP)") (class "Default")
      (node (ref "C82") (pin "1") (pinfunction "1_1") (pintype "passive"))
      (node (ref "IC14") (pin "3") (pinfunction "COMP_3") (pintype "bidirectional"))
    )
    (net (code "270") (name "Net-(IC14-FS_ADJUST)") (class "Default")
      (node (ref "IC14") (pin "1") (pinfunction "FS_ADJUST_1") (pintype "bidirectional"))
      (node (ref "R53") (pin "1") (pinfunction "1_1") (pintype "passive"))
    )
    (net (code "271") (name "Net-(IC14-REFOUT)") (class "Default")
      (node (ref "C81") (pin "1") (pinfunction "1_1") (pintype "passive"))
      (node (ref "IC14") (pin "2") (pinfunction "REFOUT_2") (pintype "bidirectional"))
    )
    (net (code "272") (name "Net-(IC14-VIN)") (class "Default")
      (node (ref "IC14") (pin "17") (pinfunction "VIN_17") (pintype "bidirectional"))
      (node (ref "SJ81") (pin "2") (pinfunction "2_2") (pintype "passive"))
      (node (ref "SJ84") (pin "1") (pinfunction "1_1") (pintype "passive"))
    )
    (net (code "273") (name "Net-(IC16-CAP{slash}2,5V)") (class "Default")
      (node (ref "C92") (pin "1") (pinfunction "1_1") (pintype "passive"))
      (node (ref "IC16") (pin "6") (pinfunction "CAP/2,5V_6") (pintype "bidirectional"))
    )
    (net (code "274") (name "Net-(IC16-COMP)") (class "Default")
      (node (ref "C94") (pin "1") (pinfunction "1_1") (pintype "passive"))
      (node (ref "IC16") (pin "3") (pinfunction "COMP_3") (pintype "bidirectional"))
    )
    (net (code "275") (name "Net-(IC16-FS_ADJUST)") (class "Default")
      (node (ref "IC16") (pin "1") (pinfunction "FS_ADJUST_1") (pintype "bidirectional"))
      (node (ref "R61") (pin "1") (pinfunction "1_1") (pintype "passive"))
    )
    (net (code "276") (name "Net-(IC16-REFOUT)") (class "Default")
      (node (ref "C93") (pin "1") (pinfunction "1_1") (pintype "passive"))
      (node (ref "IC16") (pin "2") (pinfunction "REFOUT_2") (pintype "bidirectional"))
    )
    (net (code "277") (name "Net-(IC16-VIN)") (class "Default")
      (node (ref "IC16") (pin "17") (pinfunction "VIN_17") (pintype "bidirectional"))
      (node (ref "SJ93") (pin "2") (pinfunction "2_2") (pintype "passive"))
      (node (ref "SJ96") (pin "1") (pinfunction "1_1") (pintype "passive"))
    )
    (net (code "278") (name "Net-(IC17-CAP{slash}2,5V)") (class "Default")
      (node (ref "C98") (pin "1") (pinfunction "1_1") (pintype "passive"))
      (node (ref "IC17") (pin "6") (pinfunction "CAP/2,5V_6") (pintype "bidirectional"))
    )
    (net (code "279") (name "Net-(IC17-COMP)") (class "Default")
      (node (ref "C100") (pin "1") (pinfunction "1_1") (pintype "passive"))
      (node (ref "IC17") (pin "3") (pinfunction "COMP_3") (pintype "bidirectional"))
    )
    (net (code "280") (name "Net-(IC17-FS_ADJUST)") (class "Default")
      (node (ref "IC17") (pin "1") (pinfunction "FS_ADJUST_1") (pintype "bidirectional"))
      (node (ref "R65") (pin "1") (pinfunction "1_1") (pintype "passive"))
    )
    (net (code "281") (name "Net-(IC17-REFOUT)") (class "Default")
      (node (ref "C99") (pin "1") (pinfunction "1_1") (pintype "passive"))
      (node (ref "IC17") (pin "2") (pinfunction "REFOUT_2") (pintype "bidirectional"))
    )
    (net (code "282") (name "Net-(IC17-VIN)") (class "Default")
      (node (ref "IC17") (pin "17") (pinfunction "VIN_17") (pintype "bidirectional"))
      (node (ref "SJ102") (pin "1") (pinfunction "1_1") (pintype "passive"))
      (node (ref "SJ99") (pin "2") (pinfunction "2_2") (pintype "passive"))
    )
    (net (code "283") (name "Net-(U1-CFLY+)") (class "Default")
      (node (ref "C88") (pin "2") (pinfunction "2_2") (pintype "passive"))
      (node (ref "U1") (pin "5") (pinfunction "CFLY+_5") (pintype "input"))
    )
    (net (code "284") (name "Net-(U1-CFLY-)") (class "Default")
      (node (ref "C88") (pin "1") (pinfunction "1_1") (pintype "passive"))
      (node (ref "U1") (pin "3") (pinfunction "CFLY-_3") (pintype "input"))
    )
    (net (code "285") (name "Net-(U3-EXT_CAP)") (class "Default")
      (node (ref "C107") (pin "1") (pinfunction "1_1") (pintype "passive"))
      (node (ref "U3") (pin "5") (pinfunction "EXT_CAP_5") (pintype "passive"))
    )
    (net (code "286") (name "Net-(U7-CFLY+)") (class "Default")
      (node (ref "C115") (pin "2") (pinfunction "2_2") (pintype "passive"))
      (node (ref "U7") (pin "5") (pinfunction "CFLY+_5") (pintype "input"))
    )
    (net (code "287") (name "Net-(U7-CFLY-)") (class "Default")
      (node (ref "C115") (pin "1") (pinfunction "1_1") (pintype "passive"))
      (node (ref "U7") (pin "3") (pinfunction "CFLY-_3") (pintype "input"))
    )
    (net (code "288") (name "Net-(U8-EXT_CAP)") (class "Default")
      (node (ref "C120") (pin "1") (pinfunction "1_1") (pintype "passive"))
      (node (ref "U8") (pin "5") (pinfunction "EXT_CAP_5") (pintype "passive"))
    )
    (net (code "289") (name "Net-(U10-CFLY+)") (class "Default")
      (node (ref "C123") (pin "2") (pinfunction "2_2") (pintype "passive"))
      (node (ref "U10") (pin "5") (pinfunction "CFLY+_5") (pintype "input"))
    )
    (net (code "290") (name "Net-(U10-CFLY-)") (class "Default")
      (node (ref "C123") (pin "1") (pinfunction "1_1") (pintype "passive"))
      (node (ref "U10") (pin "3") (pinfunction "CFLY-_3") (pintype "input"))
    )
    (net (code "291") (name "Net-(U11-EXT_CAP)") (class "Default")
      (node (ref "C128") (pin "1") (pinfunction "1_1") (pintype "passive"))
      (node (ref "U11") (pin "5") (pinfunction "EXT_CAP_5") (pintype "passive"))
    )
    (net (code "292") (name "Net-(U13-CFLY+)") (class "Default")
      (node (ref "C131") (pin "2") (pinfunction "2_2") (pintype "passive"))
      (node (ref "U13") (pin "5") (pinfunction "CFLY+_5") (pintype "input"))
    )
    (net (code "293") (name "Net-(U13-CFLY-)") (class "Default")
      (node (ref "C131") (pin "1") (pinfunction "1_1") (pintype "passive"))
      (node (ref "U13") (pin "3") (pinfunction "CFLY-_3") (pintype "input"))
    )
    (net (code "294") (name "Net-(U14-EXT_CAP)") (class "Default")
      (node (ref "C136") (pin "1") (pinfunction "1_1") (pintype "passive"))
      (node (ref "U14") (pin "5") (pinfunction "EXT_CAP_5") (pintype "passive"))
    )
    (net (code "295") (name "Net-(U16-CFLY+)") (class "Default")
      (node (ref "C139") (pin "2") (pinfunction "2_2") (pintype "passive"))
      (node (ref "U16") (pin "5") (pinfunction "CFLY+_5") (pintype "input"))
    )
    (net (code "296") (name "Net-(U16-CFLY-)") (class "Default")
      (node (ref "C139") (pin "1") (pinfunction "1_1") (pintype "passive"))
      (node (ref "U16") (pin "3") (pinfunction "CFLY-_3") (pintype "input"))
    )
    (net (code "297") (name "Net-(U17-EXT_CAP)") (class "Default")
      (node (ref "C144") (pin "1") (pinfunction "1_1") (pintype "passive"))
      (node (ref "U17") (pin "5") (pinfunction "EXT_CAP_5") (pintype "passive"))
    )
    (net (code "298") (name "Net-(U19-CFLY+)") (class "Default")
      (node (ref "C147") (pin "2") (pinfunction "2_2") (pintype "passive"))
      (node (ref "U19") (pin "5") (pinfunction "CFLY+_5") (pintype "input"))
    )
    (net (code "299") (name "Net-(U19-CFLY-)") (class "Default")
      (node (ref "C147") (pin "1") (pinfunction "1_1") (pintype "passive"))
      (node (ref "U19") (pin "3") (pinfunction "CFLY-_3") (pintype "input"))
    )
    (net (code "300") (name "Net-(U20-EXT_CAP)") (class "Default")
      (node (ref "C152") (pin "1") (pinfunction "1_1") (pintype "passive"))
      (node (ref "U20") (pin "5") (pinfunction "EXT_CAP_5") (pintype "passive"))
    )
    (net (code "301") (name "Net-(U22-CFLY+)") (class "Default")
      (node (ref "C155") (pin "2") (pinfunction "2_2") (pintype "passive"))
      (node (ref "U22") (pin "5") (pinfunction "CFLY+_5") (pintype "input"))
    )
    (net (code "302") (name "Net-(U22-CFLY-)") (class "Default")
      (node (ref "C155") (pin "1") (pinfunction "1_1") (pintype "passive"))
      (node (ref "U22") (pin "3") (pinfunction "CFLY-_3") (pintype "input"))
    )
    (net (code "303") (name "Net-(U23-EXT_CAP)") (class "Default")
      (node (ref "C160") (pin "1") (pinfunction "1_1") (pintype "passive"))
      (node (ref "U23") (pin "5") (pinfunction "EXT_CAP_5") (pintype "passive"))
    )
    (net (code "304") (name "Net-(U25-CFLY+)") (class "Default")
      (node (ref "C163") (pin "2") (pinfunction "2_2") (pintype "passive"))
      (node (ref "U25") (pin "5") (pinfunction "CFLY+_5") (pintype "input"))
    )
    (net (code "305") (name "Net-(U25-CFLY-)") (class "Default")
      (node (ref "C163") (pin "1") (pinfunction "1_1") (pintype "passive"))
      (node (ref "U25") (pin "3") (pinfunction "CFLY-_3") (pintype "input"))
    )
    (net (code "306") (name "Net-(U26-EXT_CAP)") (class "Default")
      (node (ref "C168") (pin "1") (pinfunction "1_1") (pintype "passive"))
      (node (ref "U26") (pin "5") (pinfunction "EXT_CAP_5") (pintype "passive"))
    )
    (net (code "307") (name "Net-(U28-CFLY+)") (class "Default")
      (node (ref "C171") (pin "2") (pinfunction "2_2") (pintype "passive"))
      (node (ref "U28") (pin "5") (pinfunction "CFLY+_5") (pintype "input"))
    )
    (net (code "308") (name "Net-(U28-CFLY-)") (class "Default")
      (node (ref "C171") (pin "1") (pinfunction "1_1") (pintype "passive"))
      (node (ref "U28") (pin "3") (pinfunction "CFLY-_3") (pintype "input"))
    )
    (net (code "309") (name "Net-(U29-EXT_CAP)") (class "Default")
      (node (ref "C176") (pin "1") (pinfunction "1_1") (pintype "passive"))
      (node (ref "U29") (pin "5") (pinfunction "EXT_CAP_5") (pintype "passive"))
    )
    (net (code "310") (name "Net-(U31-CFLY+)") (class "Default")
      (node (ref "C179") (pin "2") (pinfunction "2_2") (pintype "passive"))
      (node (ref "U31") (pin "5") (pinfunction "CFLY+_5") (pintype "input"))
    )
    (net (code "311") (name "Net-(U31-CFLY-)") (class "Default")
      (node (ref "C179") (pin "1") (pinfunction "1_1") (pintype "passive"))
      (node (ref "U31") (pin "3") (pinfunction "CFLY-_3") (pintype "input"))
    )
    (net (code "312") (name "Net-(U32-EXT_CAP)") (class "Default")
      (node (ref "C184") (pin "1") (pinfunction "1_1") (pintype "passive"))
      (node (ref "U32") (pin "5") (pinfunction "EXT_CAP_5") (pintype "passive"))
    )
    (net (code "313") (name "Net-(U34-CFLY+)") (class "Default")
      (node (ref "C187") (pin "2") (pinfunction "2_2") (pintype "passive"))
      (node (ref "U34") (pin "5") (pinfunction "CFLY+_5") (pintype "input"))
    )
    (net (code "314") (name "Net-(U34-CFLY-)") (class "Default")
      (node (ref "C187") (pin "1") (pinfunction "1_1") (pintype "passive"))
      (node (ref "U34") (pin "3") (pinfunction "CFLY-_3") (pintype "input"))
    )
    (net (code "315") (name "Net-(U35-EXT_CAP)") (class "Default")
      (node (ref "C192") (pin "1") (pinfunction "1_1") (pintype "passive"))
      (node (ref "U35") (pin "5") (pinfunction "EXT_CAP_5") (pintype "passive"))
    )
    (net (code "316") (name "Net-(U37-CFLY+)") (class "Default")
      (node (ref "C195") (pin "2") (pinfunction "2_2") (pintype "passive"))
      (node (ref "U37") (pin "5") (pinfunction "CFLY+_5") (pintype "input"))
    )
    (net (code "317") (name "Net-(U37-CFLY-)") (class "Default")
      (node (ref "C195") (pin "1") (pinfunction "1_1") (pintype "passive"))
      (node (ref "U37") (pin "3") (pinfunction "CFLY-_3") (pintype "input"))
    )
    (net (code "318") (name "Net-(U38-EXT_CAP)") (class "Default")
      (node (ref "C200") (pin "1") (pinfunction "1_1") (pintype "passive"))
      (node (ref "U38") (pin "5") (pinfunction "EXT_CAP_5") (pintype "passive"))
    )
    (net (code "319") (name "Net-(U40-CFLY+)") (class "Default")
      (node (ref "C203") (pin "2") (pinfunction "2_2") (pintype "passive"))
      (node (ref "U40") (pin "5") (pinfunction "CFLY+_5") (pintype "input"))
    )
    (net (code "320") (name "Net-(U40-CFLY-)") (class "Default")
      (node (ref "C203") (pin "1") (pinfunction "1_1") (pintype "passive"))
      (node (ref "U40") (pin "3") (pinfunction "CFLY-_3") (pintype "input"))
    )
    (net (code "321") (name "Net-(U41-EXT_CAP)") (class "Default")
      (node (ref "C208") (pin "1") (pinfunction "1_1") (pintype "passive"))
      (node (ref "U41") (pin "5") (pinfunction "EXT_CAP_5") (pintype "passive"))
    )
    (net (code "322") (name "Net-(U43-CFLY+)") (class "Default")
      (node (ref "C211") (pin "2") (pinfunction "2_2") (pintype "passive"))
      (node (ref "U43") (pin "5") (pinfunction "CFLY+_5") (pintype "input"))
    )
    (net (code "323") (name "Net-(U43-CFLY-)") (class "Default")
      (node (ref "C211") (pin "1") (pinfunction "1_1") (pintype "passive"))
      (node (ref "U43") (pin "3") (pinfunction "CFLY-_3") (pintype "input"))
    )
    (net (code "324") (name "Net-(U44-EXT_CAP)") (class "Default")
      (node (ref "C216") (pin "1") (pinfunction "1_1") (pintype "passive"))
      (node (ref "U44") (pin "5") (pinfunction "EXT_CAP_5") (pintype "passive"))
    )
    (net (code "325") (name "Net-(U46-CFLY+)") (class "Default")
      (node (ref "C219") (pin "2") (pinfunction "2_2") (pintype "passive"))
      (node (ref "U46") (pin "5") (pinfunction "CFLY+_5") (pintype "input"))
    )
    (net (code "326") (name "Net-(U46-CFLY-)") (class "Default")
      (node (ref "C219") (pin "1") (pinfunction "1_1") (pintype "passive"))
      (node (ref "U46") (pin "3") (pinfunction "CFLY-_3") (pintype "input"))
    )
    (net (code "327") (name "Net-(U47-EXT_CAP)") (class "Default")
      (node (ref "C224") (pin "1") (pinfunction "1_1") (pintype "passive"))
      (node (ref "U47") (pin "5") (pinfunction "EXT_CAP_5") (pintype "passive"))
    )
    (net (code "328") (name "Net-(U49-CFLY+)") (class "Default")
      (node (ref "C227") (pin "2") (pinfunction "2_2") (pintype "passive"))
      (node (ref "U49") (pin "5") (pinfunction "CFLY+_5") (pintype "input"))
    )
    (net (code "329") (name "Net-(U49-CFLY-)") (class "Default")
      (node (ref "C227") (pin "1") (pinfunction "1_1") (pintype "passive"))
      (node (ref "U49") (pin "3") (pinfunction "CFLY-_3") (pintype "input"))
    )
    (net (code "330") (name "Net-(U50-EXT_CAP)") (class "Default")
      (node (ref "C232") (pin "1") (pinfunction "1_1") (pintype "passive"))
      (node (ref "U50") (pin "5") (pinfunction "EXT_CAP_5") (pintype "passive"))
    )
  )
)
